# surfaceRX.net
KiCad netlist of a schematic drawn in EAGLE
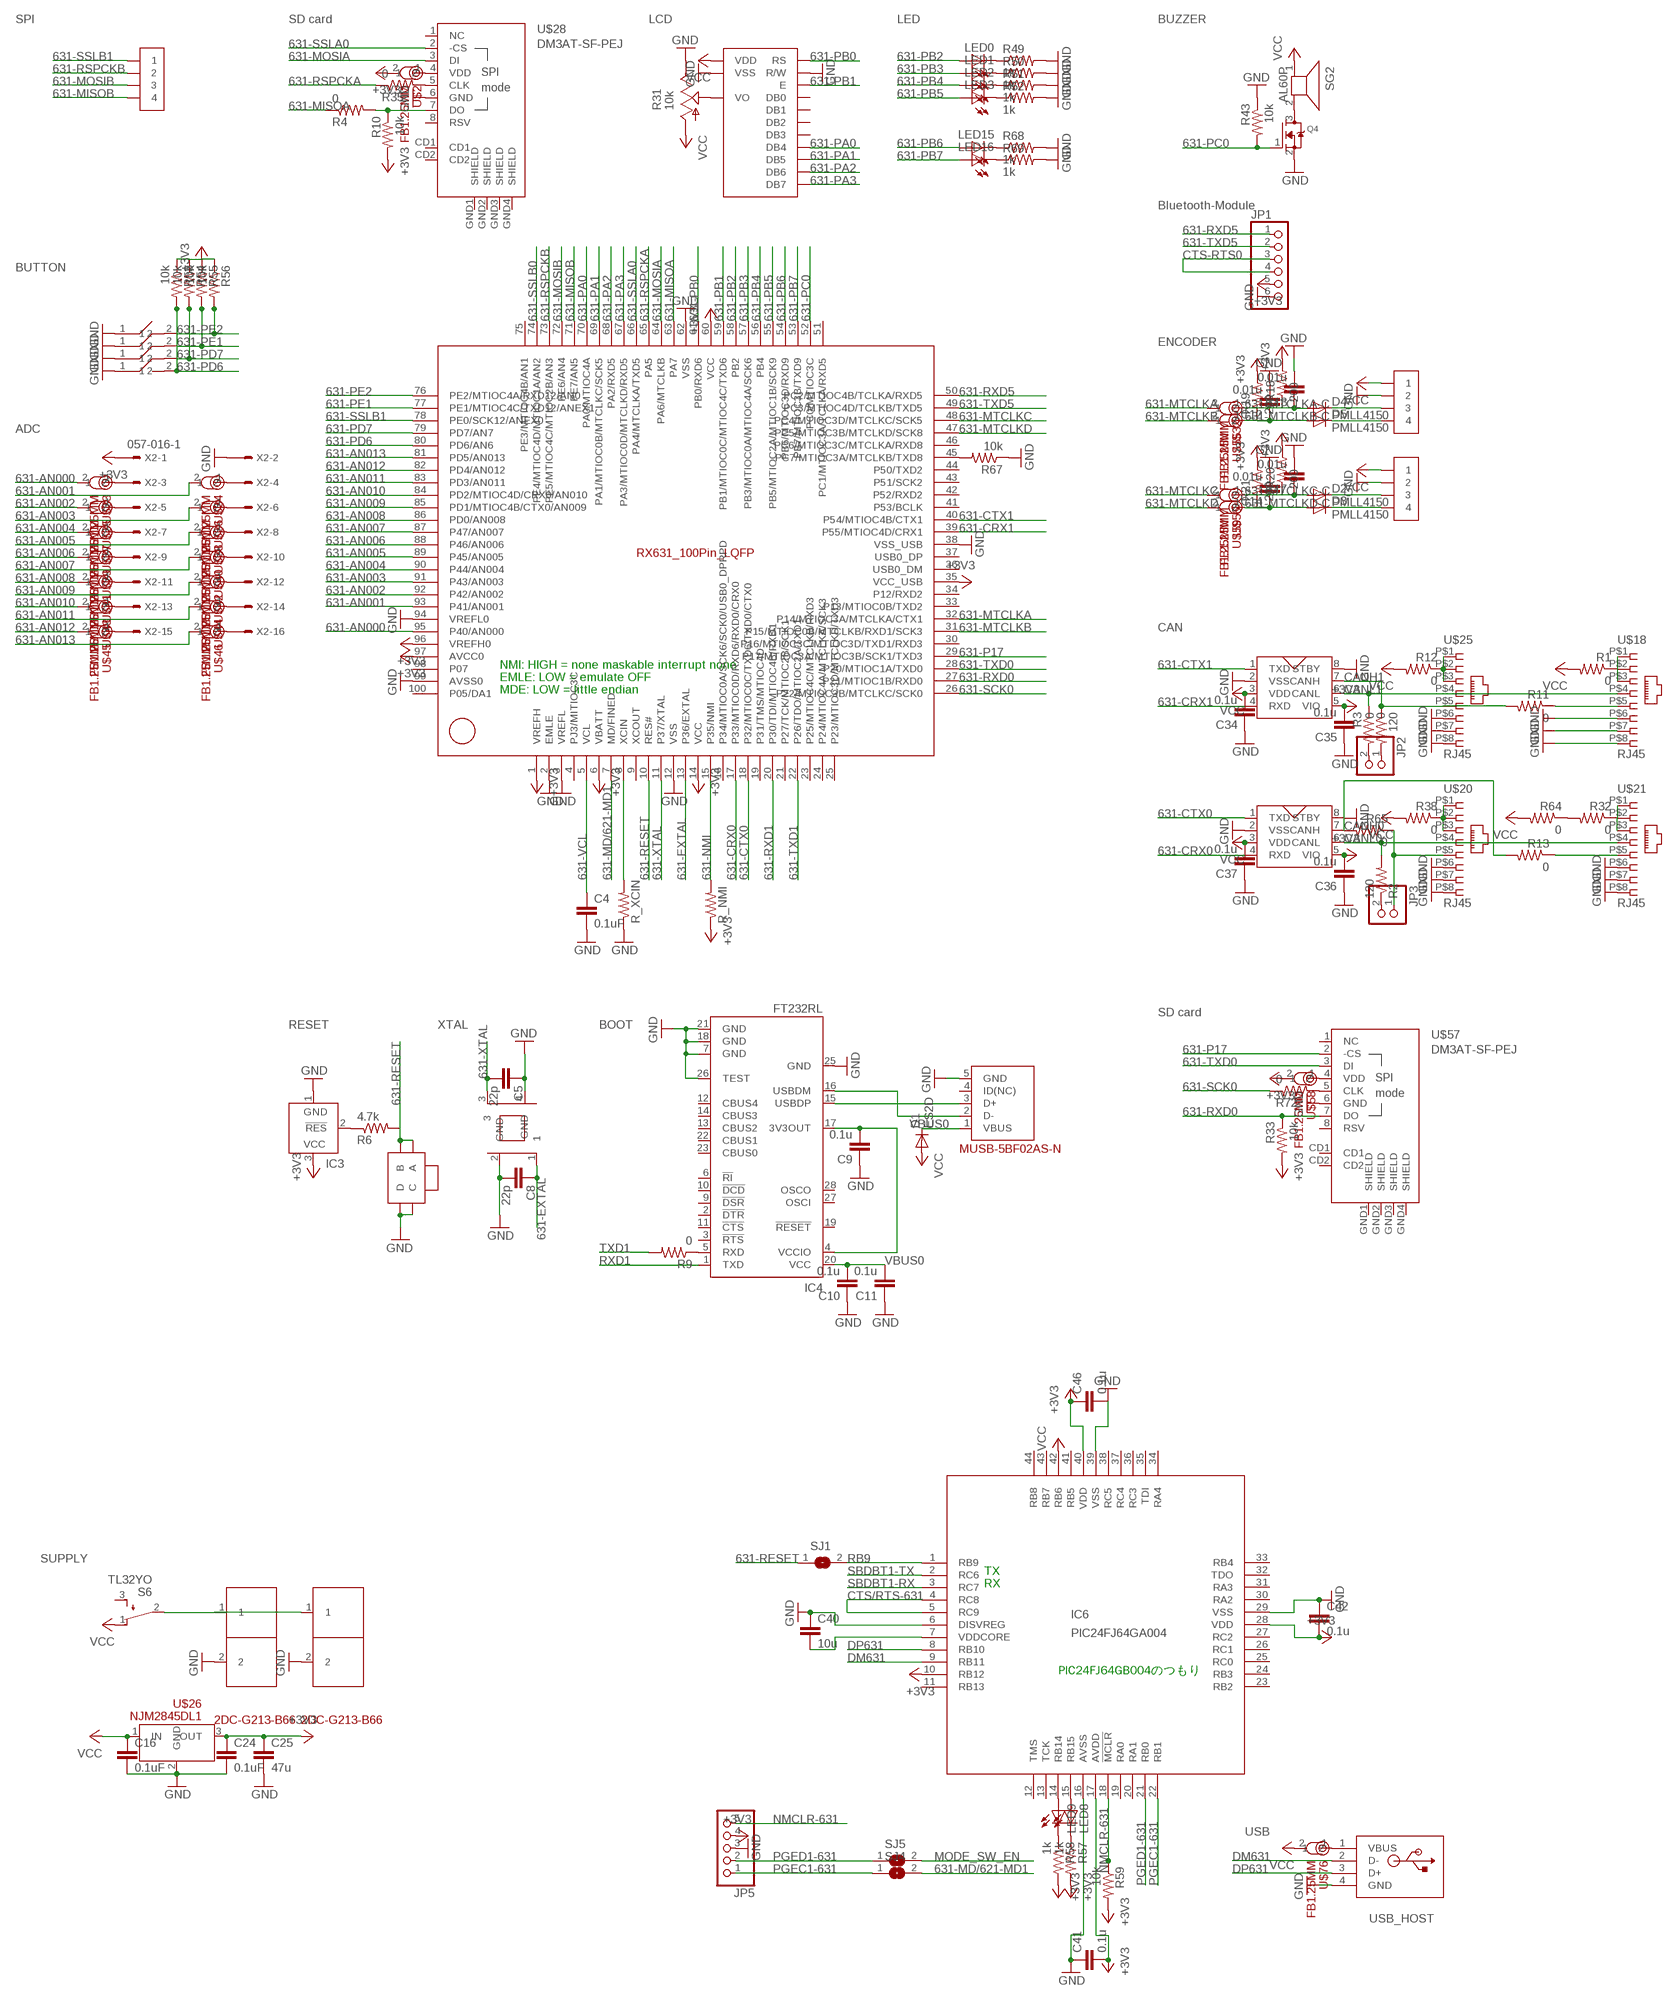
[diagram p0: schematic, sheet 1, part 1 of 2]
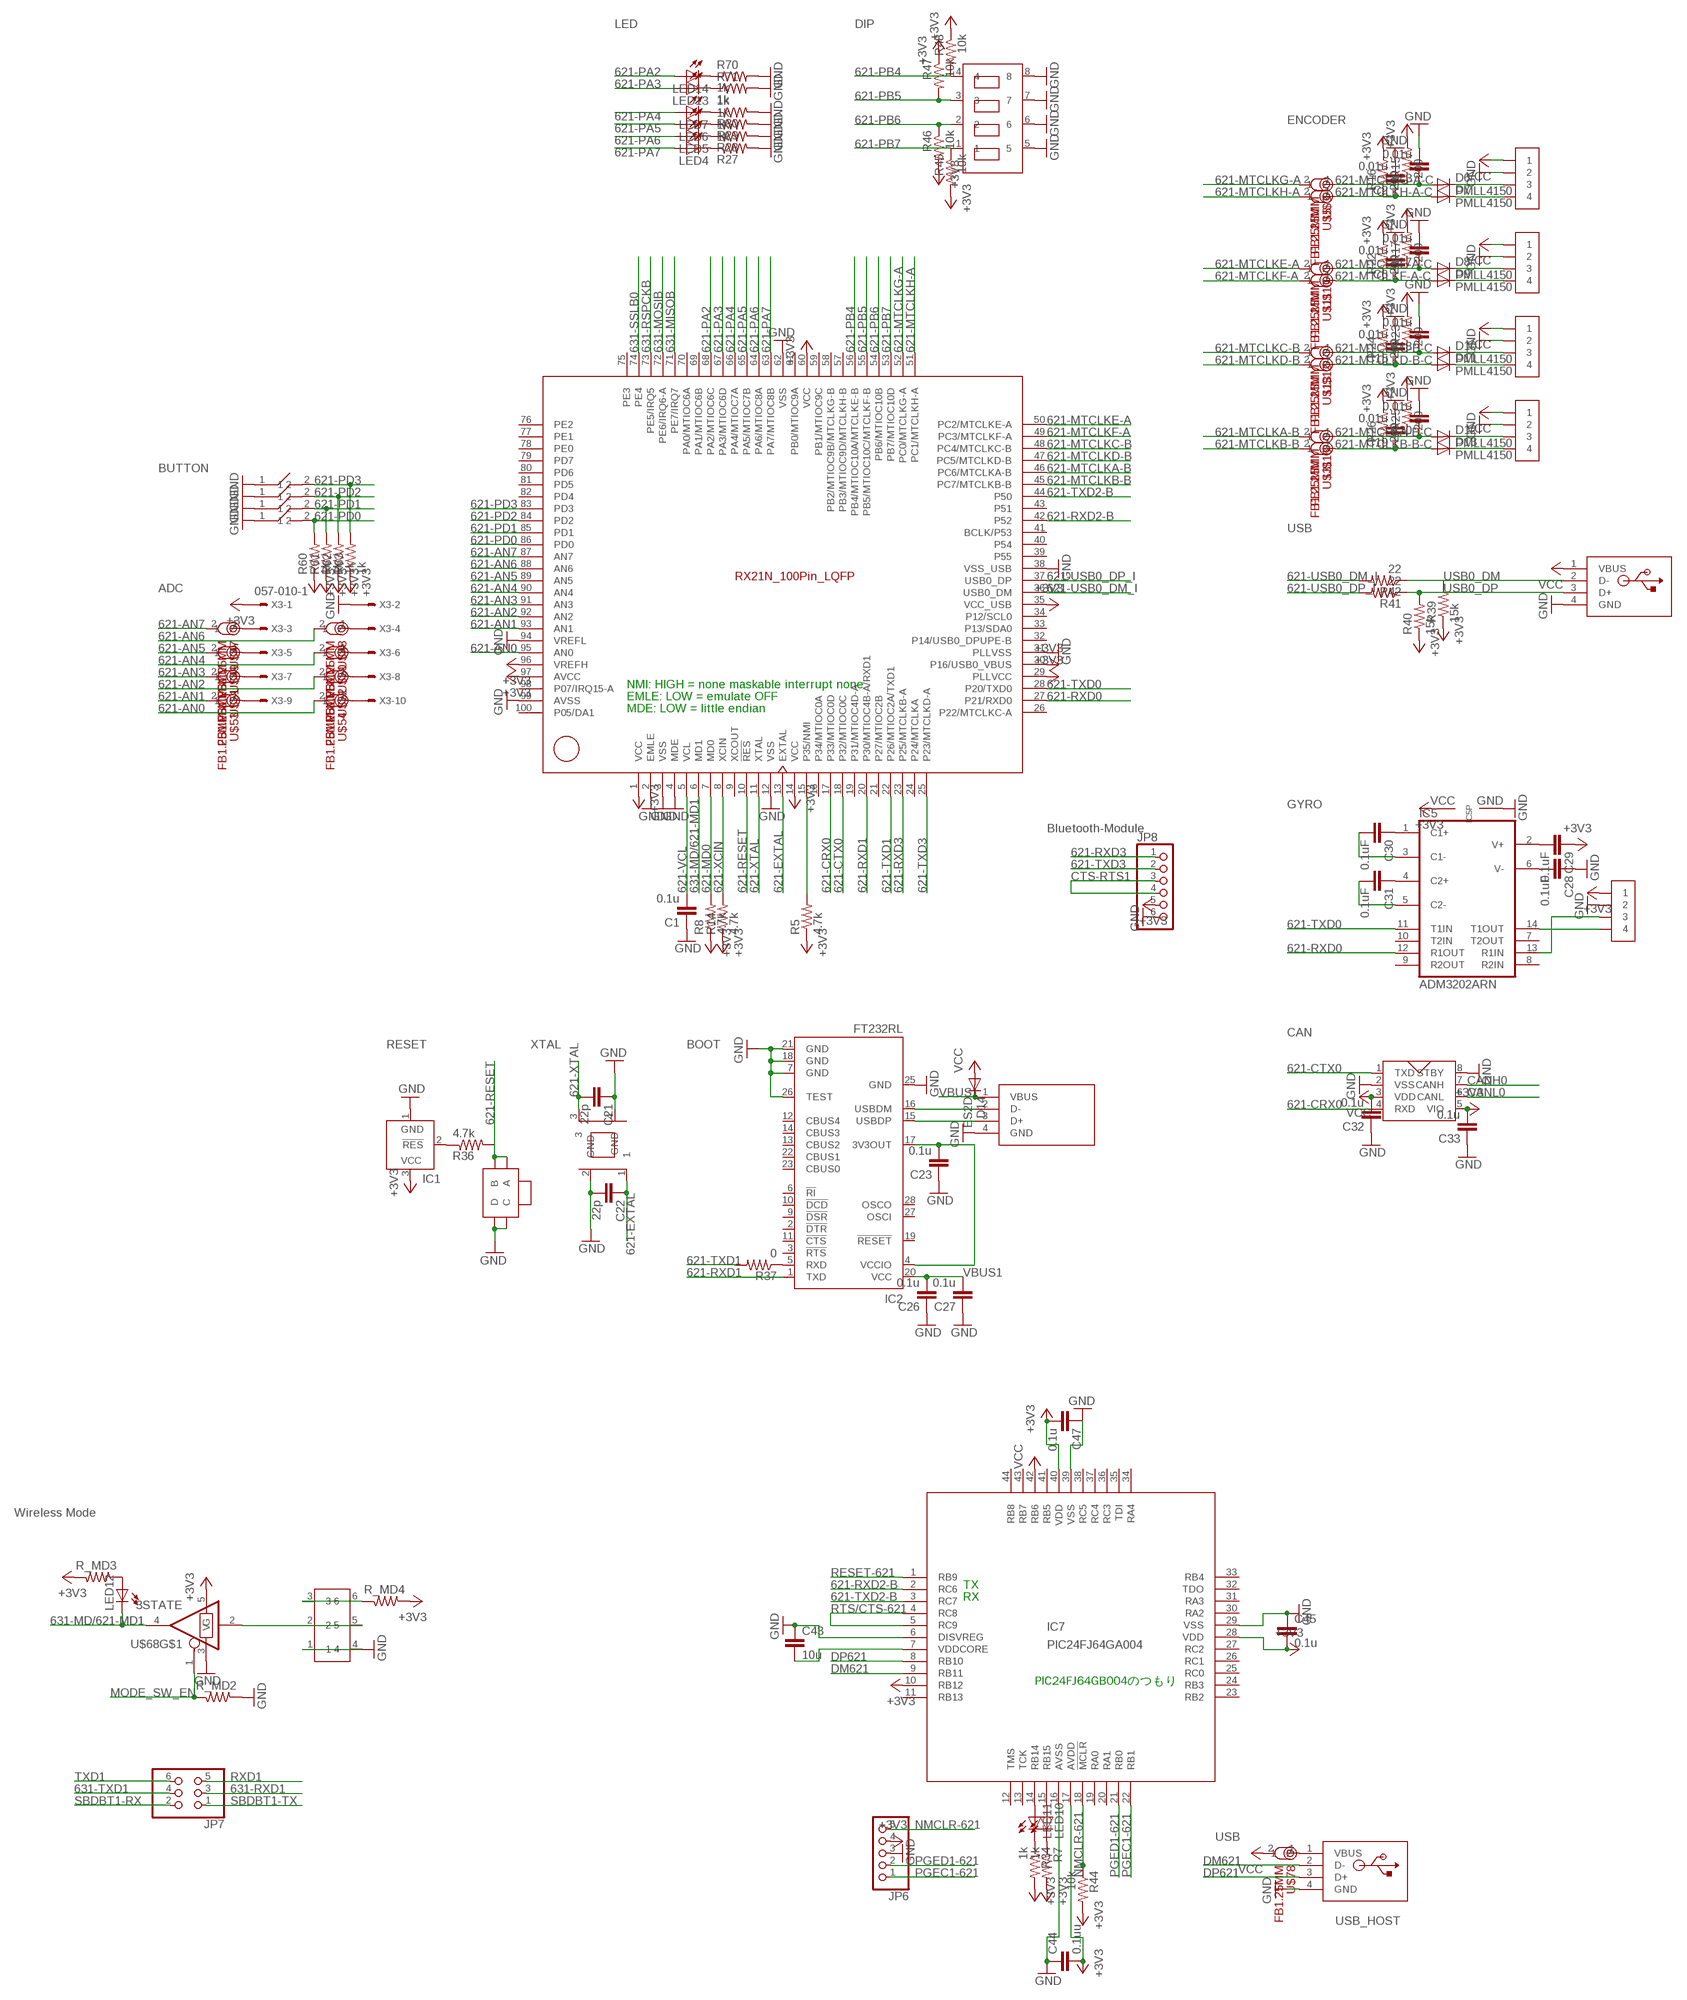
[diagram p1: schematic, sheet 1, part 2 of 2]

(export (version "E")
  (design (tool "Eeschema 10.0.6"))
  (components
    (comp (ref "0")
      (value "120")
      (footprint "eagle-import:MINI_MELF-0102W")
      (libsource (lib "eagle-import") (part "R-US_MELF0102W"))
    )
    (comp (ref "C1")
      (value "0.1u")
      (footprint "eagle-import:C0402")
      (libsource (lib "eagle-import") (part "C-EUC0402"))
    )
    (comp (ref "C2")
      (value "0.01u")
      (footprint "eagle-import:C0402")
      (libsource (lib "eagle-import") (part "C-EUC0402"))
    )
    (comp (ref "C3")
      (value "0.01u")
      (footprint "eagle-import:C0402")
      (libsource (lib "eagle-import") (part "C-EUC0402"))
    )
    (comp (ref "C4")
      (value "0.1uF")
      (footprint "eagle-import:C0603K")
      (libsource (lib "eagle-import") (part "C-EUC0603K"))
    )
    (comp (ref "C5")
      (value "22p")
      (footprint "eagle-import:C0603K")
      (libsource (lib "eagle-import") (part "C-EUC0603K"))
    )
    (comp (ref "C6")
      (value "0.01u")
      (footprint "eagle-import:C0402")
      (libsource (lib "eagle-import") (part "C-EUC0402"))
    )
    (comp (ref "C7")
      (value "0.01u")
      (footprint "eagle-import:C0402")
      (libsource (lib "eagle-import") (part "C-EUC0402"))
    )
    (comp (ref "C8")
      (value "22p")
      (footprint "eagle-import:C0603K")
      (libsource (lib "eagle-import") (part "C-EUC0603K"))
    )
    (comp (ref "C9")
      (value "0.1u")
      (footprint "eagle-import:C0402")
      (libsource (lib "eagle-import") (part "C-EUC0402"))
    )
    (comp (ref "C10")
      (value "0.1u")
      (footprint "eagle-import:C0402")
      (libsource (lib "eagle-import") (part "C-EUC0402"))
    )
    (comp (ref "C11")
      (value "0.1u")
      (footprint "eagle-import:C0402")
      (libsource (lib "eagle-import") (part "C-EUC0402"))
    )
    (comp (ref "C12")
      (value "0.01u")
      (footprint "eagle-import:C0402")
      (libsource (lib "eagle-import") (part "C-EUC0402"))
    )
    (comp (ref "C13")
      (value "0.01u")
      (footprint "eagle-import:C0402")
      (libsource (lib "eagle-import") (part "C-EUC0402"))
    )
    (comp (ref "C14")
      (value "0.01u")
      (footprint "eagle-import:C0402")
      (libsource (lib "eagle-import") (part "C-EUC0402"))
    )
    (comp (ref "C15")
      (value "0.01u")
      (footprint "eagle-import:C0402")
      (libsource (lib "eagle-import") (part "C-EUC0402"))
    )
    (comp (ref "C16")
      (value "0.1uF")
      (footprint "eagle-import:C0603K")
      (libsource (lib "eagle-import") (part "C-EUC0603K"))
    )
    (comp (ref "C17")
      (value "0.01u")
      (footprint "eagle-import:C0402")
      (libsource (lib "eagle-import") (part "C-EUC0402"))
    )
    (comp (ref "C18")
      (value "0.01u")
      (footprint "eagle-import:C0402")
      (libsource (lib "eagle-import") (part "C-EUC0402"))
    )
    (comp (ref "C19")
      (value "0.01u")
      (footprint "eagle-import:C0402")
      (libsource (lib "eagle-import") (part "C-EUC0402"))
    )
    (comp (ref "C20")
      (value "0.01u")
      (footprint "eagle-import:C0402")
      (libsource (lib "eagle-import") (part "C-EUC0402"))
    )
    (comp (ref "C21")
      (value "22p")
      (footprint "eagle-import:C0603K")
      (libsource (lib "eagle-import") (part "C-EUC0603K"))
    )
    (comp (ref "C22")
      (value "22p")
      (footprint "eagle-import:C0603K")
      (libsource (lib "eagle-import") (part "C-EUC0603K"))
    )
    (comp (ref "C23")
      (value "0.1u")
      (footprint "eagle-import:C0402")
      (libsource (lib "eagle-import") (part "C-EUC0402"))
    )
    (comp (ref "C24")
      (value "0.1uF")
      (footprint "eagle-import:C0603K")
      (libsource (lib "eagle-import") (part "C-EUC0603K"))
    )
    (comp (ref "C25")
      (value "47u")
      (footprint "eagle-import:C3225")
      (libsource (lib "eagle-import") (part "C-EUC3225"))
    )
    (comp (ref "C26")
      (value "0.1u")
      (footprint "eagle-import:C0402")
      (libsource (lib "eagle-import") (part "C-EUC0402"))
    )
    (comp (ref "C27")
      (value "0.1u")
      (footprint "eagle-import:C0402")
      (libsource (lib "eagle-import") (part "C-EUC0402"))
    )
    (comp (ref "C28")
      (value "0.1uF")
      (footprint "eagle-import:C0603K")
      (libsource (lib "eagle-import") (part "C-EUC0603K"))
    )
    (comp (ref "C29")
      (value "0.1uF")
      (footprint "eagle-import:C0603K")
      (libsource (lib "eagle-import") (part "C-EUC0603K"))
    )
    (comp (ref "C30")
      (value "0.1uF")
      (footprint "eagle-import:C0603K")
      (libsource (lib "eagle-import") (part "C-EUC0603K"))
    )
    (comp (ref "C31")
      (value "0.1uF")
      (footprint "eagle-import:C0603K")
      (libsource (lib "eagle-import") (part "C-EUC0603K"))
    )
    (comp (ref "C32")
      (value "0.1u")
      (footprint "eagle-import:C0402")
      (libsource (lib "eagle-import") (part "C-EUC0402"))
    )
    (comp (ref "C33")
      (value "0.1u")
      (footprint "eagle-import:C0402")
      (libsource (lib "eagle-import") (part "C-EUC0402"))
    )
    (comp (ref "C34")
      (value "0.1u")
      (footprint "eagle-import:C0402")
      (libsource (lib "eagle-import") (part "C-EUC0402"))
    )
    (comp (ref "C35")
      (value "0.1u")
      (footprint "eagle-import:C0402")
      (libsource (lib "eagle-import") (part "C-EUC0402"))
    )
    (comp (ref "C36")
      (value "0.1u")
      (footprint "eagle-import:C0402")
      (libsource (lib "eagle-import") (part "C-EUC0402"))
    )
    (comp (ref "C37")
      (value "0.1u")
      (footprint "eagle-import:C0402")
      (libsource (lib "eagle-import") (part "C-EUC0402"))
    )
    (comp (ref "C40")
      (value "10u")
      (footprint "eagle-import:C0603K")
      (libsource (lib "eagle-import") (part "C-EUC0603K"))
    )
    (comp (ref "C41")
      (value "0.1u")
      (footprint "eagle-import:C0603K")
      (libsource (lib "eagle-import") (part "C-EUC0603K"))
    )
    (comp (ref "C42")
      (value "0.1u")
      (footprint "eagle-import:C0603K")
      (libsource (lib "eagle-import") (part "C-EUC0603K"))
    )
    (comp (ref "C43")
      (value "10u")
      (footprint "eagle-import:C0603K")
      (libsource (lib "eagle-import") (part "C-EUC0603K"))
    )
    (comp (ref "C44")
      (value "0.1uu")
      (footprint "eagle-import:C0603K")
      (libsource (lib "eagle-import") (part "C-EUC0603K"))
    )
    (comp (ref "C45")
      (value "0.1u")
      (footprint "eagle-import:C0603K")
      (libsource (lib "eagle-import") (part "C-EUC0603K"))
    )
    (comp (ref "C46")
      (value "0.1u")
      (footprint "eagle-import:C0603K")
      (libsource (lib "eagle-import") (part "C-EUC0603K"))
    )
    (comp (ref "C47")
      (value "0.1u")
      (footprint "eagle-import:C0603K")
      (libsource (lib "eagle-import") (part "C-EUC0603K"))
    )
    (comp (ref "D1")
      (value "ES2D")
      (footprint "eagle-import:SMB")
      (libsource (lib "eagle-import") (part "ES2D"))
    )
    (comp (ref "D2")
      (value "PMLL4150")
      (footprint "eagle-import:SOD80C")
      (libsource (lib "eagle-import") (part "PMLL4150"))
    )
    (comp (ref "D3")
      (value "PMLL4150")
      (footprint "eagle-import:SOD80C")
      (libsource (lib "eagle-import") (part "PMLL4150"))
    )
    (comp (ref "D4")
      (value "PMLL4150")
      (footprint "eagle-import:SOD80C")
      (libsource (lib "eagle-import") (part "PMLL4150"))
    )
    (comp (ref "D5")
      (value "PMLL4150")
      (footprint "eagle-import:SOD80C")
      (libsource (lib "eagle-import") (part "PMLL4150"))
    )
    (comp (ref "D6")
      (value "PMLL4150")
      (footprint "eagle-import:SOD80C")
      (libsource (lib "eagle-import") (part "PMLL4150"))
    )
    (comp (ref "D7")
      (value "PMLL4150")
      (footprint "eagle-import:SOD80C")
      (libsource (lib "eagle-import") (part "PMLL4150"))
    )
    (comp (ref "D8")
      (value "PMLL4150")
      (footprint "eagle-import:SOD80C")
      (libsource (lib "eagle-import") (part "PMLL4150"))
    )
    (comp (ref "D9")
      (value "PMLL4150")
      (footprint "eagle-import:SOD80C")
      (libsource (lib "eagle-import") (part "PMLL4150"))
    )
    (comp (ref "D10")
      (value "PMLL4150")
      (footprint "eagle-import:SOD80C")
      (libsource (lib "eagle-import") (part "PMLL4150"))
    )
    (comp (ref "D11")
      (value "PMLL4150")
      (footprint "eagle-import:SOD80C")
      (libsource (lib "eagle-import") (part "PMLL4150"))
    )
    (comp (ref "D12")
      (value "PMLL4150")
      (footprint "eagle-import:SOD80C")
      (libsource (lib "eagle-import") (part "PMLL4150"))
    )
    (comp (ref "D13")
      (value "PMLL4150")
      (footprint "eagle-import:SOD80C")
      (libsource (lib "eagle-import") (part "PMLL4150"))
    )
    (comp (ref "D14")
      (value "ES2D")
      (footprint "eagle-import:SMB")
      (libsource (lib "eagle-import") (part "ES2D"))
    )
    (comp (ref "IC1")
      (value "TCM809")
      (footprint "eagle-import:SOT23B-3")
      (fields (field (name "MF") "MICROCHIP") (field (name "MPN") "TCM809MENB713"))
      (libsource (lib "eagle-import") (part "TCM809"))
    )
    (comp (ref "IC2")
      (value "FT232RL")
      (footprint "eagle-import:SSOP28")
      (libsource (lib "eagle-import") (part "FT232RL"))
    )
    (comp (ref "IC3")
      (value "TCM809")
      (footprint "eagle-import:SOT23B-3")
      (fields (field (name "MF") "MICROCHIP") (field (name "MPN") "TCM809MENB713"))
      (libsource (lib "eagle-import") (part "TCM809"))
    )
    (comp (ref "IC4")
      (value "FT232RL")
      (footprint "eagle-import:SSOP28")
      (libsource (lib "eagle-import") (part "FT232RL"))
    )
    (comp (ref "IC5")
      (value "ADM3202ARN")
      (footprint "eagle-import:SO16")
      (libsource (lib "eagle-import") (part "ADM3202ARN"))
    )
    (comp (ref "IC6")
      (value "PIC24FJ64GA004")
      (footprint "eagle-import:TQFP44")
      (fields (field (name "MPN") "PIC24FJ64GA004-E/PT"))
      (libsource (lib "eagle-import") (part "PIC24FJ64GA004"))
    )
    (comp (ref "IC7")
      (value "PIC24FJ64GA004")
      (footprint "eagle-import:TQFP44")
      (fields (field (name "MPN") "PIC24FJ64GA004-E/PT"))
      (libsource (lib "eagle-import") (part "PIC24FJ64GA004"))
    )
    (comp (ref "JP1")
      (value "PINHD-1X6")
      (footprint "eagle-import:1X06")
      (libsource (lib "eagle-import") (part "PINHD-1X6"))
    )
    (comp (ref "JP2")
      (value "PINHD-1X2")
      (footprint "eagle-import:1X02")
      (libsource (lib "eagle-import") (part "PINHD-1X2"))
    )
    (comp (ref "JP3")
      (value "PINHD-1X2")
      (footprint "eagle-import:1X02")
      (libsource (lib "eagle-import") (part "PINHD-1X2"))
    )
    (comp (ref "JP5")
      (value "PINHD-1X5")
      (footprint "eagle-import:1X05")
      (libsource (lib "eagle-import") (part "PINHD-1X5"))
    )
    (comp (ref "JP6")
      (value "PINHD-1X5")
      (footprint "eagle-import:1X05")
      (libsource (lib "eagle-import") (part "PINHD-1X5"))
    )
    (comp (ref "JP7")
      (value "PINHD-2X3")
      (footprint "eagle-import:2X03")
      (libsource (lib "eagle-import") (part "PINHD-2X3"))
    )
    (comp (ref "JP8")
      (value "PINHD-1X6")
      (footprint "eagle-import:1X06")
      (libsource (lib "eagle-import") (part "PINHD-1X6"))
    )
    (comp (ref "LED0")
      (value "LEDSML0805")
      (footprint "eagle-import:SML0805")
      (libsource (lib "eagle-import") (part "LEDSML0805"))
    )
    (comp (ref "LED1")
      (value "LEDSML0805")
      (footprint "eagle-import:SML0805")
      (libsource (lib "eagle-import") (part "LEDSML0805"))
    )
    (comp (ref "LED2")
      (value "LEDSML0805")
      (footprint "eagle-import:SML0805")
      (libsource (lib "eagle-import") (part "LEDSML0805"))
    )
    (comp (ref "LED3")
      (value "LEDSML0805")
      (footprint "eagle-import:SML0805")
      (libsource (lib "eagle-import") (part "LEDSML0805"))
    )
    (comp (ref "LED4")
      (value "LEDSML0805")
      (footprint "eagle-import:SML0805")
      (libsource (lib "eagle-import") (part "LEDSML0805"))
    )
    (comp (ref "LED5")
      (value "LEDSML0805")
      (footprint "eagle-import:SML0805")
      (libsource (lib "eagle-import") (part "LEDSML0805"))
    )
    (comp (ref "LED6")
      (value "LEDSML0805")
      (footprint "eagle-import:SML0805")
      (libsource (lib "eagle-import") (part "LEDSML0805"))
    )
    (comp (ref "LED7")
      (value "LEDSML0805")
      (footprint "eagle-import:SML0805")
      (libsource (lib "eagle-import") (part "LEDSML0805"))
    )
    (comp (ref "LED8")
      (value "LEDSML0805")
      (footprint "eagle-import:SML0805")
      (libsource (lib "eagle-import") (part "LEDSML0805"))
    )
    (comp (ref "LED9")
      (value "LEDSML0805")
      (footprint "eagle-import:SML0805")
      (libsource (lib "eagle-import") (part "LEDSML0805"))
    )
    (comp (ref "LED10")
      (value "LEDSML0805")
      (footprint "eagle-import:SML0805")
      (libsource (lib "eagle-import") (part "LEDSML0805"))
    )
    (comp (ref "LED11")
      (value "LEDSML0805")
      (footprint "eagle-import:SML0805")
      (libsource (lib "eagle-import") (part "LEDSML0805"))
    )
    (comp (ref "LED12")
      (value "LEDSML0805")
      (footprint "eagle-import:SML0805")
      (libsource (lib "eagle-import") (part "LEDSML0805"))
    )
    (comp (ref "LED13")
      (value "LEDSML0805")
      (footprint "eagle-import:SML0805")
      (libsource (lib "eagle-import") (part "LEDSML0805"))
    )
    (comp (ref "LED14")
      (value "LEDSML0805")
      (footprint "eagle-import:SML0805")
      (libsource (lib "eagle-import") (part "LEDSML0805"))
    )
    (comp (ref "LED15")
      (value "LEDSML0805")
      (footprint "eagle-import:SML0805")
      (libsource (lib "eagle-import") (part "LEDSML0805"))
    )
    (comp (ref "LED16")
      (value "LEDSML0805")
      (footprint "eagle-import:SML0805")
      (libsource (lib "eagle-import") (part "LEDSML0805"))
    )
    (comp (ref "MCU1")
      (value "R5F562N8BDFP")
      (footprint "eagle-import:LQFP100")
      (libsource (lib "eagle-import") (part "R5F562N8BDFP"))
    )
    (comp (ref "Q4")
      (value "MOSFET-NREFLOW")
      (footprint "eagle-import:SOT23")
      (libsource (lib "eagle-import") (part "MOSFET-NREFLOW"))
    )
    (comp (ref "R1")
      (value "0")
      (footprint "eagle-import:MINI_MELF-0102W")
      (libsource (lib "eagle-import") (part "R-US_MELF0102W"))
    )
    (comp (ref "R2")
      (value "120")
      (footprint "eagle-import:MINI_MELF-0102W")
      (libsource (lib "eagle-import") (part "R-US_MELF0102W"))
    )
    (comp (ref "R3")
      (value "0")
      (footprint "eagle-import:MINI_MELF-0102W")
      (libsource (lib "eagle-import") (part "R-US_MELF0102W"))
    )
    (comp (ref "R4")
      (value "0")
      (footprint "eagle-import:MINI_MELF-0102W")
      (libsource (lib "eagle-import") (part "R-US_MELF0102W"))
    )
    (comp (ref "R5")
      (value "4.7k")
      (footprint "eagle-import:MINI_MELF-0102W")
      (libsource (lib "eagle-import") (part "R-US_MELF0102W"))
    )
    (comp (ref "R6")
      (value "4.7k")
      (footprint "eagle-import:MINI_MELF-0102W")
      (libsource (lib "eagle-import") (part "R-US_MELF0102W"))
    )
    (comp (ref "R7")
      (value "1k")
      (footprint "eagle-import:MINI_MELF-0102W")
      (libsource (lib "eagle-import") (part "R-US_MELF0102W"))
    )
    (comp (ref "R8")
      (value "4.7k")
      (footprint "eagle-import:MINI_MELF-0102W")
      (libsource (lib "eagle-import") (part "R-US_MELF0102W"))
    )
    (comp (ref "R9")
      (value "0")
      (footprint "eagle-import:MINI_MELF-0102W")
      (libsource (lib "eagle-import") (part "R-US_MELF0102W"))
    )
    (comp (ref "R10")
      (value "10k")
      (footprint "eagle-import:MINI_MELF-0102W")
      (libsource (lib "eagle-import") (part "R-US_MELF0102W"))
    )
    (comp (ref "R11")
      (value "0")
      (footprint "eagle-import:MINI_MELF-0102W")
      (libsource (lib "eagle-import") (part "R-US_MELF0102W"))
    )
    (comp (ref "R12")
      (value "0")
      (footprint "eagle-import:MINI_MELF-0102W")
      (libsource (lib "eagle-import") (part "R-US_MELF0102W"))
    )
    (comp (ref "R13")
      (value "0")
      (footprint "eagle-import:MINI_MELF-0102W")
      (libsource (lib "eagle-import") (part "R-US_MELF0102W"))
    )
    (comp (ref "R14")
      (value "4.7k")
      (footprint "eagle-import:MINI_MELF-0102W")
      (libsource (lib "eagle-import") (part "R-US_MELF0102W"))
    )
    (comp (ref "R15")
      (value "200")
      (footprint "eagle-import:MINI_MELF-0102W")
      (libsource (lib "eagle-import") (part "R-US_MELF0102W"))
    )
    (comp (ref "R16")
      (value "200")
      (footprint "eagle-import:MINI_MELF-0102W")
      (libsource (lib "eagle-import") (part "R-US_MELF0102W"))
    )
    (comp (ref "R17")
      (value "200")
      (footprint "eagle-import:MINI_MELF-0102W")
      (libsource (lib "eagle-import") (part "R-US_MELF0102W"))
    )
    (comp (ref "R18")
      (value "200")
      (footprint "eagle-import:MINI_MELF-0102W")
      (libsource (lib "eagle-import") (part "R-US_MELF0102W"))
    )
    (comp (ref "R19")
      (value "200")
      (footprint "eagle-import:MINI_MELF-0102W")
      (libsource (lib "eagle-import") (part "R-US_MELF0102W"))
    )
    (comp (ref "R20")
      (value "200")
      (footprint "eagle-import:MINI_MELF-0102W")
      (libsource (lib "eagle-import") (part "R-US_MELF0102W"))
    )
    (comp (ref "R21")
      (value "200")
      (footprint "eagle-import:MINI_MELF-0102W")
      (libsource (lib "eagle-import") (part "R-US_MELF0102W"))
    )
    (comp (ref "R22")
      (value "200")
      (footprint "eagle-import:MINI_MELF-0102W")
      (libsource (lib "eagle-import") (part "R-US_MELF0102W"))
    )
    (comp (ref "R23")
      (value "200")
      (footprint "eagle-import:MINI_MELF-0102W")
      (libsource (lib "eagle-import") (part "R-US_MELF0102W"))
    )
    (comp (ref "R24")
      (value "200")
      (footprint "eagle-import:MINI_MELF-0102W")
      (libsource (lib "eagle-import") (part "R-US_MELF0102W"))
    )
    (comp (ref "R25")
      (value "200")
      (footprint "eagle-import:MINI_MELF-0102W")
      (libsource (lib "eagle-import") (part "R-US_MELF0102W"))
    )
    (comp (ref "R26")
      (value "200")
      (footprint "eagle-import:MINI_MELF-0102W")
      (libsource (lib "eagle-import") (part "R-US_MELF0102W"))
    )
    (comp (ref "R27")
      (value "1k")
      (footprint "eagle-import:MINI_MELF-0102W")
      (libsource (lib "eagle-import") (part "R-US_MELF0102W"))
    )
    (comp (ref "R28")
      (value "1k")
      (footprint "eagle-import:MINI_MELF-0102W")
      (libsource (lib "eagle-import") (part "R-US_MELF0102W"))
    )
    (comp (ref "R29")
      (value "1k")
      (footprint "eagle-import:MINI_MELF-0102W")
      (libsource (lib "eagle-import") (part "R-US_MELF0102W"))
    )
    (comp (ref "R30")
      (value "1k")
      (footprint "eagle-import:MINI_MELF-0102W")
      (libsource (lib "eagle-import") (part "R-US_MELF0102W"))
    )
    (comp (ref "R31")
      (value "10k")
      (footprint "eagle-import:CA6V")
      (libsource (lib "eagle-import") (part "TRIM_US-CA6V"))
    )
    (comp (ref "R32")
      (value "0")
      (footprint "eagle-import:MINI_MELF-0102W")
      (libsource (lib "eagle-import") (part "R-US_MELF0102W"))
    )
    (comp (ref "R33")
      (value "10k")
      (footprint "eagle-import:MINI_MELF-0102W")
      (libsource (lib "eagle-import") (part "R-US_MELF0102W"))
    )
    (comp (ref "R34")
      (value "1k")
      (footprint "eagle-import:MINI_MELF-0102W")
      (libsource (lib "eagle-import") (part "R-US_MELF0102W"))
    )
    (comp (ref "R35")
      (value "0")
      (footprint "eagle-import:MINI_MELF-0102W")
      (libsource (lib "eagle-import") (part "R-US_MELF0102W"))
    )
    (comp (ref "R36")
      (value "4.7k")
      (footprint "eagle-import:MINI_MELF-0102W")
      (libsource (lib "eagle-import") (part "R-US_MELF0102W"))
    )
    (comp (ref "R37")
      (value "0")
      (footprint "eagle-import:MINI_MELF-0102W")
      (libsource (lib "eagle-import") (part "R-US_MELF0102W"))
    )
    (comp (ref "R38")
      (value "0")
      (footprint "eagle-import:MINI_MELF-0102W")
      (libsource (lib "eagle-import") (part "R-US_MELF0102W"))
    )
    (comp (ref "R39")
      (value "15k")
      (footprint "eagle-import:MINI_MELF-0102W")
      (libsource (lib "eagle-import") (part "R-US_MELF0102W"))
    )
    (comp (ref "R40")
      (value "15k")
      (footprint "eagle-import:MINI_MELF-0102W")
      (libsource (lib "eagle-import") (part "R-US_MELF0102W"))
    )
    (comp (ref "R41")
      (value "22")
      (footprint "eagle-import:MINI_MELF-0102W")
      (libsource (lib "eagle-import") (part "R-US_MELF0102W"))
    )
    (comp (ref "R42")
      (value "22")
      (footprint "eagle-import:MINI_MELF-0102W")
      (libsource (lib "eagle-import") (part "R-US_MELF0102W"))
    )
    (comp (ref "R43")
      (value "10k")
      (footprint "eagle-import:MINI_MELF-0102W")
      (libsource (lib "eagle-import") (part "R-US_MELF0102W"))
    )
    (comp (ref "R44")
      (value "10k")
      (footprint "eagle-import:MINI_MELF-0102W")
      (libsource (lib "eagle-import") (part "R-US_MELF0102W"))
    )
    (comp (ref "R45")
      (value "10k")
      (footprint "eagle-import:MINI_MELF-0102W")
      (libsource (lib "eagle-import") (part "R-US_MELF0102W"))
    )
    (comp (ref "R46")
      (value "10k")
      (footprint "eagle-import:MINI_MELF-0102W")
      (libsource (lib "eagle-import") (part "R-US_MELF0102W"))
    )
    (comp (ref "R47")
      (value "10k")
      (footprint "eagle-import:MINI_MELF-0102W")
      (libsource (lib "eagle-import") (part "R-US_MELF0102W"))
    )
    (comp (ref "R48")
      (value "10k")
      (footprint "eagle-import:MINI_MELF-0102W")
      (libsource (lib "eagle-import") (part "R-US_MELF0102W"))
    )
    (comp (ref "R49")
      (value "1k")
      (footprint "eagle-import:MINI_MELF-0102W")
      (libsource (lib "eagle-import") (part "R-US_MELF0102W"))
    )
    (comp (ref "R50")
      (value "1k")
      (footprint "eagle-import:MINI_MELF-0102W")
      (libsource (lib "eagle-import") (part "R-US_MELF0102W"))
    )
    (comp (ref "R51")
      (value "1k")
      (footprint "eagle-import:MINI_MELF-0102W")
      (libsource (lib "eagle-import") (part "R-US_MELF0102W"))
    )
    (comp (ref "R52")
      (value "1k")
      (footprint "eagle-import:MINI_MELF-0102W")
      (libsource (lib "eagle-import") (part "R-US_MELF0102W"))
    )
    (comp (ref "R53")
      (value "10k")
      (footprint "eagle-import:MINI_MELF-0102W")
      (libsource (lib "eagle-import") (part "R-US_MELF0102W"))
    )
    (comp (ref "R54")
      (value "10k")
      (footprint "eagle-import:MINI_MELF-0102W")
      (libsource (lib "eagle-import") (part "R-US_MELF0102W"))
    )
    (comp (ref "R55")
      (value "10k")
      (footprint "eagle-import:MINI_MELF-0102W")
      (libsource (lib "eagle-import") (part "R-US_MELF0102W"))
    )
    (comp (ref "R56")
      (value "10k")
      (footprint "eagle-import:MINI_MELF-0102W")
      (libsource (lib "eagle-import") (part "R-US_MELF0102W"))
    )
    (comp (ref "R57")
      (value "1k")
      (footprint "eagle-import:MINI_MELF-0102W")
      (libsource (lib "eagle-import") (part "R-US_MELF0102W"))
    )
    (comp (ref "R58")
      (value "1k")
      (footprint "eagle-import:MINI_MELF-0102W")
      (libsource (lib "eagle-import") (part "R-US_MELF0102W"))
    )
    (comp (ref "R59")
      (value "10k")
      (footprint "eagle-import:MINI_MELF-0102W")
      (libsource (lib "eagle-import") (part "R-US_MELF0102W"))
    )
    (comp (ref "R60")
      (value "1k")
      (footprint "eagle-import:MINI_MELF-0102W")
      (libsource (lib "eagle-import") (part "R-US_MELF0102W"))
    )
    (comp (ref "R61")
      (value "1k")
      (footprint "eagle-import:MINI_MELF-0102W")
      (libsource (lib "eagle-import") (part "R-US_MELF0102W"))
    )
    (comp (ref "R62")
      (value "1k")
      (footprint "eagle-import:MINI_MELF-0102W")
      (libsource (lib "eagle-import") (part "R-US_MELF0102W"))
    )
    (comp (ref "R63")
      (value "1k")
      (footprint "eagle-import:MINI_MELF-0102W")
      (libsource (lib "eagle-import") (part "R-US_MELF0102W"))
    )
    (comp (ref "R64")
      (value "0")
      (footprint "eagle-import:MINI_MELF-0102W")
      (libsource (lib "eagle-import") (part "R-US_MELF0102W"))
    )
    (comp (ref "R65")
      (value "0")
      (footprint "eagle-import:MINI_MELF-0102W")
      (libsource (lib "eagle-import") (part "R-US_MELF0102W"))
    )
    (comp (ref "R67")
      (value "10k")
      (footprint "eagle-import:MINI_MELF-0102W")
      (libsource (lib "eagle-import") (part "R-US_MELF0102W"))
    )
    (comp (ref "R68")
      (value "1k")
      (footprint "eagle-import:MINI_MELF-0102W")
      (libsource (lib "eagle-import") (part "R-US_MELF0102W"))
    )
    (comp (ref "R69")
      (value "1k")
      (footprint "eagle-import:MINI_MELF-0102W")
      (libsource (lib "eagle-import") (part "R-US_MELF0102W"))
    )
    (comp (ref "R70")
      (value "1k")
      (footprint "eagle-import:MINI_MELF-0102W")
      (libsource (lib "eagle-import") (part "R-US_MELF0102W"))
    )
    (comp (ref "R71")
      (value "1k")
      (footprint "eagle-import:MINI_MELF-0102W")
      (libsource (lib "eagle-import") (part "R-US_MELF0102W"))
    )
    (comp (ref "R72")
      (value "0")
      (footprint "eagle-import:MINI_MELF-0102W")
      (libsource (lib "eagle-import") (part "R-US_MELF0102W"))
    )
    (comp (ref "R_MD2")
      (value "R-US_MELF0102W")
      (footprint "eagle-import:MINI_MELF-0102W")
      (libsource (lib "eagle-import") (part "R-US_MELF0102W"))
    )
    (comp (ref "R_MD3")
      (value "R-US_MELF0102W")
      (footprint "eagle-import:MINI_MELF-0102W")
      (libsource (lib "eagle-import") (part "R-US_MELF0102W"))
    )
    (comp (ref "R_MD4")
      (value "R-US_MELF0102W")
      (footprint "eagle-import:MINI_MELF-0102W")
      (libsource (lib "eagle-import") (part "R-US_MELF0102W"))
    )
    (comp (ref "R_NMI")
      (value "R-US_MELF0102W")
      (footprint "eagle-import:MINI_MELF-0102W")
      (libsource (lib "eagle-import") (part "R-US_MELF0102W"))
    )
    (comp (ref "R_XCIN")
      (value "R-US_MELF0102W")
      (footprint "eagle-import:MINI_MELF-0102W")
      (libsource (lib "eagle-import") (part "R-US_MELF0102W"))
    )
    (comp (ref "S6")
      (value "TL32YO")
      (footprint "eagle-import:TL3XYO")
      (libsource (lib "eagle-import") (part "TL32YO"))
    )
    (comp (ref "SG2")
      (value "AL60P")
      (footprint "eagle-import:AL60P")
      (libsource (lib "eagle-import") (part "AL60P"))
    )
    (comp (ref "SJ1") (value "SJ") (footprint "eagle-import:SJ") (libsource (lib "eagle-import") (part "SJ")))
    (comp (ref "SJ4") (value "SJ") (footprint "eagle-import:SJ") (libsource (lib "eagle-import") (part "SJ")))
    (comp (ref "SJ5") (value "SJ") (footprint "eagle-import:SJ") (libsource (lib "eagle-import") (part "SJ")))
    (comp (ref "U$1")
      (value "GHTOP4")
      (footprint "eagle-import:GHTOP4")
      (libsource (lib "eagle-import") (part "GHTOP4"))
    )
    (comp (ref "U$2")
      (value "FB1.25MM")
      (footprint "eagle-import:2012")
      (libsource (lib "eagle-import") (part "FB1.25MM"))
    )
    (comp (ref "U$3")
      (value "FB1.25MM")
      (footprint "eagle-import:2012")
      (libsource (lib "eagle-import") (part "FB1.25MM"))
    )
    (comp (ref "U$4")
      (value "R5F5631FDDFP")
      (footprint "eagle-import:LQFP100")
      (libsource (lib "eagle-import") (part "R5F5631FDDFP"))
    )
    (comp (ref "U$5")
      (value "FB1.25MM")
      (footprint "eagle-import:2012")
      (libsource (lib "eagle-import") (part "FB1.25MM"))
    )
    (comp (ref "U$6")
      (value "TSHA-T-2")
      (footprint "eagle-import:TSHA-T-2")
      (libsource (lib "eagle-import") (part "TSHA-T-2"))
    )
    (comp (ref "U$8")
      (value "TSHA-T-2")
      (footprint "eagle-import:TSHA-T-2")
      (libsource (lib "eagle-import") (part "TSHA-T-2"))
    )
    (comp (ref "U$9")
      (value "MUSB-5BF02AS-N")
      (footprint "eagle-import:MUSB-5BF02AS-N")
      (libsource (lib "eagle-import") (part "MUSB-5BF02AS-N"))
    )
    (comp (ref "U$10")
      (value "FB1.25MM")
      (footprint "eagle-import:2012")
      (libsource (lib "eagle-import") (part "FB1.25MM"))
    )
    (comp (ref "U$11")
      (value "FB1.25MM")
      (footprint "eagle-import:2012")
      (libsource (lib "eagle-import") (part "FB1.25MM"))
    )
    (comp (ref "U$12")
      (value "FB1.25MM")
      (footprint "eagle-import:2012")
      (libsource (lib "eagle-import") (part "FB1.25MM"))
    )
    (comp (ref "U$13")
      (value "FB1.25MM")
      (footprint "eagle-import:2012")
      (libsource (lib "eagle-import") (part "FB1.25MM"))
    )
    (comp (ref "U$14")
      (value "GHTOP4")
      (footprint "eagle-import:GHTOP4")
      (libsource (lib "eagle-import") (part "GHTOP4"))
    )
    (comp (ref "U$15")
      (value "GHTOP4")
      (footprint "eagle-import:GHTOP4")
      (libsource (lib "eagle-import") (part "GHTOP4"))
    )
    (comp (ref "U$16")
      (value "FB1.25MM")
      (footprint "eagle-import:2012")
      (libsource (lib "eagle-import") (part "FB1.25MM"))
    )
    (comp (ref "U$17")
      (value "MCP2562")
      (footprint "eagle-import:MCP2562")
      (libsource (lib "eagle-import") (part "MCP2562"))
    )
    (comp (ref "U$18")
      (value "RJ45")
      (footprint "eagle-import:RJ45")
      (libsource (lib "eagle-import") (part "RJ45"))
    )
    (comp (ref "U$19")
      (value "MCP2562")
      (footprint "eagle-import:MCP2562")
      (libsource (lib "eagle-import") (part "MCP2562"))
    )
    (comp (ref "U$20")
      (value "RJ45")
      (footprint "eagle-import:RJ45")
      (libsource (lib "eagle-import") (part "RJ45"))
    )
    (comp (ref "U$21")
      (value "RJ45")
      (footprint "eagle-import:RJ45")
      (libsource (lib "eagle-import") (part "RJ45"))
    )
    (comp (ref "U$22")
      (value "2DC-G213-B66")
      (footprint "eagle-import:2DC-G213-B66")
      (libsource (lib "eagle-import") (part "2DC-G213-B66"))
    )
    (comp (ref "U$23")
      (value "2DC-G213-B66")
      (footprint "eagle-import:2DC-G213-B66")
      (libsource (lib "eagle-import") (part "2DC-G213-B66"))
    )
    (comp (ref "U$24")
      (value "GHTOP4")
      (footprint "eagle-import:GHTOP4")
      (libsource (lib "eagle-import") (part "GHTOP4"))
    )
    (comp (ref "U$25")
      (value "RJ45")
      (footprint "eagle-import:RJ45")
      (libsource (lib "eagle-import") (part "RJ45"))
    )
    (comp (ref "U$26")
      (value "NJM2845DL1")
      (footprint "eagle-import:TO-252-3-L1")
      (libsource (lib "eagle-import") (part "NJM2845DL1"))
    )
    (comp (ref "U$27")
      (value "GHTOP4")
      (footprint "eagle-import:GHTOP4")
      (libsource (lib "eagle-import") (part "GHTOP4"))
    )
    (comp (ref "U$28")
      (value "DM3AT-SF-PEJ")
      (footprint "eagle-import:DM3AT-SF-PEJ")
      (libsource (lib "eagle-import") (part "DM3AT-SF-PEJ"))
    )
    (comp (ref "U$29")
      (value "GHTOP4")
      (footprint "eagle-import:GHTOP4")
      (libsource (lib "eagle-import") (part "GHTOP4"))
    )
    (comp (ref "U$30")
      (value "GHTOP4")
      (footprint "eagle-import:GHTOP4")
      (libsource (lib "eagle-import") (part "GHTOP4"))
    )
    (comp (ref "U$31")
      (value "FB1.25MM")
      (footprint "eagle-import:2012")
      (libsource (lib "eagle-import") (part "FB1.25MM"))
    )
    (comp (ref "U$32")
      (value "FB1.25MM")
      (footprint "eagle-import:2012")
      (libsource (lib "eagle-import") (part "FB1.25MM"))
    )
    (comp (ref "U$33")
      (value "FB1.25MM")
      (footprint "eagle-import:2012")
      (libsource (lib "eagle-import") (part "FB1.25MM"))
    )
    (comp (ref "U$34")
      (value "FB1.25MM")
      (footprint "eagle-import:2012")
      (libsource (lib "eagle-import") (part "FB1.25MM"))
    )
    (comp (ref "U$35")
      (value "FB1.25MM")
      (footprint "eagle-import:2012")
      (libsource (lib "eagle-import") (part "FB1.25MM"))
    )
    (comp (ref "U$36")
      (value "FB1.25MM")
      (footprint "eagle-import:2012")
      (libsource (lib "eagle-import") (part "FB1.25MM"))
    )
    (comp (ref "U$37")
      (value "FB1.25MM")
      (footprint "eagle-import:2012")
      (libsource (lib "eagle-import") (part "FB1.25MM"))
    )
    (comp (ref "U$38")
      (value "FB1.25MM")
      (footprint "eagle-import:2012")
      (libsource (lib "eagle-import") (part "FB1.25MM"))
    )
    (comp (ref "U$39")
      (value "FB1.25MM")
      (footprint "eagle-import:2012")
      (libsource (lib "eagle-import") (part "FB1.25MM"))
    )
    (comp (ref "U$40")
      (value "FB1.25MM")
      (footprint "eagle-import:2012")
      (libsource (lib "eagle-import") (part "FB1.25MM"))
    )
    (comp (ref "U$41")
      (value "FB1.25MM")
      (footprint "eagle-import:2012")
      (libsource (lib "eagle-import") (part "FB1.25MM"))
    )
    (comp (ref "U$42")
      (value "FB1.25MM")
      (footprint "eagle-import:2012")
      (libsource (lib "eagle-import") (part "FB1.25MM"))
    )
    (comp (ref "U$43")
      (value "FB1.25MM")
      (footprint "eagle-import:2012")
      (libsource (lib "eagle-import") (part "FB1.25MM"))
    )
    (comp (ref "U$44")
      (value "FB1.25MM")
      (footprint "eagle-import:2012")
      (libsource (lib "eagle-import") (part "FB1.25MM"))
    )
    (comp (ref "U$45")
      (value "FB1.25MM")
      (footprint "eagle-import:2012")
      (libsource (lib "eagle-import") (part "FB1.25MM"))
    )
    (comp (ref "U$46")
      (value "FB1.25MM")
      (footprint "eagle-import:2012")
      (libsource (lib "eagle-import") (part "FB1.25MM"))
    )
    (comp (ref "U$47")
      (value "FB1.25MM")
      (footprint "eagle-import:2012")
      (libsource (lib "eagle-import") (part "FB1.25MM"))
    )
    (comp (ref "U$48")
      (value "FB1.25MM")
      (footprint "eagle-import:2012")
      (libsource (lib "eagle-import") (part "FB1.25MM"))
    )
    (comp (ref "U$49")
      (value "FB1.25MM")
      (footprint "eagle-import:2012")
      (libsource (lib "eagle-import") (part "FB1.25MM"))
    )
    (comp (ref "U$50")
      (value "FB1.25MM")
      (footprint "eagle-import:2012")
      (libsource (lib "eagle-import") (part "FB1.25MM"))
    )
    (comp (ref "U$51")
      (value "FB1.25MM")
      (footprint "eagle-import:2012")
      (libsource (lib "eagle-import") (part "FB1.25MM"))
    )
    (comp (ref "U$52")
      (value "FB1.25MM")
      (footprint "eagle-import:2012")
      (libsource (lib "eagle-import") (part "FB1.25MM"))
    )
    (comp (ref "U$53")
      (value "FB1.25MM")
      (footprint "eagle-import:2012")
      (libsource (lib "eagle-import") (part "FB1.25MM"))
    )
    (comp (ref "U$54")
      (value "FB1.25MM")
      (footprint "eagle-import:2012")
      (libsource (lib "eagle-import") (part "FB1.25MM"))
    )
    (comp (ref "U$55")
      (value "FB1.25MM")
      (footprint "eagle-import:2012")
      (libsource (lib "eagle-import") (part "FB1.25MM"))
    )
    (comp (ref "U$56")
      (value "FB1.25MM")
      (footprint "eagle-import:2012")
      (libsource (lib "eagle-import") (part "FB1.25MM"))
    )
    (comp (ref "U$57")
      (value "DM3AT-SF-PEJ")
      (footprint "eagle-import:DM3AT-SF-PEJ")
      (libsource (lib "eagle-import") (part "DM3AT-SF-PEJ"))
    )
    (comp (ref "U$58")
      (value "FB1.25MM")
      (footprint "eagle-import:2012")
      (libsource (lib "eagle-import") (part "FB1.25MM"))
    )
    (comp (ref "U$59")
      (value "FB1.25MM")
      (footprint "eagle-import:2012")
      (libsource (lib "eagle-import") (part "FB1.25MM"))
    )
    (comp (ref "U$61")
      (value "FA238V")
      (footprint "eagle-import:FA238V")
      (libsource (lib "eagle-import") (part "FA238V"))
    )
    (comp (ref "U$62")
      (value "FA238V")
      (footprint "eagle-import:FA238V")
      (libsource (lib "eagle-import") (part "FA238V"))
    )
    (comp (ref "U$63")
      (value "USB-TYPEB")
      (footprint "eagle-import:USB-TYPEB")
      (libsource (lib "eagle-import") (part "USB-TYPEB"))
    )
    (comp (ref "U$64")
      (value "MCP2562")
      (footprint "eagle-import:MCP2562")
      (libsource (lib "eagle-import") (part "MCP2562"))
    )
    (comp (ref "U$65")
      (value "SC1602BBWB_PAD")
      (footprint "eagle-import:SC1602BBWB_PAD")
      (libsource (lib "eagle-import") (part "SC1602BBWB_PAD"))
    )
    (comp (ref "U$66")
      (value "TVBP06")
      (footprint "eagle-import:TVBP06")
      (libsource (lib "eagle-import") (part "TVBP06"))
    )
    (comp (ref "U$67")
      (value "USB_A")
      (footprint "eagle-import:USB_A")
      (libsource (lib "eagle-import") (part "USB_A"))
    )
    (comp (ref "U$68")
      (value "3STATE")
      (footprint "eagle-import:SOT23-5")
      (libsource (lib "eagle-import") (part "3STATE"))
    )
    (comp (ref "U$69")
      (value "TVBP06")
      (footprint "eagle-import:TVBP06")
      (libsource (lib "eagle-import") (part "TVBP06"))
    )
    (comp (ref "U$70")
      (value "TVBP06")
      (footprint "eagle-import:TVBP06")
      (libsource (lib "eagle-import") (part "TVBP06"))
    )
    (comp (ref "U$71")
      (value "TVBP06")
      (footprint "eagle-import:TVBP06")
      (libsource (lib "eagle-import") (part "TVBP06"))
    )
    (comp (ref "U$72")
      (value "TVBP06")
      (footprint "eagle-import:TVBP06")
      (libsource (lib "eagle-import") (part "TVBP06"))
    )
    (comp (ref "U$73")
      (value "TVBP06")
      (footprint "eagle-import:TVBP06")
      (libsource (lib "eagle-import") (part "TVBP06"))
    )
    (comp (ref "U$74")
      (value "TVBP06")
      (footprint "eagle-import:TVBP06")
      (libsource (lib "eagle-import") (part "TVBP06"))
    )
    (comp (ref "U$75")
      (value "USB_A")
      (footprint "eagle-import:USB_A")
      (libsource (lib "eagle-import") (part "USB_A"))
    )
    (comp (ref "U$76")
      (value "FB1.25MM")
      (footprint "eagle-import:2012")
      (libsource (lib "eagle-import") (part "FB1.25MM"))
    )
    (comp (ref "U$77")
      (value "USB_A")
      (footprint "eagle-import:USB_A")
      (libsource (lib "eagle-import") (part "USB_A"))
    )
    (comp (ref "U$78")
      (value "FB1.25MM")
      (footprint "eagle-import:2012")
      (libsource (lib "eagle-import") (part "FB1.25MM"))
    )
    (comp (ref "U$79")
      (value "KHS42")
      (footprint "eagle-import:KHS42")
      (libsource (lib "eagle-import") (part "KHS42"))
    )
    (comp (ref "U$80")
      (value "GHTOP4")
      (footprint "eagle-import:GHTOP4")
      (libsource (lib "eagle-import") (part "GHTOP4"))
    )
    (comp (ref "U$81")
      (value "TVBP06")
      (footprint "eagle-import:TVBP06")
      (libsource (lib "eagle-import") (part "TVBP06"))
    )
    (comp (ref "U$82")
      (value "SSSS2")
      (footprint "eagle-import:SSSS2")
      (libsource (lib "eagle-import") (part "SSSS2"))
    )
    (comp (ref "X2")
      (value "057-016-1")
      (footprint "eagle-import:057-016-1")
      (libsource (lib "eagle-import") (part "057-016-1"))
    )
    (comp (ref "X3")
      (value "057-010-1")
      (footprint "eagle-import:057-010-1")
      (libsource (lib "eagle-import") (part "057-010-1"))
    )
  )
  (nets
    (net (code "1") (name "+3V3") (class "Default")
      (node (ref "C24") (pin "1") (pinfunction "1_1") (pintype "passive"))
      (node (ref "C25") (pin "1") (pinfunction "1_1") (pintype "passive"))
      (node (ref "C29") (pin "1") (pinfunction "1_1") (pintype "passive"))
      (node (ref "C33") (pin "2") (pinfunction "2_2") (pintype "passive"))
      (node (ref "C35") (pin "2") (pinfunction "2_2") (pintype "passive"))
      (node (ref "C36") (pin "2") (pinfunction "2_2") (pintype "passive"))
      (node (ref "C41") (pin "2") (pinfunction "2_2") (pintype "passive"))
      (node (ref "C42") (pin "2") (pinfunction "2_2") (pintype "passive"))
      (node (ref "C44") (pin "2") (pinfunction "2_2") (pintype "passive"))
      (node (ref "C45") (pin "2") (pinfunction "2_2") (pintype "passive"))
      (node (ref "C46") (pin "1") (pinfunction "1_1") (pintype "passive"))
      (node (ref "C47") (pin "2") (pinfunction "2_2") (pintype "passive"))
      (node (ref "IC1") (pin "3") (pinfunction "VCC_3") (pintype "power_in"))
      (node (ref "IC3") (pin "3") (pinfunction "VCC_3") (pintype "power_in"))
      (node (ref "IC5") (pin "16") (pinfunction "VCC_16") (pintype "passive"))
      (node (ref "IC6") (pin "10") (pinfunction "RB12_10") (pintype "bidirectional"))
      (node (ref "IC6") (pin "17") (pinfunction "AVDD_17") (pintype "power_in"))
      (node (ref "IC6") (pin "28") (pinfunction "VDD_28") (pintype "power_in"))
      (node (ref "IC6") (pin "40") (pinfunction "VDD_40") (pintype "power_in"))
      (node (ref "IC7") (pin "10") (pinfunction "RB12_10") (pintype "bidirectional"))
      (node (ref "IC7") (pin "17") (pinfunction "AVDD_17") (pintype "power_in"))
      (node (ref "IC7") (pin "28") (pinfunction "VDD_28") (pintype "power_in"))
      (node (ref "IC7") (pin "40") (pinfunction "VDD_40") (pintype "power_in"))
      (node (ref "JP1") (pin "5") (pinfunction "5_5") (pintype "passive"))
      (node (ref "JP5") (pin "4") (pinfunction "4_4") (pintype "passive"))
      (node (ref "JP6") (pin "4") (pinfunction "4_4") (pintype "passive"))
      (node (ref "JP8") (pin "5") (pinfunction "5_5") (pintype "passive"))
      (node (ref "MCU1") (pin "1") (pinfunction "VCC_1") (pintype "power_in"))
      (node (ref "MCU1") (pin "14") (pinfunction "VCC_14") (pintype "power_in"))
      (node (ref "MCU1") (pin "29") (pinfunction "PLLVCC_29") (pintype "power_in"))
      (node (ref "MCU1") (pin "30") (pinfunction "P16/USB0_VBUS_30") (pintype "bidirectional"))
      (node (ref "MCU1") (pin "35") (pinfunction "VCC_USB_35") (pintype "power_in"))
      (node (ref "MCU1") (pin "60") (pinfunction "VCC_60") (pintype "power_in"))
      (node (ref "MCU1") (pin "96") (pinfunction "VREFH_96") (pintype "power_in"))
      (node (ref "MCU1") (pin "97") (pinfunction "AVCC_97") (pintype "power_in"))
      (node (ref "R10") (pin "2") (pinfunction "2_2") (pintype "passive"))
      (node (ref "R14") (pin "1") (pinfunction "1_1") (pintype "passive"))
      (node (ref "R15") (pin "2") (pinfunction "2_2") (pintype "passive"))
      (node (ref "R16") (pin "2") (pinfunction "2_2") (pintype "passive"))
      (node (ref "R17") (pin "2") (pinfunction "2_2") (pintype "passive"))
      (node (ref "R18") (pin "2") (pinfunction "2_2") (pintype "passive"))
      (node (ref "R19") (pin "2") (pinfunction "2_2") (pintype "passive"))
      (node (ref "R20") (pin "2") (pinfunction "2_2") (pintype "passive"))
      (node (ref "R21") (pin "2") (pinfunction "2_2") (pintype "passive"))
      (node (ref "R22") (pin "2") (pinfunction "2_2") (pintype "passive"))
      (node (ref "R23") (pin "2") (pinfunction "2_2") (pintype "passive"))
      (node (ref "R24") (pin "2") (pinfunction "2_2") (pintype "passive"))
      (node (ref "R25") (pin "2") (pinfunction "2_2") (pintype "passive"))
      (node (ref "R26") (pin "2") (pinfunction "2_2") (pintype "passive"))
      (node (ref "R33") (pin "2") (pinfunction "2_2") (pintype "passive"))
      (node (ref "R34") (pin "2") (pinfunction "2_2") (pintype "passive"))
      (node (ref "R39") (pin "1") (pinfunction "1_1") (pintype "passive"))
      (node (ref "R40") (pin "1") (pinfunction "1_1") (pintype "passive"))
      (node (ref "R44") (pin "2") (pinfunction "2_2") (pintype "passive"))
      (node (ref "R45") (pin "2") (pinfunction "2_2") (pintype "passive"))
      (node (ref "R46") (pin "2") (pinfunction "2_2") (pintype "passive"))
      (node (ref "R47") (pin "1") (pinfunction "1_1") (pintype "passive"))
      (node (ref "R48") (pin "1") (pinfunction "1_1") (pintype "passive"))
      (node (ref "R5") (pin "1") (pinfunction "1_1") (pintype "passive"))
      (node (ref "R53") (pin "1") (pinfunction "1_1") (pintype "passive"))
      (node (ref "R54") (pin "1") (pinfunction "1_1") (pintype "passive"))
      (node (ref "R55") (pin "1") (pinfunction "1_1") (pintype "passive"))
      (node (ref "R56") (pin "1") (pinfunction "1_1") (pintype "passive"))
      (node (ref "R57") (pin "2") (pinfunction "2_2") (pintype "passive"))
      (node (ref "R58") (pin "2") (pinfunction "2_2") (pintype "passive"))
      (node (ref "R59") (pin "2") (pinfunction "2_2") (pintype "passive"))
      (node (ref "R60") (pin "1") (pinfunction "1_1") (pintype "passive"))
      (node (ref "R61") (pin "1") (pinfunction "1_1") (pintype "passive"))
      (node (ref "R62") (pin "1") (pinfunction "1_1") (pintype "passive"))
      (node (ref "R63") (pin "1") (pinfunction "1_1") (pintype "passive"))
      (node (ref "R7") (pin "2") (pinfunction "2_2") (pintype "passive"))
      (node (ref "R8") (pin "1") (pinfunction "1_1") (pintype "passive"))
      (node (ref "R_MD3") (pin "2") (pinfunction "2_2") (pintype "passive"))
      (node (ref "R_MD4") (pin "1") (pinfunction "1_1") (pintype "passive"))
      (node (ref "R_NMI") (pin "1") (pinfunction "1_1") (pintype "passive"))
      (node (ref "U$17") (pin "5") (pinfunction "VIO_5") (pintype "power_in"))
      (node (ref "U$19") (pin "5") (pinfunction "VIO_5") (pintype "power_in"))
      (node (ref "U$2") (pin "2") (pinfunction "2_2") (pintype "passive"))
      (node (ref "U$26") (pin "3") (pinfunction "OUT_3") (pintype "power_in"))
      (node (ref "U$4") (pin "1") (pinfunction "VREFH_1") (pintype "bidirectional"))
      (node (ref "U$4") (pin "14") (pinfunction "VCC_14") (pintype "bidirectional"))
      (node (ref "U$4") (pin "35") (pinfunction "VCC_USB_35") (pintype "bidirectional"))
      (node (ref "U$4") (pin "6") (pinfunction "VBATT_6") (pintype "bidirectional"))
      (node (ref "U$4") (pin "60") (pinfunction "VCC_60") (pintype "bidirectional"))
      (node (ref "U$4") (pin "96") (pinfunction "VREFH0_96") (pintype "bidirectional"))
      (node (ref "U$4") (pin "97") (pinfunction "AVCC0_97") (pintype "bidirectional"))
      (node (ref "U$58") (pin "2") (pinfunction "2_2") (pintype "passive"))
      (node (ref "U$64") (pin "5") (pinfunction "VIO_5") (pintype "power_in"))
      (node (ref "U$68") (pin "5") (pinfunction "V_5") (pintype "bidirectional"))
      (node (ref "U$80") (pin "1") (pinfunction "1_1") (pintype "bidirectional"))
      (node (ref "X2") (pin "1") (pinfunction "S_1") (pintype "passive"))
      (node (ref "X3") (pin "1") (pinfunction "S_1") (pintype "passive"))
    )
    (net (code "2") (name "/621-AN0") (class "Default")
      (node (ref "MCU1") (pin "95") (pinfunction "AN0_95") (pintype "bidirectional"))
      (node (ref "U$54") (pin "2") (pinfunction "2_2") (pintype "passive"))
    )
    (net (code "3") (name "/621-AN1") (class "Default")
      (node (ref "MCU1") (pin "93") (pinfunction "AN1_93") (pintype "bidirectional"))
      (node (ref "U$53") (pin "2") (pinfunction "2_2") (pintype "passive"))
    )
    (net (code "4") (name "/621-AN2") (class "Default")
      (node (ref "MCU1") (pin "92") (pinfunction "AN2_92") (pintype "bidirectional"))
      (node (ref "U$52") (pin "2") (pinfunction "2_2") (pintype "passive"))
    )
    (net (code "5") (name "/621-AN3") (class "Default")
      (node (ref "MCU1") (pin "91") (pinfunction "AN3_91") (pintype "bidirectional"))
      (node (ref "U$51") (pin "2") (pinfunction "2_2") (pintype "passive"))
    )
    (net (code "6") (name "/621-AN4") (class "Default")
      (node (ref "MCU1") (pin "90") (pinfunction "AN4_90") (pintype "bidirectional"))
      (node (ref "U$50") (pin "2") (pinfunction "2_2") (pintype "passive"))
    )
    (net (code "7") (name "/621-AN5") (class "Default")
      (node (ref "MCU1") (pin "89") (pinfunction "AN5_89") (pintype "bidirectional"))
      (node (ref "U$49") (pin "2") (pinfunction "2_2") (pintype "passive"))
    )
    (net (code "8") (name "/621-AN6") (class "Default")
      (node (ref "MCU1") (pin "88") (pinfunction "AN6_88") (pintype "bidirectional"))
      (node (ref "U$48") (pin "2") (pinfunction "2_2") (pintype "passive"))
    )
    (net (code "9") (name "/621-AN7") (class "Default")
      (node (ref "MCU1") (pin "87") (pinfunction "AN7_87") (pintype "bidirectional"))
      (node (ref "U$47") (pin "2") (pinfunction "2_2") (pintype "passive"))
    )
    (net (code "10") (name "/621-CRX0") (class "Default")
      (node (ref "MCU1") (pin "17") (pinfunction "P33/MTIOC0D_17") (pintype "bidirectional"))
      (node (ref "U$64") (pin "4") (pinfunction "RXD_4") (pintype "bidirectional"))
    )
    (net (code "11") (name "/621-CTX0") (class "Default")
      (node (ref "MCU1") (pin "18") (pinfunction "P32/MTIOC0C_18") (pintype "bidirectional"))
      (node (ref "U$64") (pin "1") (pinfunction "TXD_1") (pintype "bidirectional"))
    )
    (net (code "12") (name "/621-EXTAL") (class "Default")
      (node (ref "C22") (pin "1") (pinfunction "1_1") (pintype "passive"))
      (node (ref "MCU1") (pin "13") (pinfunction "EXTAL_13") (pintype "input"))
      (node (ref "U$62") (pin "1") (pinfunction "1_1") (pintype "bidirectional"))
    )
    (net (code "13") (name "/621-MD0") (class "Default")
      (node (ref "MCU1") (pin "7") (pinfunction "MD0_7") (pintype "input"))
      (node (ref "R8") (pin "2") (pinfunction "2_2") (pintype "passive"))
    )
    (net (code "14") (name "/621-MTCLKA-B") (class "Default")
      (node (ref "MCU1") (pin "46") (pinfunction "PC6/MTCLKA-B_46") (pintype "bidirectional"))
      (node (ref "U$16") (pin "2") (pinfunction "2_2") (pintype "passive"))
    )
    (net (code "15") (name "/621-MTCLKA-B-C") (class "Default")
      (node (ref "C20") (pin "1") (pinfunction "1_1") (pintype "passive"))
      (node (ref "D12") (pin "A") (pinfunction "A_A") (pintype "passive"))
      (node (ref "R25") (pin "1") (pinfunction "1_1") (pintype "passive"))
      (node (ref "U$16") (pin "1") (pinfunction "1_1") (pintype "passive"))
    )
    (net (code "16") (name "/621-MTCLKB-B") (class "Default")
      (node (ref "MCU1") (pin "45") (pinfunction "PC7/MTCLKB-B_45") (pintype "bidirectional"))
      (node (ref "U$31") (pin "2") (pinfunction "2_2") (pintype "passive"))
    )
    (net (code "17") (name "/621-MTCLKB-B-C") (class "Default")
      (node (ref "C19") (pin "1") (pinfunction "1_1") (pintype "passive"))
      (node (ref "D13") (pin "A") (pinfunction "A_A") (pintype "passive"))
      (node (ref "R26") (pin "1") (pinfunction "1_1") (pintype "passive"))
      (node (ref "U$31") (pin "1") (pinfunction "1_1") (pintype "passive"))
    )
    (net (code "18") (name "/621-MTCLKC-B") (class "Default")
      (node (ref "MCU1") (pin "48") (pinfunction "PC4/MTCLKC-B_48") (pintype "bidirectional"))
      (node (ref "U$12") (pin "2") (pinfunction "2_2") (pintype "passive"))
    )
    (net (code "19") (name "/621-MTCLKC-B-C") (class "Default")
      (node (ref "C18") (pin "1") (pinfunction "1_1") (pintype "passive"))
      (node (ref "D10") (pin "A") (pinfunction "A_A") (pintype "passive"))
      (node (ref "R23") (pin "1") (pinfunction "1_1") (pintype "passive"))
      (node (ref "U$12") (pin "1") (pinfunction "1_1") (pintype "passive"))
    )
    (net (code "20") (name "/621-MTCLKD-B") (class "Default")
      (node (ref "MCU1") (pin "47") (pinfunction "PC5/MTCLKD-B_47") (pintype "bidirectional"))
      (node (ref "U$13") (pin "2") (pinfunction "2_2") (pintype "passive"))
    )
    (net (code "21") (name "/621-MTCLKD-B-C") (class "Default")
      (node (ref "C15") (pin "1") (pinfunction "1_1") (pintype "passive"))
      (node (ref "D11") (pin "A") (pinfunction "A_A") (pintype "passive"))
      (node (ref "R24") (pin "1") (pinfunction "1_1") (pintype "passive"))
      (node (ref "U$13") (pin "1") (pinfunction "1_1") (pintype "passive"))
    )
    (net (code "22") (name "/621-MTCLKE-A") (class "Default")
      (node (ref "MCU1") (pin "50") (pinfunction "PC2/MTCLKE-A_50") (pintype "bidirectional"))
      (node (ref "U$10") (pin "2") (pinfunction "2_2") (pintype "passive"))
    )
    (net (code "23") (name "/621-MTCLKE-A-C") (class "Default")
      (node (ref "C7") (pin "1") (pinfunction "1_1") (pintype "passive"))
      (node (ref "D8") (pin "A") (pinfunction "A_A") (pintype "passive"))
      (node (ref "R17") (pin "1") (pinfunction "1_1") (pintype "passive"))
      (node (ref "U$10") (pin "1") (pinfunction "1_1") (pintype "passive"))
    )
    (net (code "24") (name "/621-MTCLKF-A") (class "Default")
      (node (ref "MCU1") (pin "49") (pinfunction "PC3/MTCLKF-A_49") (pintype "bidirectional"))
      (node (ref "U$11") (pin "2") (pinfunction "2_2") (pintype "passive"))
    )
    (net (code "25") (name "/621-MTCLKF-A-C") (class "Default")
      (node (ref "C6") (pin "1") (pinfunction "1_1") (pintype "passive"))
      (node (ref "D9") (pin "A") (pinfunction "A_A") (pintype "passive"))
      (node (ref "R22") (pin "1") (pinfunction "1_1") (pintype "passive"))
      (node (ref "U$11") (pin "1") (pinfunction "1_1") (pintype "passive"))
    )
    (net (code "26") (name "/621-MTCLKG-A") (class "Default")
      (node (ref "MCU1") (pin "52") (pinfunction "PC0/MTCLKG-A_52") (pintype "bidirectional"))
      (node (ref "U$3") (pin "2") (pinfunction "2_2") (pintype "passive"))
    )
    (net (code "27") (name "/621-MTCLKG-A-C") (class "Default")
      (node (ref "C3") (pin "1") (pinfunction "1_1") (pintype "passive"))
      (node (ref "D6") (pin "A") (pinfunction "A_A") (pintype "passive"))
      (node (ref "R15") (pin "1") (pinfunction "1_1") (pintype "passive"))
      (node (ref "U$3") (pin "1") (pinfunction "1_1") (pintype "passive"))
    )
    (net (code "28") (name "/621-MTCLKH-A") (class "Default")
      (node (ref "MCU1") (pin "51") (pinfunction "PC1/MTCLKH-A_51") (pintype "bidirectional"))
      (node (ref "U$5") (pin "2") (pinfunction "2_2") (pintype "passive"))
    )
    (net (code "29") (name "/621-MTCLKH-A-C") (class "Default")
      (node (ref "C2") (pin "1") (pinfunction "1_1") (pintype "passive"))
      (node (ref "D7") (pin "A") (pinfunction "A_A") (pintype "passive"))
      (node (ref "R16") (pin "1") (pinfunction "1_1") (pintype "passive"))
      (node (ref "U$5") (pin "1") (pinfunction "1_1") (pintype "passive"))
    )
    (net (code "30") (name "/621-PA2") (class "Default")
      (node (ref "LED14") (pin "A") (pinfunction "A_A") (pintype "passive"))
      (node (ref "MCU1") (pin "68") (pinfunction "PA2/MTIOC6C_68") (pintype "bidirectional"))
    )
    (net (code "31") (name "/621-PA3") (class "Default")
      (node (ref "LED13") (pin "A") (pinfunction "A_A") (pintype "passive"))
      (node (ref "MCU1") (pin "67") (pinfunction "PA3/MTIOC6D_67") (pintype "bidirectional"))
    )
    (net (code "32") (name "/621-PA4") (class "Default")
      (node (ref "LED7") (pin "A") (pinfunction "A_A") (pintype "passive"))
      (node (ref "MCU1") (pin "66") (pinfunction "PA4/MTIOC7A_66") (pintype "bidirectional"))
    )
    (net (code "33") (name "/621-PA5") (class "Default")
      (node (ref "LED6") (pin "A") (pinfunction "A_A") (pintype "passive"))
      (node (ref "MCU1") (pin "65") (pinfunction "PA5/MTIOC7B_65") (pintype "bidirectional"))
    )
    (net (code "34") (name "/621-PA6") (class "Default")
      (node (ref "LED5") (pin "A") (pinfunction "A_A") (pintype "passive"))
      (node (ref "MCU1") (pin "64") (pinfunction "PA6/MTIOC8A_64") (pintype "bidirectional"))
    )
    (net (code "35") (name "/621-PA7") (class "Default")
      (node (ref "LED4") (pin "A") (pinfunction "A_A") (pintype "passive"))
      (node (ref "MCU1") (pin "63") (pinfunction "PA7/MTIOC8B_63") (pintype "bidirectional"))
    )
    (net (code "36") (name "/621-PB4") (class "Default")
      (node (ref "MCU1") (pin "56") (pinfunction "PB4/MTIOC10A/MTCLKE-B_56") (pintype "bidirectional"))
      (node (ref "R48") (pin "2") (pinfunction "2_2") (pintype "passive"))
      (node (ref "U$79") (pin "4") (pinfunction "4_4") (pintype "bidirectional"))
    )
    (net (code "37") (name "/621-PB5") (class "Default")
      (node (ref "MCU1") (pin "55") (pinfunction "PB5/MTIOC10C/MTCLKF-B_55") (pintype "bidirectional"))
      (node (ref "R47") (pin "2") (pinfunction "2_2") (pintype "passive"))
      (node (ref "U$79") (pin "3") (pinfunction "3_3") (pintype "bidirectional"))
    )
    (net (code "38") (name "/621-PB6") (class "Default")
      (node (ref "MCU1") (pin "54") (pinfunction "PB6/MTIOC10B_54") (pintype "bidirectional"))
      (node (ref "R46") (pin "1") (pinfunction "1_1") (pintype "passive"))
      (node (ref "U$79") (pin "2") (pinfunction "2_2") (pintype "bidirectional"))
    )
    (net (code "39") (name "/621-PB7") (class "Default")
      (node (ref "MCU1") (pin "53") (pinfunction "PB7/MTIOC10D_53") (pintype "bidirectional"))
      (node (ref "R45") (pin "1") (pinfunction "1_1") (pintype "passive"))
      (node (ref "U$79") (pin "1") (pinfunction "1_1") (pintype "bidirectional"))
    )
    (net (code "40") (name "/621-PD0") (class "Default")
      (node (ref "MCU1") (pin "86") (pinfunction "PD0_86") (pintype "bidirectional"))
      (node (ref "R60") (pin "2") (pinfunction "2_2") (pintype "passive"))
      (node (ref "U$81") (pin "2") (pinfunction "2_2") (pintype "bidirectional"))
    )
    (net (code "41") (name "/621-PD1") (class "Default")
      (node (ref "MCU1") (pin "85") (pinfunction "PD1_85") (pintype "bidirectional"))
      (node (ref "R61") (pin "2") (pinfunction "2_2") (pintype "passive"))
      (node (ref "U$74") (pin "2") (pinfunction "2_2") (pintype "bidirectional"))
    )
    (net (code "42") (name "/621-PD2") (class "Default")
      (node (ref "MCU1") (pin "84") (pinfunction "PD2_84") (pintype "bidirectional"))
      (node (ref "R62") (pin "2") (pinfunction "2_2") (pintype "passive"))
      (node (ref "U$73") (pin "2") (pinfunction "2_2") (pintype "bidirectional"))
    )
    (net (code "43") (name "/621-PD3") (class "Default")
      (node (ref "MCU1") (pin "83") (pinfunction "PD3_83") (pintype "bidirectional"))
      (node (ref "R63") (pin "2") (pinfunction "2_2") (pintype "passive"))
      (node (ref "U$72") (pin "2") (pinfunction "2_2") (pintype "bidirectional"))
    )
    (net (code "44") (name "/621-RESET") (class "Default")
      (node (ref "MCU1") (pin "10") (pinfunction "~{RES}_10") (pintype "input"))
      (node (ref "R36") (pin "2") (pinfunction "2_2") (pintype "passive"))
      (node (ref "U$8") (pin "A") (pinfunction "A_A") (pintype "bidirectional"))
      (node (ref "U$8") (pin "B") (pinfunction "B_B") (pintype "bidirectional"))
    )
    (net (code "45") (name "/621-RXD0") (class "Default")
      (node (ref "IC5") (pin "12") (pinfunction "R1OUT_12") (pintype "output"))
      (node (ref "MCU1") (pin "27") (pinfunction "P21/RXD0_27") (pintype "bidirectional"))
    )
    (net (code "46") (name "/621-RXD1") (class "Default")
      (node (ref "IC2") (pin "1") (pinfunction "TXD_1") (pintype "output"))
      (node (ref "MCU1") (pin "20") (pinfunction "P30/MTIOC4B-A/RXD1_20") (pintype "bidirectional"))
    )
    (net (code "47") (name "/621-RXD2-B") (class "Default")
      (node (ref "IC7") (pin "2") (pinfunction "RC6_2") (pintype "bidirectional"))
      (node (ref "MCU1") (pin "42") (pinfunction "P52_42") (pintype "bidirectional"))
    )
    (net (code "48") (name "/621-RXD3") (class "Default")
      (node (ref "JP8") (pin "1") (pinfunction "1_1") (pintype "passive"))
      (node (ref "MCU1") (pin "23") (pinfunction "P25/MTCLKB-A_23") (pintype "bidirectional"))
    )
    (net (code "49") (name "/621-TXD0") (class "Default")
      (node (ref "IC5") (pin "11") (pinfunction "T1IN_11") (pintype "input"))
      (node (ref "MCU1") (pin "28") (pinfunction "P20/TXD0_28") (pintype "bidirectional"))
    )
    (net (code "50") (name "/621-TXD1") (class "Default")
      (node (ref "MCU1") (pin "22") (pinfunction "P26/MTIOC2A/TXD1_22") (pintype "bidirectional"))
      (node (ref "R37") (pin "2") (pinfunction "2_2") (pintype "passive"))
    )
    (net (code "51") (name "/621-TXD2-B") (class "Default")
      (node (ref "IC7") (pin "3") (pinfunction "RC7_3") (pintype "bidirectional"))
      (node (ref "MCU1") (pin "44") (pinfunction "P50_44") (pintype "bidirectional"))
    )
    (net (code "52") (name "/621-TXD3") (class "Default")
      (node (ref "JP8") (pin "2") (pinfunction "2_2") (pintype "passive"))
      (node (ref "MCU1") (pin "25") (pinfunction "P23/MTCLKD-A_25") (pintype "bidirectional"))
    )
    (net (code "53") (name "/621-USB0_DM_I") (class "Default")
      (node (ref "MCU1") (pin "36") (pinfunction "USB0_DM_36") (pintype "bidirectional"))
      (node (ref "R42") (pin "2") (pinfunction "2_2") (pintype "passive"))
    )
    (net (code "54") (name "/621-USB0_DP_I") (class "Default")
      (node (ref "MCU1") (pin "37") (pinfunction "USB0_DP_37") (pintype "bidirectional"))
      (node (ref "R41") (pin "2") (pinfunction "2_2") (pintype "passive"))
    )
    (net (code "55") (name "/621-VCL") (class "Default")
      (node (ref "C1") (pin "2") (pinfunction "2_2") (pintype "passive"))
      (node (ref "MCU1") (pin "5") (pinfunction "VCL_5") (pintype "input"))
    )
    (net (code "56") (name "/621-XCIN") (class "Default")
      (node (ref "MCU1") (pin "8") (pinfunction "XCIN_8") (pintype "input"))
      (node (ref "R14") (pin "2") (pinfunction "2_2") (pintype "passive"))
    )
    (net (code "57") (name "/621-XTAL") (class "Default")
      (node (ref "C21") (pin "2") (pinfunction "2_2") (pintype "passive"))
      (node (ref "MCU1") (pin "11") (pinfunction "XTAL_11") (pintype "output"))
      (node (ref "U$62") (pin "3") (pinfunction "3_3") (pintype "bidirectional"))
    )
    (net (code "58") (name "/631-AN000") (class "Default")
      (node (ref "U$33") (pin "2") (pinfunction "2_2") (pintype "passive"))
      (node (ref "U$4") (pin "95") (pinfunction "P40/AN000_95") (pintype "bidirectional"))
    )
    (net (code "59") (name "/631-AN001") (class "Default")
      (node (ref "U$34") (pin "2") (pinfunction "2_2") (pintype "passive"))
      (node (ref "U$4") (pin "93") (pinfunction "P41/AN001_93") (pintype "bidirectional"))
    )
    (net (code "60") (name "/631-AN002") (class "Default")
      (node (ref "U$35") (pin "2") (pinfunction "2_2") (pintype "passive"))
      (node (ref "U$4") (pin "92") (pinfunction "P42/AN002_92") (pintype "bidirectional"))
    )
    (net (code "61") (name "/631-AN003") (class "Default")
      (node (ref "U$36") (pin "2") (pinfunction "2_2") (pintype "passive"))
      (node (ref "U$4") (pin "91") (pinfunction "P43/AN003_91") (pintype "bidirectional"))
    )
    (net (code "62") (name "/631-AN004") (class "Default")
      (node (ref "U$37") (pin "2") (pinfunction "2_2") (pintype "passive"))
      (node (ref "U$4") (pin "90") (pinfunction "P44/AN004_90") (pintype "bidirectional"))
    )
    (net (code "63") (name "/631-AN005") (class "Default")
      (node (ref "U$38") (pin "2") (pinfunction "2_2") (pintype "passive"))
      (node (ref "U$4") (pin "89") (pinfunction "P45/AN005_89") (pintype "bidirectional"))
    )
    (net (code "64") (name "/631-AN006") (class "Default")
      (node (ref "U$39") (pin "2") (pinfunction "2_2") (pintype "passive"))
      (node (ref "U$4") (pin "88") (pinfunction "P46/AN006_88") (pintype "bidirectional"))
    )
    (net (code "65") (name "/631-AN007") (class "Default")
      (node (ref "U$4") (pin "87") (pinfunction "P47/AN007_87") (pintype "bidirectional"))
      (node (ref "U$40") (pin "2") (pinfunction "2_2") (pintype "passive"))
    )
    (net (code "66") (name "/631-AN008") (class "Default")
      (node (ref "U$4") (pin "86") (pinfunction "PD0/AN008_86") (pintype "bidirectional"))
      (node (ref "U$41") (pin "2") (pinfunction "2_2") (pintype "passive"))
    )
    (net (code "67") (name "/631-AN009") (class "Default")
      (node (ref "U$4") (pin "85") (pinfunction "PD1/MTIOC4B/CTX0/AN009_85") (pintype "bidirectional"))
      (node (ref "U$42") (pin "2") (pinfunction "2_2") (pintype "passive"))
    )
    (net (code "68") (name "/631-AN010") (class "Default")
      (node (ref "U$4") (pin "84") (pinfunction "PD2/MTIOC4D/CRX0/AN010_84") (pintype "bidirectional"))
      (node (ref "U$43") (pin "2") (pinfunction "2_2") (pintype "passive"))
    )
    (net (code "69") (name "/631-AN011") (class "Default")
      (node (ref "U$4") (pin "83") (pinfunction "PD3/AN011_83") (pintype "bidirectional"))
      (node (ref "U$44") (pin "2") (pinfunction "2_2") (pintype "passive"))
    )
    (net (code "70") (name "/631-AN012") (class "Default")
      (node (ref "U$4") (pin "82") (pinfunction "PD4/AN012_82") (pintype "bidirectional"))
      (node (ref "U$45") (pin "2") (pinfunction "2_2") (pintype "passive"))
    )
    (net (code "71") (name "/631-AN013") (class "Default")
      (node (ref "U$4") (pin "81") (pinfunction "PD5/AN013_81") (pintype "bidirectional"))
      (node (ref "U$46") (pin "2") (pinfunction "2_2") (pintype "passive"))
    )
    (net (code "72") (name "/631-CRX0") (class "Default")
      (node (ref "U$19") (pin "4") (pinfunction "RXD_4") (pintype "bidirectional"))
      (node (ref "U$4") (pin "17") (pinfunction "P33/MTIOC0D/RXD6/RXD0/CRX0_17") (pintype "bidirectional"))
    )
    (net (code "73") (name "/631-CRX1") (class "Default")
      (node (ref "U$17") (pin "4") (pinfunction "RXD_4") (pintype "bidirectional"))
      (node (ref "U$4") (pin "39") (pinfunction "P55/MTIOC4D/CRX1_39") (pintype "bidirectional"))
    )
    (net (code "74") (name "/631-CTX0") (class "Default")
      (node (ref "U$19") (pin "1") (pinfunction "TXD_1") (pintype "bidirectional"))
      (node (ref "U$4") (pin "18") (pinfunction "P32/MTIOC0C/TXD6/TXD0/CTX0_18") (pintype "bidirectional"))
    )
    (net (code "75") (name "/631-CTX1") (class "Default")
      (node (ref "U$17") (pin "1") (pinfunction "TXD_1") (pintype "bidirectional"))
      (node (ref "U$4") (pin "40") (pinfunction "P54/MTIOC4B/CTX1_40") (pintype "bidirectional"))
    )
    (net (code "76") (name "/631-EXTAL") (class "Default")
      (node (ref "C8") (pin "1") (pinfunction "1_1") (pintype "passive"))
      (node (ref "U$4") (pin "13") (pinfunction "P36/EXTAL_13") (pintype "bidirectional"))
      (node (ref "U$61") (pin "1") (pinfunction "1_1") (pintype "bidirectional"))
    )
    (net (code "77") (name "/631-MD{slash}621-MD1") (class "Default")
      (node (ref "LED12") (pin "C") (pinfunction "C_C") (pintype "passive"))
      (node (ref "MCU1") (pin "6") (pinfunction "MD1_6") (pintype "input"))
      (node (ref "SJ4") (pin "2") (pinfunction "2_2") (pintype "passive"))
      (node (ref "U$4") (pin "7") (pinfunction "MD/FINED_7") (pintype "bidirectional"))
      (node (ref "U$68") (pin "4") (pinfunction "O_4") (pintype "tri_state"))
    )
    (net (code "78") (name "/631-MISOA") (class "Default")
      (node (ref "R4") (pin "1") (pinfunction "1_1") (pintype "passive"))
      (node (ref "U$4") (pin "63") (pinfunction "PA7_63") (pintype "bidirectional"))
    )
    (net (code "79") (name "/631-MISOB") (class "Default")
      (node (ref "MCU1") (pin "71") (pinfunction "PE7/IRQ7_71") (pintype "bidirectional"))
      (node (ref "U$1") (pin "4") (pinfunction "4_4") (pintype "bidirectional"))
      (node (ref "U$4") (pin "71") (pinfunction "PE7/AN5_71") (pintype "bidirectional"))
    )
    (net (code "80") (name "/631-MOSIA") (class "Default")
      (node (ref "U$28") (pin "3") (pinfunction "DI_3") (pintype "bidirectional"))
      (node (ref "U$4") (pin "64") (pinfunction "PA6/MTCLKB_64") (pintype "bidirectional"))
    )
    (net (code "81") (name "/631-MOSIB") (class "Default")
      (node (ref "MCU1") (pin "72") (pinfunction "PE6/IRQ6-A_72") (pintype "bidirectional"))
      (node (ref "U$1") (pin "3") (pinfunction "3_3") (pintype "bidirectional"))
      (node (ref "U$4") (pin "72") (pinfunction "PE6/AN4_72") (pintype "bidirectional"))
    )
    (net (code "82") (name "/631-MTCLKA") (class "Default")
      (node (ref "U$32") (pin "2") (pinfunction "2_2") (pintype "passive"))
      (node (ref "U$4") (pin "32") (pinfunction "P14/MTIOC3A/MTCLKA/CTX1_32") (pintype "bidirectional"))
    )
    (net (code "83") (name "/631-MTCLKA-C") (class "Default")
      (node (ref "C13") (pin "1") (pinfunction "1_1") (pintype "passive"))
      (node (ref "D4") (pin "A") (pinfunction "A_A") (pintype "passive"))
      (node (ref "R18") (pin "1") (pinfunction "1_1") (pintype "passive"))
      (node (ref "U$32") (pin "1") (pinfunction "1_1") (pintype "passive"))
    )
    (net (code "84") (name "/631-MTCLKB") (class "Default")
      (node (ref "U$4") (pin "31") (pinfunction "P15/MTIOC0B/MTCLKB/RXD1/SCK3_31") (pintype "bidirectional"))
      (node (ref "U$55") (pin "2") (pinfunction "2_2") (pintype "passive"))
    )
    (net (code "85") (name "/631-MTCLKB-C") (class "Default")
      (node (ref "C12") (pin "1") (pinfunction "1_1") (pintype "passive"))
      (node (ref "D5") (pin "A") (pinfunction "A_A") (pintype "passive"))
      (node (ref "R19") (pin "1") (pinfunction "1_1") (pintype "passive"))
      (node (ref "U$55") (pin "1") (pinfunction "1_1") (pintype "passive"))
    )
    (net (code "86") (name "/631-MTCLKC") (class "Default")
      (node (ref "U$4") (pin "48") (pinfunction "PC4/MTIOC3D/MTCLKC/SCK5_48") (pintype "bidirectional"))
      (node (ref "U$56") (pin "2") (pinfunction "2_2") (pintype "passive"))
    )
    (net (code "87") (name "/631-MTCLKC-C") (class "Default")
      (node (ref "C17") (pin "1") (pinfunction "1_1") (pintype "passive"))
      (node (ref "D2") (pin "A") (pinfunction "A_A") (pintype "passive"))
      (node (ref "R20") (pin "1") (pinfunction "1_1") (pintype "passive"))
      (node (ref "U$56") (pin "1") (pinfunction "1_1") (pintype "passive"))
    )
    (net (code "88") (name "/631-MTCLKD") (class "Default")
      (node (ref "U$4") (pin "47") (pinfunction "PC5/MTIOC3B/MTCLKD/SCK8_47") (pintype "bidirectional"))
      (node (ref "U$59") (pin "2") (pinfunction "2_2") (pintype "passive"))
    )
    (net (code "89") (name "/631-MTCLKD-C") (class "Default")
      (node (ref "C14") (pin "1") (pinfunction "1_1") (pintype "passive"))
      (node (ref "D3") (pin "A") (pinfunction "A_A") (pintype "passive"))
      (node (ref "R21") (pin "1") (pinfunction "1_1") (pintype "passive"))
      (node (ref "U$59") (pin "1") (pinfunction "1_1") (pintype "passive"))
    )
    (net (code "90") (name "/631-NMI") (class "Default")
      (node (ref "R_NMI") (pin "2") (pinfunction "2_2") (pintype "passive"))
      (node (ref "U$4") (pin "15") (pinfunction "P35/NMI_15") (pintype "bidirectional"))
    )
    (net (code "91") (name "/631-P17") (class "Default")
      (node (ref "U$4") (pin "29") (pinfunction "P17/MTIOC3A/MTIOC3B/SCK1/TXD3_29") (pintype "bidirectional"))
      (node (ref "U$57") (pin "2") (pinfunction "-CS_2") (pintype "bidirectional"))
    )
    (net (code "92") (name "/631-PA0") (class "Default")
      (node (ref "U$4") (pin "70") (pinfunction "PA0/MTIOC4A_70") (pintype "bidirectional"))
      (node (ref "U$65") (pin "11") (pinfunction "DB4_11") (pintype "bidirectional"))
    )
    (net (code "93") (name "/631-PA1") (class "Default")
      (node (ref "U$4") (pin "69") (pinfunction "PA1/MTIOC0B/MTCLKC/SCK5_69") (pintype "bidirectional"))
      (node (ref "U$65") (pin "12") (pinfunction "DB5_12") (pintype "bidirectional"))
    )
    (net (code "94") (name "/631-PA2") (class "Default")
      (node (ref "U$4") (pin "68") (pinfunction "PA2/RXD5_68") (pintype "bidirectional"))
      (node (ref "U$65") (pin "13") (pinfunction "DB6_13") (pintype "bidirectional"))
    )
    (net (code "95") (name "/631-PA3") (class "Default")
      (node (ref "U$4") (pin "67") (pinfunction "PA3/MTIOC0D/MTCLKD/RXD5_67") (pintype "bidirectional"))
      (node (ref "U$65") (pin "14") (pinfunction "DB7_14") (pintype "bidirectional"))
    )
    (net (code "96") (name "/631-PB0") (class "Default")
      (node (ref "U$4") (pin "61") (pinfunction "PB0/RXD6_61") (pintype "bidirectional"))
      (node (ref "U$65") (pin "4") (pinfunction "RS_4") (pintype "bidirectional"))
    )
    (net (code "97") (name "/631-PB1") (class "Default")
      (node (ref "U$4") (pin "59") (pinfunction "PB1/MTIOC0C/MTIOC4C/TXD6_59") (pintype "bidirectional"))
      (node (ref "U$65") (pin "6") (pinfunction "E_6") (pintype "bidirectional"))
    )
    (net (code "98") (name "/631-PB2") (class "Default")
      (node (ref "LED0") (pin "A") (pinfunction "A_A") (pintype "passive"))
      (node (ref "U$4") (pin "58") (pinfunction "PB2_58") (pintype "bidirectional"))
    )
    (net (code "99") (name "/631-PB3") (class "Default")
      (node (ref "LED1") (pin "A") (pinfunction "A_A") (pintype "passive"))
      (node (ref "U$4") (pin "57") (pinfunction "PB3/MTIOC0A/MTIOC4A/SCK6_57") (pintype "bidirectional"))
    )
    (net (code "100") (name "/631-PB4") (class "Default")
      (node (ref "LED2") (pin "A") (pinfunction "A_A") (pintype "passive"))
      (node (ref "U$4") (pin "56") (pinfunction "PB4_56") (pintype "bidirectional"))
    )
    (net (code "101") (name "/631-PB5") (class "Default")
      (node (ref "LED3") (pin "A") (pinfunction "A_A") (pintype "passive"))
      (node (ref "U$4") (pin "55") (pinfunction "PB5/MTIOC2A/MTIOC1B/SCK9_55") (pintype "bidirectional"))
    )
    (net (code "102") (name "/631-PB6") (class "Default")
      (node (ref "LED15") (pin "A") (pinfunction "A_A") (pintype "passive"))
      (node (ref "U$4") (pin "54") (pinfunction "PB6/MTIOC3D/RXD9_54") (pintype "bidirectional"))
    )
    (net (code "103") (name "/631-PB7") (class "Default")
      (node (ref "LED16") (pin "A") (pinfunction "A_A") (pintype "passive"))
      (node (ref "U$4") (pin "53") (pinfunction "PB7/MTIOC3B/TXD9_53") (pintype "bidirectional"))
    )
    (net (code "104") (name "/631-PC0") (class "Default")
      (node (ref "Q4") (pin "1") (pinfunction "G_1") (pintype "bidirectional"))
      (node (ref "R43") (pin "2") (pinfunction "2_2") (pintype "passive"))
      (node (ref "U$4") (pin "52") (pinfunction "PC0/MTIOC3C_52") (pintype "bidirectional"))
    )
    (net (code "105") (name "/631-PD6") (class "Default")
      (node (ref "R53") (pin "2") (pinfunction "2_2") (pintype "passive"))
      (node (ref "U$4") (pin "80") (pinfunction "PD6/AN6_80") (pintype "bidirectional"))
      (node (ref "U$71") (pin "2") (pinfunction "2_2") (pintype "bidirectional"))
    )
    (net (code "106") (name "/631-PD7") (class "Default")
      (node (ref "R54") (pin "2") (pinfunction "2_2") (pintype "passive"))
      (node (ref "U$4") (pin "79") (pinfunction "PD7/AN7_79") (pintype "bidirectional"))
      (node (ref "U$70") (pin "2") (pinfunction "2_2") (pintype "bidirectional"))
    )
    (net (code "107") (name "/631-PE1") (class "Default")
      (node (ref "R55") (pin "2") (pinfunction "2_2") (pintype "passive"))
      (node (ref "U$4") (pin "77") (pinfunction "PE1/MTIOC4C/TXD12/ANEX1_77") (pintype "bidirectional"))
      (node (ref "U$69") (pin "2") (pinfunction "2_2") (pintype "bidirectional"))
    )
    (net (code "108") (name "/631-PE2") (class "Default")
      (node (ref "R56") (pin "2") (pinfunction "2_2") (pintype "passive"))
      (node (ref "U$4") (pin "76") (pinfunction "PE2/MTIOC4A/RXD12/AN0_76") (pintype "bidirectional"))
      (node (ref "U$66") (pin "2") (pinfunction "2_2") (pintype "bidirectional"))
    )
    (net (code "109") (name "/631-RESET") (class "Default")
      (node (ref "R6") (pin "2") (pinfunction "2_2") (pintype "passive"))
      (node (ref "SJ1") (pin "1") (pinfunction "1_1") (pintype "passive"))
      (node (ref "U$4") (pin "10") (pinfunction "RES#_10") (pintype "bidirectional"))
      (node (ref "U$6") (pin "A") (pinfunction "A_A") (pintype "bidirectional"))
      (node (ref "U$6") (pin "B") (pinfunction "B_B") (pintype "bidirectional"))
    )
    (net (code "110") (name "/631-RSPCKA") (class "Default")
      (node (ref "R35") (pin "1") (pinfunction "1_1") (pintype "passive"))
      (node (ref "U$4") (pin "65") (pinfunction "PA5_65") (pintype "bidirectional"))
    )
    (net (code "111") (name "/631-RSPCKB") (class "Default")
      (node (ref "MCU1") (pin "73") (pinfunction "PE5/IRQ5_73") (pintype "bidirectional"))
      (node (ref "U$1") (pin "2") (pinfunction "2_2") (pintype "bidirectional"))
      (node (ref "U$4") (pin "73") (pinfunction "PE5/MTIOC4C/MTIOC2B/AN3_73") (pintype "bidirectional"))
    )
    (net (code "112") (name "/631-RXD0") (class "Default")
      (node (ref "R33") (pin "1") (pinfunction "1_1") (pintype "passive"))
      (node (ref "U$4") (pin "27") (pinfunction "P21/MTIOC1B/RXD0_27") (pintype "bidirectional"))
      (node (ref "U$57") (pin "7") (pinfunction "DO_7") (pintype "bidirectional"))
    )
    (net (code "113") (name "/631-RXD1") (class "Default")
      (node (ref "JP7") (pin "3") (pinfunction "3_3") (pintype "passive"))
      (node (ref "U$4") (pin "20") (pinfunction "P30/TDI/MTIOC4B/RXD1_20") (pintype "bidirectional"))
    )
    (net (code "114") (name "/631-RXD5") (class "Default")
      (node (ref "JP1") (pin "1") (pinfunction "1_1") (pintype "passive"))
      (node (ref "U$4") (pin "50") (pinfunction "PC2/MTIOC4B/TCLKA/RXD5_50") (pintype "bidirectional"))
    )
    (net (code "115") (name "/631-SCK0") (class "Default")
      (node (ref "R72") (pin "1") (pinfunction "1_1") (pintype "passive"))
      (node (ref "U$4") (pin "26") (pinfunction "P22/MTIOC3B/MTCLKC/SCK0_26") (pintype "bidirectional"))
    )
    (net (code "116") (name "/631-SSLA0") (class "Default")
      (node (ref "U$28") (pin "2") (pinfunction "-CS_2") (pintype "bidirectional"))
      (node (ref "U$4") (pin "66") (pinfunction "PA4/MTCLKA/TXD5_66") (pintype "bidirectional"))
    )
    (net (code "117") (name "/631-SSLB0") (class "Default")
      (node (ref "MCU1") (pin "74") (pinfunction "PE4_74") (pintype "bidirectional"))
      (node (ref "U$4") (pin "74") (pinfunction "PE4/MTIOC4D/MTIOC1A/AN2_74") (pintype "bidirectional"))
    )
    (net (code "118") (name "/631-SSLB1") (class "Default")
      (node (ref "U$1") (pin "1") (pinfunction "1_1") (pintype "bidirectional"))
      (node (ref "U$4") (pin "78") (pinfunction "PE0/SCK12/ANEX0_78") (pintype "bidirectional"))
    )
    (net (code "119") (name "/631-TXD0") (class "Default")
      (node (ref "U$4") (pin "28") (pinfunction "P20/MTIOC1A/TXD0_28") (pintype "bidirectional"))
      (node (ref "U$57") (pin "3") (pinfunction "DI_3") (pintype "bidirectional"))
    )
    (net (code "120") (name "/631-TXD1") (class "Default")
      (node (ref "JP7") (pin "4") (pinfunction "4_4") (pintype "passive"))
      (node (ref "U$4") (pin "22") (pinfunction "P26/TDO/MTIOC2A/TXD1_22") (pintype "bidirectional"))
    )
    (net (code "121") (name "/631-TXD5") (class "Default")
      (node (ref "JP1") (pin "2") (pinfunction "2_2") (pintype "passive"))
      (node (ref "U$4") (pin "49") (pinfunction "PC3/MTIOC4D/TCLKB/TXD5_49") (pintype "bidirectional"))
    )
    (net (code "122") (name "/631-VCL") (class "Default")
      (node (ref "C4") (pin "1") (pinfunction "1_1") (pintype "passive"))
      (node (ref "U$4") (pin "5") (pinfunction "VCL_5") (pintype "bidirectional"))
    )
    (net (code "123") (name "/631-XTAL") (class "Default")
      (node (ref "C5") (pin "2") (pinfunction "2_2") (pintype "passive"))
      (node (ref "U$4") (pin "11") (pinfunction "P37/XTAL_11") (pintype "bidirectional"))
      (node (ref "U$61") (pin "3") (pinfunction "3_3") (pintype "bidirectional"))
    )
    (net (code "124") (name "/CANH0") (class "Default")
      (node (ref "JP3") (pin "1") (pinfunction "1_1") (pintype "passive"))
      (node (ref "R65") (pin "1") (pinfunction "1_1") (pintype "passive"))
      (node (ref "U$20") (pin "P$5") (pinfunction "5_P$5") (pintype "passive"))
      (node (ref "U$64") (pin "7") (pinfunction "CANH_7") (pintype "bidirectional"))
    )
    (net (code "125") (name "/CANH1") (class "Default")
      (node (ref "0") (pin "1") (pinfunction "1_1") (pintype "passive"))
      (node (ref "R11") (pin "2") (pinfunction "2_2") (pintype "passive"))
      (node (ref "U$17") (pin "7") (pinfunction "CANH_7") (pintype "bidirectional"))
      (node (ref "U$25") (pin "P$5") (pinfunction "5_P$5") (pintype "passive"))
    )
    (net (code "126") (name "/CANL0") (class "Default")
      (node (ref "R2") (pin "2") (pinfunction "2_2") (pintype "passive"))
      (node (ref "U$19") (pin "6") (pinfunction "CANL_6") (pintype "bidirectional"))
      (node (ref "U$20") (pin "P$4") (pinfunction "4_P$4") (pintype "passive"))
      (node (ref "U$21") (pin "P$4") (pinfunction "4_P$4") (pintype "passive"))
      (node (ref "U$64") (pin "6") (pinfunction "CANL_6") (pintype "bidirectional"))
    )
    (net (code "127") (name "/CANL1") (class "Default")
      (node (ref "R3") (pin "1") (pinfunction "1_1") (pintype "passive"))
      (node (ref "U$17") (pin "6") (pinfunction "CANL_6") (pintype "bidirectional"))
      (node (ref "U$18") (pin "P$4") (pinfunction "4_P$4") (pintype "passive"))
      (node (ref "U$25") (pin "P$4") (pinfunction "4_P$4") (pintype "passive"))
    )
    (net (code "128") (name "/CTS-RTS0") (class "Default")
      (node (ref "JP1") (pin "3") (pinfunction "3_3") (pintype "passive"))
      (node (ref "JP1") (pin "4") (pinfunction "4_4") (pintype "passive"))
    )
    (net (code "129") (name "/CTS-RTS1") (class "Default")
      (node (ref "JP8") (pin "3") (pinfunction "3_3") (pintype "passive"))
      (node (ref "JP8") (pin "4") (pinfunction "4_4") (pintype "passive"))
    )
    (net (code "130") (name "/CTS{slash}RTS-631") (class "Default")
      (node (ref "IC6") (pin "4") (pinfunction "RC8_4") (pintype "bidirectional"))
      (node (ref "IC6") (pin "5") (pinfunction "RC9_5") (pintype "bidirectional"))
    )
    (net (code "131") (name "/DM621") (class "Default")
      (node (ref "IC7") (pin "9") (pinfunction "RB11_9") (pintype "bidirectional"))
      (node (ref "U$77") (pin "2") (pinfunction "D-_2") (pintype "bidirectional"))
    )
    (net (code "132") (name "/DM631") (class "Default")
      (node (ref "IC6") (pin "9") (pinfunction "RB11_9") (pintype "bidirectional"))
      (node (ref "U$75") (pin "2") (pinfunction "D-_2") (pintype "bidirectional"))
    )
    (net (code "133") (name "/DP621") (class "Default")
      (node (ref "IC7") (pin "8") (pinfunction "RB10_8") (pintype "bidirectional"))
      (node (ref "U$77") (pin "3") (pinfunction "D+_3") (pintype "bidirectional"))
    )
    (net (code "134") (name "/DP631") (class "Default")
      (node (ref "IC6") (pin "8") (pinfunction "RB10_8") (pintype "bidirectional"))
      (node (ref "U$75") (pin "3") (pinfunction "D+_3") (pintype "bidirectional"))
    )
    (net (code "135") (name "/MODE_SW_EN") (class "Default")
      (node (ref "R_MD2") (pin "2") (pinfunction "2_2") (pintype "passive"))
      (node (ref "SJ5") (pin "2") (pinfunction "2_2") (pintype "passive"))
      (node (ref "U$68") (pin "1") (pinfunction "OE_1") (pintype "input"))
    )
    (net (code "136") (name "/NMCLR-621") (class "Default")
      (node (ref "IC7") (pin "18") (pinfunction "~{MCLR}_18") (pintype "bidirectional"))
      (node (ref "JP6") (pin "5") (pinfunction "5_5") (pintype "passive"))
      (node (ref "R44") (pin "1") (pinfunction "1_1") (pintype "passive"))
    )
    (net (code "137") (name "/NMCLR-631") (class "Default")
      (node (ref "IC6") (pin "18") (pinfunction "~{MCLR}_18") (pintype "bidirectional"))
      (node (ref "JP5") (pin "5") (pinfunction "5_5") (pintype "passive"))
      (node (ref "R59") (pin "1") (pinfunction "1_1") (pintype "passive"))
    )
    (net (code "138") (name "/PGEC1-621") (class "Default")
      (node (ref "IC7") (pin "22") (pinfunction "RB1_22") (pintype "bidirectional"))
      (node (ref "JP6") (pin "1") (pinfunction "1_1") (pintype "passive"))
    )
    (net (code "139") (name "/PGEC1-631") (class "Default")
      (node (ref "IC6") (pin "22") (pinfunction "RB1_22") (pintype "bidirectional"))
      (node (ref "JP5") (pin "1") (pinfunction "1_1") (pintype "passive"))
      (node (ref "SJ4") (pin "1") (pinfunction "1_1") (pintype "passive"))
    )
    (net (code "140") (name "/PGED1-621") (class "Default")
      (node (ref "IC7") (pin "21") (pinfunction "RB0_21") (pintype "bidirectional"))
      (node (ref "JP6") (pin "2") (pinfunction "2_2") (pintype "passive"))
    )
    (net (code "141") (name "/PGED1-631") (class "Default")
      (node (ref "IC6") (pin "21") (pinfunction "RB0_21") (pintype "bidirectional"))
      (node (ref "JP5") (pin "2") (pinfunction "2_2") (pintype "passive"))
      (node (ref "SJ5") (pin "1") (pinfunction "1_1") (pintype "passive"))
    )
    (net (code "142") (name "/RB9") (class "Default")
      (node (ref "IC6") (pin "1") (pinfunction "RB9_1") (pintype "bidirectional"))
      (node (ref "SJ1") (pin "2") (pinfunction "2_2") (pintype "passive"))
    )
    (net (code "143") (name "/RESET-621") (class "Default")
      (node (ref "IC7") (pin "1") (pinfunction "RB9_1") (pintype "bidirectional"))
    )
    (net (code "144") (name "/RTS{slash}CTS-621") (class "Default")
      (node (ref "IC7") (pin "4") (pinfunction "RC8_4") (pintype "bidirectional"))
      (node (ref "IC7") (pin "5") (pinfunction "RC9_5") (pintype "bidirectional"))
    )
    (net (code "145") (name "/RXD1") (class "Default")
      (node (ref "IC4") (pin "1") (pinfunction "TXD_1") (pintype "output"))
      (node (ref "JP7") (pin "5") (pinfunction "5_5") (pintype "passive"))
    )
    (net (code "146") (name "/SBDBT1-RX") (class "Default")
      (node (ref "IC6") (pin "3") (pinfunction "RC7_3") (pintype "bidirectional"))
      (node (ref "JP7") (pin "2") (pinfunction "2_2") (pintype "passive"))
    )
    (net (code "147") (name "/SBDBT1-TX") (class "Default")
      (node (ref "IC6") (pin "2") (pinfunction "RC6_2") (pintype "bidirectional"))
      (node (ref "JP7") (pin "1") (pinfunction "1_1") (pintype "passive"))
    )
    (net (code "148") (name "/TXD1") (class "Default")
      (node (ref "JP7") (pin "6") (pinfunction "6_6") (pintype "passive"))
      (node (ref "R9") (pin "2") (pinfunction "2_2") (pintype "passive"))
    )
    (net (code "149") (name "/USB0_DM") (class "Default")
      (node (ref "R39") (pin "2") (pinfunction "2_2") (pintype "passive"))
      (node (ref "R42") (pin "1") (pinfunction "1_1") (pintype "passive"))
      (node (ref "U$67") (pin "2") (pinfunction "D-_2") (pintype "bidirectional"))
    )
    (net (code "150") (name "/USB0_DP") (class "Default")
      (node (ref "R40") (pin "2") (pinfunction "2_2") (pintype "passive"))
      (node (ref "R41") (pin "1") (pinfunction "1_1") (pintype "passive"))
      (node (ref "U$67") (pin "3") (pinfunction "D+_3") (pintype "bidirectional"))
    )
    (net (code "151") (name "/VBUS0") (class "Default")
      (node (ref "C10") (pin "2") (pinfunction "2_2") (pintype "passive"))
      (node (ref "C11") (pin "2") (pinfunction "2_2") (pintype "passive"))
      (node (ref "D1") (pin "C") (pinfunction "C_C") (pintype "passive"))
      (node (ref "IC4") (pin "20") (pinfunction "VCC_20") (pintype "power_in"))
      (node (ref "U$9") (pin "1") (pinfunction "VBUS_1") (pintype "bidirectional"))
    )
    (net (code "152") (name "/VBUS1") (class "Default")
      (node (ref "C26") (pin "2") (pinfunction "2_2") (pintype "passive"))
      (node (ref "C27") (pin "2") (pinfunction "2_2") (pintype "passive"))
      (node (ref "D14") (pin "C") (pinfunction "C_C") (pintype "passive"))
      (node (ref "IC2") (pin "20") (pinfunction "VCC_20") (pintype "power_in"))
      (node (ref "U$63") (pin "1") (pinfunction "VBUS_1") (pintype "bidirectional"))
    )
    (net (code "153") (name "GND") (class "Default")
      (node (ref "C1") (pin "1") (pinfunction "1_1") (pintype "passive"))
      (node (ref "C10") (pin "1") (pinfunction "1_1") (pintype "passive"))
      (node (ref "C11") (pin "1") (pinfunction "1_1") (pintype "passive"))
      (node (ref "C12") (pin "2") (pinfunction "2_2") (pintype "passive"))
      (node (ref "C13") (pin "2") (pinfunction "2_2") (pintype "passive"))
      (node (ref "C14") (pin "2") (pinfunction "2_2") (pintype "passive"))
      (node (ref "C15") (pin "2") (pinfunction "2_2") (pintype "passive"))
      (node (ref "C16") (pin "2") (pinfunction "2_2") (pintype "passive"))
      (node (ref "C17") (pin "2") (pinfunction "2_2") (pintype "passive"))
      (node (ref "C18") (pin "2") (pinfunction "2_2") (pintype "passive"))
      (node (ref "C19") (pin "2") (pinfunction "2_2") (pintype "passive"))
      (node (ref "C2") (pin "2") (pinfunction "2_2") (pintype "passive"))
      (node (ref "C20") (pin "2") (pinfunction "2_2") (pintype "passive"))
      (node (ref "C21") (pin "1") (pinfunction "1_1") (pintype "passive"))
      (node (ref "C22") (pin "2") (pinfunction "2_2") (pintype "passive"))
      (node (ref "C23") (pin "1") (pinfunction "1_1") (pintype "passive"))
      (node (ref "C24") (pin "2") (pinfunction "2_2") (pintype "passive"))
      (node (ref "C25") (pin "2") (pinfunction "2_2") (pintype "passive"))
      (node (ref "C26") (pin "1") (pinfunction "1_1") (pintype "passive"))
      (node (ref "C27") (pin "1") (pinfunction "1_1") (pintype "passive"))
      (node (ref "C28") (pin "1") (pinfunction "1_1") (pintype "passive"))
      (node (ref "C3") (pin "2") (pinfunction "2_2") (pintype "passive"))
      (node (ref "C32") (pin "1") (pinfunction "1_1") (pintype "passive"))
      (node (ref "C33") (pin "1") (pinfunction "1_1") (pintype "passive"))
      (node (ref "C34") (pin "1") (pinfunction "1_1") (pintype "passive"))
      (node (ref "C35") (pin "1") (pinfunction "1_1") (pintype "passive"))
      (node (ref "C36") (pin "1") (pinfunction "1_1") (pintype "passive"))
      (node (ref "C37") (pin "1") (pinfunction "1_1") (pintype "passive"))
      (node (ref "C4") (pin "2") (pinfunction "2_2") (pintype "passive"))
      (node (ref "C40") (pin "1") (pinfunction "1_1") (pintype "passive"))
      (node (ref "C41") (pin "1") (pinfunction "1_1") (pintype "passive"))
      (node (ref "C42") (pin "1") (pinfunction "1_1") (pintype "passive"))
      (node (ref "C43") (pin "1") (pinfunction "1_1") (pintype "passive"))
      (node (ref "C44") (pin "1") (pinfunction "1_1") (pintype "passive"))
      (node (ref "C45") (pin "1") (pinfunction "1_1") (pintype "passive"))
      (node (ref "C46") (pin "2") (pinfunction "2_2") (pintype "passive"))
      (node (ref "C47") (pin "1") (pinfunction "1_1") (pintype "passive"))
      (node (ref "C5") (pin "1") (pinfunction "1_1") (pintype "passive"))
      (node (ref "C6") (pin "2") (pinfunction "2_2") (pintype "passive"))
      (node (ref "C7") (pin "2") (pinfunction "2_2") (pintype "passive"))
      (node (ref "C8") (pin "2") (pinfunction "2_2") (pintype "passive"))
      (node (ref "C9") (pin "1") (pinfunction "1_1") (pintype "passive"))
      (node (ref "IC1") (pin "1") (pinfunction "GND_1") (pintype "power_in"))
      (node (ref "IC2") (pin "18") (pinfunction "GND_18") (pintype "power_in"))
      (node (ref "IC2") (pin "21") (pinfunction "GND_21") (pintype "power_in"))
      (node (ref "IC2") (pin "25") (pinfunction "GND_25") (pintype "power_in"))
      (node (ref "IC2") (pin "26") (pinfunction "TEST_26") (pintype "input"))
      (node (ref "IC2") (pin "7") (pinfunction "GND_7") (pintype "power_in"))
      (node (ref "IC3") (pin "1") (pinfunction "GND_1") (pintype "power_in"))
      (node (ref "IC4") (pin "18") (pinfunction "GND_18") (pintype "power_in"))
      (node (ref "IC4") (pin "21") (pinfunction "GND_21") (pintype "power_in"))
      (node (ref "IC4") (pin "25") (pinfunction "GND_25") (pintype "power_in"))
      (node (ref "IC4") (pin "26") (pinfunction "TEST_26") (pintype "input"))
      (node (ref "IC4") (pin "7") (pinfunction "GND_7") (pintype "power_in"))
      (node (ref "IC5") (pin "15") (pinfunction "GND_15") (pintype "passive"))
      (node (ref "IC6") (pin "16") (pinfunction "AVSS_16") (pintype "power_in"))
      (node (ref "IC6") (pin "29") (pinfunction "VSS_29") (pintype "power_in"))
      (node (ref "IC6") (pin "39") (pinfunction "VSS_39") (pintype "power_in"))
      (node (ref "IC6") (pin "6") (pinfunction "DISVREG_6") (pintype "passive"))
      (node (ref "IC7") (pin "16") (pinfunction "AVSS_16") (pintype "power_in"))
      (node (ref "IC7") (pin "29") (pinfunction "VSS_29") (pintype "power_in"))
      (node (ref "IC7") (pin "39") (pinfunction "VSS_39") (pintype "power_in"))
      (node (ref "IC7") (pin "6") (pinfunction "DISVREG_6") (pintype "passive"))
      (node (ref "JP1") (pin "6") (pinfunction "6_6") (pintype "passive"))
      (node (ref "JP5") (pin "3") (pinfunction "3_3") (pintype "passive"))
      (node (ref "JP6") (pin "3") (pinfunction "3_3") (pintype "passive"))
      (node (ref "JP8") (pin "6") (pinfunction "6_6") (pintype "passive"))
      (node (ref "MCU1") (pin "12") (pinfunction "VSS_12") (pintype "power_in"))
      (node (ref "MCU1") (pin "2") (pinfunction "EMLE_2") (pintype "bidirectional"))
      (node (ref "MCU1") (pin "3") (pinfunction "VSS_3") (pintype "power_in"))
      (node (ref "MCU1") (pin "31") (pinfunction "PLLVSS_31") (pintype "power_in"))
      (node (ref "MCU1") (pin "38") (pinfunction "VSS_USB_38") (pintype "power_in"))
      (node (ref "MCU1") (pin "4") (pinfunction "MDE_4") (pintype "input"))
      (node (ref "MCU1") (pin "62") (pinfunction "VSS_62") (pintype "power_in"))
      (node (ref "MCU1") (pin "94") (pinfunction "VREFL_94") (pintype "power_in"))
      (node (ref "MCU1") (pin "99") (pinfunction "AVSS_99") (pintype "power_in"))
      (node (ref "Q4") (pin "2") (pinfunction "S_2") (pintype "bidirectional"))
      (node (ref "R27") (pin "2") (pinfunction "2_2") (pintype "passive"))
      (node (ref "R28") (pin "2") (pinfunction "2_2") (pintype "passive"))
      (node (ref "R29") (pin "2") (pinfunction "2_2") (pintype "passive"))
      (node (ref "R30") (pin "2") (pinfunction "2_2") (pintype "passive"))
      (node (ref "R31") (pin "E") (pinfunction "E_E") (pintype "passive"))
      (node (ref "R43") (pin "1") (pinfunction "1_1") (pintype "passive"))
      (node (ref "R49") (pin "2") (pinfunction "2_2") (pintype "passive"))
      (node (ref "R50") (pin "2") (pinfunction "2_2") (pintype "passive"))
      (node (ref "R51") (pin "2") (pinfunction "2_2") (pintype "passive"))
      (node (ref "R52") (pin "2") (pinfunction "2_2") (pintype "passive"))
      (node (ref "R67") (pin "1") (pinfunction "1_1") (pintype "passive"))
      (node (ref "R68") (pin "2") (pinfunction "2_2") (pintype "passive"))
      (node (ref "R69") (pin "2") (pinfunction "2_2") (pintype "passive"))
      (node (ref "R70") (pin "2") (pinfunction "2_2") (pintype "passive"))
      (node (ref "R71") (pin "2") (pinfunction "2_2") (pintype "passive"))
      (node (ref "R_MD2") (pin "1") (pinfunction "1_1") (pintype "passive"))
      (node (ref "R_XCIN") (pin "1") (pinfunction "1_1") (pintype "passive"))
      (node (ref "U$14") (pin "2") (pinfunction "2_2") (pintype "bidirectional"))
      (node (ref "U$15") (pin "2") (pinfunction "2_2") (pintype "bidirectional"))
      (node (ref "U$17") (pin "2") (pinfunction "VSS_2") (pintype "power_in"))
      (node (ref "U$17") (pin "8") (pinfunction "STBY_8") (pintype "bidirectional"))
      (node (ref "U$18") (pin "P$6") (pinfunction "6_P$6") (pintype "passive"))
      (node (ref "U$18") (pin "P$7") (pinfunction "7_P$7") (pintype "passive"))
      (node (ref "U$18") (pin "P$8") (pinfunction "8_P$8") (pintype "passive"))
      (node (ref "U$19") (pin "2") (pinfunction "VSS_2") (pintype "power_in"))
      (node (ref "U$19") (pin "8") (pinfunction "STBY_8") (pintype "bidirectional"))
      (node (ref "U$20") (pin "P$6") (pinfunction "6_P$6") (pintype "passive"))
      (node (ref "U$20") (pin "P$7") (pinfunction "7_P$7") (pintype "passive"))
      (node (ref "U$20") (pin "P$8") (pinfunction "8_P$8") (pintype "passive"))
      (node (ref "U$21") (pin "P$6") (pinfunction "6_P$6") (pintype "passive"))
      (node (ref "U$21") (pin "P$7") (pinfunction "7_P$7") (pintype "passive"))
      (node (ref "U$21") (pin "P$8") (pinfunction "8_P$8") (pintype "passive"))
      (node (ref "U$22") (pin "2") (pinfunction "2_2") (pintype "bidirectional"))
      (node (ref "U$23") (pin "2") (pinfunction "2_2") (pintype "bidirectional"))
      (node (ref "U$24") (pin "2") (pinfunction "2_2") (pintype "bidirectional"))
      (node (ref "U$25") (pin "P$6") (pinfunction "6_P$6") (pintype "passive"))
      (node (ref "U$25") (pin "P$7") (pinfunction "7_P$7") (pintype "passive"))
      (node (ref "U$25") (pin "P$8") (pinfunction "8_P$8") (pintype "passive"))
      (node (ref "U$26") (pin "2") (pinfunction "GND_2") (pintype "power_in"))
      (node (ref "U$27") (pin "2") (pinfunction "2_2") (pintype "bidirectional"))
      (node (ref "U$28") (pin "6") (pinfunction "GND_6") (pintype "bidirectional"))
      (node (ref "U$29") (pin "2") (pinfunction "2_2") (pintype "bidirectional"))
      (node (ref "U$30") (pin "2") (pinfunction "2_2") (pintype "bidirectional"))
      (node (ref "U$4") (pin "12") (pinfunction "VSS_12") (pintype "bidirectional"))
      (node (ref "U$4") (pin "2") (pinfunction "EMLE_2") (pintype "bidirectional"))
      (node (ref "U$4") (pin "3") (pinfunction "VREFL_3") (pintype "bidirectional"))
      (node (ref "U$4") (pin "38") (pinfunction "VSS_USB_38") (pintype "bidirectional"))
      (node (ref "U$4") (pin "62") (pinfunction "VSS_62") (pintype "bidirectional"))
      (node (ref "U$4") (pin "94") (pinfunction "VREFL0_94") (pintype "bidirectional"))
      (node (ref "U$4") (pin "99") (pinfunction "AVSS0_99") (pintype "bidirectional"))
      (node (ref "U$57") (pin "6") (pinfunction "GND_6") (pintype "bidirectional"))
      (node (ref "U$6") (pin "C") (pinfunction "C_C") (pintype "bidirectional"))
      (node (ref "U$6") (pin "D") (pinfunction "D_D") (pintype "bidirectional"))
      (node (ref "U$61") (pin "2") (pinfunction "GND_2") (pintype "power_in"))
      (node (ref "U$61") (pin "4") (pinfunction "GND_4") (pintype "power_in"))
      (node (ref "U$62") (pin "2") (pinfunction "GND_2") (pintype "power_in"))
      (node (ref "U$62") (pin "4") (pinfunction "GND_4") (pintype "power_in"))
      (node (ref "U$63") (pin "4") (pinfunction "GND_4") (pintype "bidirectional"))
      (node (ref "U$64") (pin "2") (pinfunction "VSS_2") (pintype "power_in"))
      (node (ref "U$64") (pin "8") (pinfunction "STBY_8") (pintype "bidirectional"))
      (node (ref "U$65") (pin "2") (pinfunction "VSS_2") (pintype "power_in"))
      (node (ref "U$65") (pin "5") (pinfunction "R/W_5") (pintype "bidirectional"))
      (node (ref "U$66") (pin "1") (pinfunction "1_1") (pintype "bidirectional"))
      (node (ref "U$67") (pin "4") (pinfunction "GND_4") (pintype "bidirectional"))
      (node (ref "U$68") (pin "3") (pinfunction "G_3") (pintype "bidirectional"))
      (node (ref "U$69") (pin "1") (pinfunction "1_1") (pintype "bidirectional"))
      (node (ref "U$70") (pin "1") (pinfunction "1_1") (pintype "bidirectional"))
      (node (ref "U$71") (pin "1") (pinfunction "1_1") (pintype "bidirectional"))
      (node (ref "U$72") (pin "1") (pinfunction "1_1") (pintype "bidirectional"))
      (node (ref "U$73") (pin "1") (pinfunction "1_1") (pintype "bidirectional"))
      (node (ref "U$74") (pin "1") (pinfunction "1_1") (pintype "bidirectional"))
      (node (ref "U$75") (pin "4") (pinfunction "GND_4") (pintype "bidirectional"))
      (node (ref "U$77") (pin "4") (pinfunction "GND_4") (pintype "bidirectional"))
      (node (ref "U$79") (pin "5") (pinfunction "5_5") (pintype "bidirectional"))
      (node (ref "U$79") (pin "6") (pinfunction "6_6") (pintype "bidirectional"))
      (node (ref "U$79") (pin "7") (pinfunction "7_7") (pintype "bidirectional"))
      (node (ref "U$79") (pin "8") (pinfunction "8_8") (pintype "bidirectional"))
      (node (ref "U$8") (pin "C") (pinfunction "C_C") (pintype "bidirectional"))
      (node (ref "U$8") (pin "D") (pinfunction "D_D") (pintype "bidirectional"))
      (node (ref "U$80") (pin "2") (pinfunction "2_2") (pintype "bidirectional"))
      (node (ref "U$81") (pin "1") (pinfunction "1_1") (pintype "bidirectional"))
      (node (ref "U$82") (pin "1") (pinfunction "1_1") (pintype "bidirectional"))
      (node (ref "U$82") (pin "4") (pinfunction "4_4") (pintype "bidirectional"))
      (node (ref "U$9") (pin "5") (pinfunction "GND_5") (pintype "bidirectional"))
      (node (ref "X2") (pin "2") (pinfunction "S_2") (pintype "passive"))
      (node (ref "X3") (pin "2") (pinfunction "S_2") (pintype "passive"))
    )
    (net (code "154") (name "Net-(0-Pad2)") (class "Default")
      (node (ref "0") (pin "2") (pinfunction "2_2") (pintype "passive"))
      (node (ref "JP2") (pin "1") (pinfunction "1_1") (pintype "passive"))
    )
    (net (code "155") (name "Net-(D2-PadC)") (class "Default")
      (node (ref "D2") (pin "C") (pinfunction "C_C") (pintype "passive"))
      (node (ref "U$15") (pin "3") (pinfunction "3_3") (pintype "bidirectional"))
    )
    (net (code "156") (name "Net-(D3-PadC)") (class "Default")
      (node (ref "D3") (pin "C") (pinfunction "C_C") (pintype "passive"))
      (node (ref "U$15") (pin "4") (pinfunction "4_4") (pintype "bidirectional"))
    )
    (net (code "157") (name "Net-(D4-PadC)") (class "Default")
      (node (ref "D4") (pin "C") (pinfunction "C_C") (pintype "passive"))
      (node (ref "U$14") (pin "3") (pinfunction "3_3") (pintype "bidirectional"))
    )
    (net (code "158") (name "Net-(D5-PadC)") (class "Default")
      (node (ref "D5") (pin "C") (pinfunction "C_C") (pintype "passive"))
      (node (ref "U$14") (pin "4") (pinfunction "4_4") (pintype "bidirectional"))
    )
    (net (code "159") (name "Net-(D6-PadC)") (class "Default")
      (node (ref "D6") (pin "C") (pinfunction "C_C") (pintype "passive"))
      (node (ref "U$24") (pin "3") (pinfunction "3_3") (pintype "bidirectional"))
    )
    (net (code "160") (name "Net-(D7-PadC)") (class "Default")
      (node (ref "D7") (pin "C") (pinfunction "C_C") (pintype "passive"))
      (node (ref "U$24") (pin "4") (pinfunction "4_4") (pintype "bidirectional"))
    )
    (net (code "161") (name "Net-(D8-PadC)") (class "Default")
      (node (ref "D8") (pin "C") (pinfunction "C_C") (pintype "passive"))
      (node (ref "U$27") (pin "3") (pinfunction "3_3") (pintype "bidirectional"))
    )
    (net (code "162") (name "Net-(D9-PadC)") (class "Default")
      (node (ref "D9") (pin "C") (pinfunction "C_C") (pintype "passive"))
      (node (ref "U$27") (pin "4") (pinfunction "4_4") (pintype "bidirectional"))
    )
    (net (code "163") (name "Net-(D10-PadC)") (class "Default")
      (node (ref "D10") (pin "C") (pinfunction "C_C") (pintype "passive"))
      (node (ref "U$29") (pin "3") (pinfunction "3_3") (pintype "bidirectional"))
    )
    (net (code "164") (name "Net-(D11-PadC)") (class "Default")
      (node (ref "D11") (pin "C") (pinfunction "C_C") (pintype "passive"))
      (node (ref "U$29") (pin "4") (pinfunction "4_4") (pintype "bidirectional"))
    )
    (net (code "165") (name "Net-(D12-PadC)") (class "Default")
      (node (ref "D12") (pin "C") (pinfunction "C_C") (pintype "passive"))
      (node (ref "U$30") (pin "3") (pinfunction "3_3") (pintype "bidirectional"))
    )
    (net (code "166") (name "Net-(D13-PadC)") (class "Default")
      (node (ref "D13") (pin "C") (pinfunction "C_C") (pintype "passive"))
      (node (ref "U$30") (pin "4") (pinfunction "4_4") (pintype "bidirectional"))
    )
    (net (code "167") (name "Net-(IC1-~{RES})") (class "Default")
      (node (ref "IC1") (pin "2") (pinfunction "~{RES}_2") (pintype "output"))
      (node (ref "R36") (pin "1") (pinfunction "1_1") (pintype "passive"))
    )
    (net (code "168") (name "Net-(IC2-3V3OUT)") (class "Default")
      (node (ref "C23") (pin "2") (pinfunction "2_2") (pintype "passive"))
      (node (ref "IC2") (pin "17") (pinfunction "3V3OUT_17") (pintype "output"))
      (node (ref "IC2") (pin "4") (pinfunction "VCCIO_4") (pintype "power_in"))
    )
    (net (code "169") (name "Net-(IC2-RXD)") (class "Default")
      (node (ref "IC2") (pin "5") (pinfunction "RXD_5") (pintype "input"))
      (node (ref "R37") (pin "1") (pinfunction "1_1") (pintype "passive"))
    )
    (net (code "170") (name "Net-(IC2-USBDM)") (class "Default")
      (node (ref "IC2") (pin "16") (pinfunction "USBDM_16") (pintype "bidirectional"))
      (node (ref "U$63") (pin "2") (pinfunction "D-_2") (pintype "bidirectional"))
    )
    (net (code "171") (name "Net-(IC2-USBDP)") (class "Default")
      (node (ref "IC2") (pin "15") (pinfunction "USBDP_15") (pintype "bidirectional"))
      (node (ref "U$63") (pin "3") (pinfunction "D+_3") (pintype "bidirectional"))
    )
    (net (code "172") (name "Net-(IC3-~{RES})") (class "Default")
      (node (ref "IC3") (pin "2") (pinfunction "~{RES}_2") (pintype "output"))
      (node (ref "R6") (pin "1") (pinfunction "1_1") (pintype "passive"))
    )
    (net (code "173") (name "Net-(IC4-3V3OUT)") (class "Default")
      (node (ref "C9") (pin "2") (pinfunction "2_2") (pintype "passive"))
      (node (ref "IC4") (pin "17") (pinfunction "3V3OUT_17") (pintype "output"))
      (node (ref "IC4") (pin "4") (pinfunction "VCCIO_4") (pintype "power_in"))
    )
    (net (code "174") (name "Net-(IC4-RXD)") (class "Default")
      (node (ref "IC4") (pin "5") (pinfunction "RXD_5") (pintype "input"))
      (node (ref "R9") (pin "1") (pinfunction "1_1") (pintype "passive"))
    )
    (net (code "175") (name "Net-(IC4-USBDM)") (class "Default")
      (node (ref "IC4") (pin "16") (pinfunction "USBDM_16") (pintype "bidirectional"))
      (node (ref "U$9") (pin "2") (pinfunction "D-_2") (pintype "bidirectional"))
    )
    (net (code "176") (name "Net-(IC4-USBDP)") (class "Default")
      (node (ref "IC4") (pin "15") (pinfunction "USBDP_15") (pintype "bidirectional"))
      (node (ref "U$9") (pin "3") (pinfunction "D+_3") (pintype "bidirectional"))
    )
    (net (code "177") (name "Net-(IC5A-C1+)") (class "Default")
      (node (ref "C30") (pin "1") (pinfunction "1_1") (pintype "passive"))
      (node (ref "IC5") (pin "1") (pinfunction "C1+_1") (pintype "bidirectional"))
    )
    (net (code "178") (name "Net-(IC5A-C1-)") (class "Default")
      (node (ref "C30") (pin "2") (pinfunction "2_2") (pintype "passive"))
      (node (ref "IC5") (pin "3") (pinfunction "C1-_3") (pintype "bidirectional"))
    )
    (net (code "179") (name "Net-(IC5A-C2+)") (class "Default")
      (node (ref "C31") (pin "1") (pinfunction "1_1") (pintype "passive"))
      (node (ref "IC5") (pin "4") (pinfunction "C2+_4") (pintype "bidirectional"))
    )
    (net (code "180") (name "Net-(IC5A-C2-)") (class "Default")
      (node (ref "C31") (pin "2") (pinfunction "2_2") (pintype "passive"))
      (node (ref "IC5") (pin "5") (pinfunction "C2-_5") (pintype "bidirectional"))
    )
    (net (code "181") (name "Net-(IC5A-R1IN)") (class "Default")
      (node (ref "IC5") (pin "13") (pinfunction "R1IN_13") (pintype "input"))
      (node (ref "U$80") (pin "3") (pinfunction "3_3") (pintype "bidirectional"))
    )
    (net (code "182") (name "Net-(IC5A-T1OUT)") (class "Default")
      (node (ref "IC5") (pin "14") (pinfunction "T1OUT_14") (pintype "output"))
      (node (ref "U$80") (pin "4") (pinfunction "4_4") (pintype "bidirectional"))
    )
    (net (code "183") (name "Net-(IC5A-V+)") (class "Default")
      (node (ref "C29") (pin "2") (pinfunction "2_2") (pintype "passive"))
      (node (ref "IC5") (pin "2") (pinfunction "V+_2") (pintype "bidirectional"))
    )
    (net (code "184") (name "Net-(IC5A-V-)") (class "Default")
      (node (ref "C28") (pin "2") (pinfunction "2_2") (pintype "passive"))
      (node (ref "IC5") (pin "6") (pinfunction "V-_6") (pintype "bidirectional"))
    )
    (net (code "185") (name "Net-(IC6-RB14)") (class "Default")
      (node (ref "IC6") (pin "14") (pinfunction "RB14_14") (pintype "bidirectional"))
      (node (ref "LED9") (pin "A") (pinfunction "A_A") (pintype "passive"))
    )
    (net (code "186") (name "Net-(IC6-RB15)") (class "Default")
      (node (ref "IC6") (pin "15") (pinfunction "RB15_15") (pintype "bidirectional"))
      (node (ref "LED8") (pin "A") (pinfunction "A_A") (pintype "passive"))
    )
    (net (code "187") (name "Net-(IC6-VDDCORE)") (class "Default")
      (node (ref "C40") (pin "2") (pinfunction "2_2") (pintype "passive"))
      (node (ref "IC6") (pin "7") (pinfunction "VDDCORE_7") (pintype "power_in"))
    )
    (net (code "188") (name "Net-(IC7-RB14)") (class "Default")
      (node (ref "IC7") (pin "14") (pinfunction "RB14_14") (pintype "bidirectional"))
      (node (ref "LED11") (pin "A") (pinfunction "A_A") (pintype "passive"))
    )
    (net (code "189") (name "Net-(IC7-RB15)") (class "Default")
      (node (ref "IC7") (pin "15") (pinfunction "RB15_15") (pintype "bidirectional"))
      (node (ref "LED10") (pin "A") (pinfunction "A_A") (pintype "passive"))
    )
    (net (code "190") (name "Net-(IC7-VDDCORE)") (class "Default")
      (node (ref "C43") (pin "2") (pinfunction "2_2") (pintype "passive"))
      (node (ref "IC7") (pin "7") (pinfunction "VDDCORE_7") (pintype "power_in"))
    )
    (net (code "191") (name "Net-(JP2-Pad2)") (class "Default")
      (node (ref "JP2") (pin "2") (pinfunction "2_2") (pintype "passive"))
      (node (ref "R3") (pin "2") (pinfunction "2_2") (pintype "passive"))
    )
    (net (code "192") (name "Net-(JP3-Pad2)") (class "Default")
      (node (ref "JP3") (pin "2") (pinfunction "2_2") (pintype "passive"))
      (node (ref "R2") (pin "1") (pinfunction "1_1") (pintype "passive"))
    )
    (net (code "193") (name "Net-(LED0-PadC)") (class "Default")
      (node (ref "LED0") (pin "C") (pinfunction "C_C") (pintype "passive"))
      (node (ref "R49") (pin "1") (pinfunction "1_1") (pintype "passive"))
    )
    (net (code "194") (name "Net-(LED1-PadC)") (class "Default")
      (node (ref "LED1") (pin "C") (pinfunction "C_C") (pintype "passive"))
      (node (ref "R50") (pin "1") (pinfunction "1_1") (pintype "passive"))
    )
    (net (code "195") (name "Net-(LED2-PadC)") (class "Default")
      (node (ref "LED2") (pin "C") (pinfunction "C_C") (pintype "passive"))
      (node (ref "R51") (pin "1") (pinfunction "1_1") (pintype "passive"))
    )
    (net (code "196") (name "Net-(LED3-PadC)") (class "Default")
      (node (ref "LED3") (pin "C") (pinfunction "C_C") (pintype "passive"))
      (node (ref "R52") (pin "1") (pinfunction "1_1") (pintype "passive"))
    )
    (net (code "197") (name "Net-(LED4-PadC)") (class "Default")
      (node (ref "LED4") (pin "C") (pinfunction "C_C") (pintype "passive"))
      (node (ref "R27") (pin "1") (pinfunction "1_1") (pintype "passive"))
    )
    (net (code "198") (name "Net-(LED5-PadC)") (class "Default")
      (node (ref "LED5") (pin "C") (pinfunction "C_C") (pintype "passive"))
      (node (ref "R28") (pin "1") (pinfunction "1_1") (pintype "passive"))
    )
    (net (code "199") (name "Net-(LED6-PadC)") (class "Default")
      (node (ref "LED6") (pin "C") (pinfunction "C_C") (pintype "passive"))
      (node (ref "R29") (pin "1") (pinfunction "1_1") (pintype "passive"))
    )
    (net (code "200") (name "Net-(LED7-PadC)") (class "Default")
      (node (ref "LED7") (pin "C") (pinfunction "C_C") (pintype "passive"))
      (node (ref "R30") (pin "1") (pinfunction "1_1") (pintype "passive"))
    )
    (net (code "201") (name "Net-(LED8-PadC)") (class "Default")
      (node (ref "LED8") (pin "C") (pinfunction "C_C") (pintype "passive"))
      (node (ref "R57") (pin "1") (pinfunction "1_1") (pintype "passive"))
    )
    (net (code "202") (name "Net-(LED9-PadC)") (class "Default")
      (node (ref "LED9") (pin "C") (pinfunction "C_C") (pintype "passive"))
      (node (ref "R58") (pin "1") (pinfunction "1_1") (pintype "passive"))
    )
    (net (code "203") (name "Net-(LED10-PadC)") (class "Default")
      (node (ref "LED10") (pin "C") (pinfunction "C_C") (pintype "passive"))
      (node (ref "R7") (pin "1") (pinfunction "1_1") (pintype "passive"))
    )
    (net (code "204") (name "Net-(LED11-PadC)") (class "Default")
      (node (ref "LED11") (pin "C") (pinfunction "C_C") (pintype "passive"))
      (node (ref "R34") (pin "1") (pinfunction "1_1") (pintype "passive"))
    )
    (net (code "205") (name "Net-(LED12-PadA)") (class "Default")
      (node (ref "LED12") (pin "A") (pinfunction "A_A") (pintype "passive"))
      (node (ref "R_MD3") (pin "1") (pinfunction "1_1") (pintype "passive"))
    )
    (net (code "206") (name "Net-(LED13-PadC)") (class "Default")
      (node (ref "LED13") (pin "C") (pinfunction "C_C") (pintype "passive"))
      (node (ref "R71") (pin "1") (pinfunction "1_1") (pintype "passive"))
    )
    (net (code "207") (name "Net-(LED14-PadC)") (class "Default")
      (node (ref "LED14") (pin "C") (pinfunction "C_C") (pintype "passive"))
      (node (ref "R70") (pin "1") (pinfunction "1_1") (pintype "passive"))
    )
    (net (code "208") (name "Net-(LED15-PadC)") (class "Default")
      (node (ref "LED15") (pin "C") (pinfunction "C_C") (pintype "passive"))
      (node (ref "R68") (pin "1") (pinfunction "1_1") (pintype "passive"))
    )
    (net (code "209") (name "Net-(LED16-PadC)") (class "Default")
      (node (ref "LED16") (pin "C") (pinfunction "C_C") (pintype "passive"))
      (node (ref "R69") (pin "1") (pinfunction "1_1") (pintype "passive"))
    )
    (net (code "210") (name "Net-(MCU1-P35{slash}NMI)") (class "Default")
      (node (ref "MCU1") (pin "15") (pinfunction "P35/NMI_15") (pintype "input"))
      (node (ref "R5") (pin "2") (pinfunction "2_2") (pintype "passive"))
    )
    (net (code "211") (name "Net-(Q4-D)") (class "Default")
      (node (ref "Q4") (pin "3") (pinfunction "D_3") (pintype "bidirectional"))
      (node (ref "SG2") (pin "2") (pinfunction "2_2") (pintype "passive"))
    )
    (net (code "212") (name "Net-(R32-Pad2)") (class "Default")
      (node (ref "R32") (pin "2") (pinfunction "2_2") (pintype "passive"))
      (node (ref "R64") (pin "1") (pinfunction "1_1") (pintype "passive"))
    )
    (net (code "213") (name "Net-(R_MD4-Pad2)") (class "Default")
      (node (ref "R_MD4") (pin "2") (pinfunction "2_2") (pintype "passive"))
      (node (ref "U$82") (pin "3") (pinfunction "3_3") (pintype "bidirectional"))
      (node (ref "U$82") (pin "6") (pinfunction "6_6") (pintype "bidirectional"))
    )
    (net (code "214") (name "Net-(S6-P)") (class "Default")
      (node (ref "S6") (pin "2") (pinfunction "P_2") (pintype "passive"))
      (node (ref "U$22") (pin "1") (pinfunction "1_1") (pintype "bidirectional"))
      (node (ref "U$23") (pin "1") (pinfunction "1_1") (pintype "bidirectional"))
    )
    (net (code "215") (name "Net-(U$4-PC7{slash}MTIOC3A{slash}MTCLKB{slash}TXD8)") (class "Default")
      (node (ref "R67") (pin "2") (pinfunction "2_2") (pintype "passive"))
      (node (ref "U$4") (pin "45") (pinfunction "PC7/MTIOC3A/MTCLKB/TXD8_45") (pintype "bidirectional"))
    )
    (net (code "216") (name "Net-(U$4-XCIN)") (class "Default")
      (node (ref "R_XCIN") (pin "2") (pinfunction "2_2") (pintype "passive"))
      (node (ref "U$4") (pin "8") (pinfunction "XCIN_8") (pintype "bidirectional"))
    )
    (net (code "217") (name "Net-(U$18-1)") (class "Default")
      (node (ref "R1") (pin "1") (pinfunction "1_1") (pintype "passive"))
      (node (ref "U$18") (pin "P$1") (pinfunction "1_P$1") (pintype "passive"))
      (node (ref "U$18") (pin "P$2") (pinfunction "2_P$2") (pintype "passive"))
      (node (ref "U$18") (pin "P$3") (pinfunction "3_P$3") (pintype "passive"))
    )
    (net (code "218") (name "Net-(U$18-5)") (class "Default")
      (node (ref "R11") (pin "1") (pinfunction "1_1") (pintype "passive"))
      (node (ref "U$18") (pin "P$5") (pinfunction "5_P$5") (pintype "passive"))
    )
    (net (code "219") (name "Net-(U$19-CANH)") (class "Default")
      (node (ref "R13") (pin "2") (pinfunction "2_2") (pintype "passive"))
      (node (ref "R65") (pin "2") (pinfunction "2_2") (pintype "passive"))
      (node (ref "U$19") (pin "7") (pinfunction "CANH_7") (pintype "bidirectional"))
    )
    (net (code "220") (name "Net-(U$20-1)") (class "Default")
      (node (ref "R38") (pin "1") (pinfunction "1_1") (pintype "passive"))
      (node (ref "U$20") (pin "P$1") (pinfunction "1_P$1") (pintype "passive"))
      (node (ref "U$20") (pin "P$2") (pinfunction "2_P$2") (pintype "passive"))
      (node (ref "U$20") (pin "P$3") (pinfunction "3_P$3") (pintype "passive"))
    )
    (net (code "221") (name "Net-(U$21-1)") (class "Default")
      (node (ref "R32") (pin "1") (pinfunction "1_1") (pintype "passive"))
      (node (ref "U$21") (pin "P$1") (pinfunction "1_P$1") (pintype "passive"))
      (node (ref "U$21") (pin "P$2") (pinfunction "2_P$2") (pintype "passive"))
      (node (ref "U$21") (pin "P$3") (pinfunction "3_P$3") (pintype "passive"))
    )
    (net (code "222") (name "Net-(U$21-5)") (class "Default")
      (node (ref "R13") (pin "1") (pinfunction "1_1") (pintype "passive"))
      (node (ref "U$21") (pin "P$5") (pinfunction "5_P$5") (pintype "passive"))
    )
    (net (code "223") (name "Net-(U$25-1)") (class "Default")
      (node (ref "R12") (pin "1") (pinfunction "1_1") (pintype "passive"))
      (node (ref "U$25") (pin "P$1") (pinfunction "1_P$1") (pintype "passive"))
      (node (ref "U$25") (pin "P$2") (pinfunction "2_P$2") (pintype "passive"))
      (node (ref "U$25") (pin "P$3") (pinfunction "3_P$3") (pintype "passive"))
    )
    (net (code "224") (name "Net-(U$28-CLK)") (class "Default")
      (node (ref "R35") (pin "2") (pinfunction "2_2") (pintype "passive"))
      (node (ref "U$28") (pin "5") (pinfunction "CLK_5") (pintype "bidirectional"))
    )
    (net (code "225") (name "Net-(U$28-DO)") (class "Default")
      (node (ref "R10") (pin "1") (pinfunction "1_1") (pintype "passive"))
      (node (ref "R4") (pin "2") (pinfunction "2_2") (pintype "passive"))
      (node (ref "U$28") (pin "7") (pinfunction "DO_7") (pintype "bidirectional"))
    )
    (net (code "226") (name "Net-(U$28-VDD)") (class "Default")
      (node (ref "U$2") (pin "1") (pinfunction "1_1") (pintype "passive"))
      (node (ref "U$28") (pin "4") (pinfunction "VDD_4") (pintype "bidirectional"))
    )
    (net (code "227") (name "Net-(U$57-CLK)") (class "Default")
      (node (ref "R72") (pin "2") (pinfunction "2_2") (pintype "passive"))
      (node (ref "U$57") (pin "5") (pinfunction "CLK_5") (pintype "bidirectional"))
    )
    (net (code "228") (name "Net-(U$57-VDD)") (class "Default")
      (node (ref "U$57") (pin "4") (pinfunction "VDD_4") (pintype "bidirectional"))
      (node (ref "U$58") (pin "1") (pinfunction "1_1") (pintype "passive"))
    )
    (net (code "229") (name "Net-(U$65-VO)") (class "Default")
      (node (ref "R31") (pin "S") (pinfunction "S_S") (pintype "passive"))
      (node (ref "U$65") (pin "3") (pinfunction "VO_3") (pintype "bidirectional"))
    )
    (net (code "230") (name "Net-(U$68A-I)") (class "Default")
      (node (ref "U$68") (pin "2") (pinfunction "I_2") (pintype "input"))
      (node (ref "U$82") (pin "2") (pinfunction "2_2") (pintype "bidirectional"))
      (node (ref "U$82") (pin "5") (pinfunction "5_5") (pintype "bidirectional"))
    )
    (net (code "231") (name "Net-(U$75-VBUS)") (class "Default")
      (node (ref "U$75") (pin "1") (pinfunction "VBUS_1") (pintype "bidirectional"))
      (node (ref "U$76") (pin "1") (pinfunction "1_1") (pintype "passive"))
    )
    (net (code "232") (name "Net-(U$77-VBUS)") (class "Default")
      (node (ref "U$77") (pin "1") (pinfunction "VBUS_1") (pintype "bidirectional"))
      (node (ref "U$78") (pin "1") (pinfunction "1_1") (pintype "passive"))
    )
    (net (code "233") (name "Net-(X2B-S)") (class "Default")
      (node (ref "U$40") (pin "1") (pinfunction "1_1") (pintype "passive"))
      (node (ref "X2") (pin "10") (pinfunction "S_10") (pintype "passive"))
    )
    (net (code "234") (name "Net-(X2C-S)") (class "Default")
      (node (ref "U$41") (pin "1") (pinfunction "1_1") (pintype "passive"))
      (node (ref "X2") (pin "11") (pinfunction "S_11") (pintype "passive"))
    )
    (net (code "235") (name "Net-(X2D-S)") (class "Default")
      (node (ref "U$42") (pin "1") (pinfunction "1_1") (pintype "passive"))
      (node (ref "X2") (pin "12") (pinfunction "S_12") (pintype "passive"))
    )
    (net (code "236") (name "Net-(X2E-S)") (class "Default")
      (node (ref "U$43") (pin "1") (pinfunction "1_1") (pintype "passive"))
      (node (ref "X2") (pin "13") (pinfunction "S_13") (pintype "passive"))
    )
    (net (code "237") (name "Net-(X2F-S)") (class "Default")
      (node (ref "U$44") (pin "1") (pinfunction "1_1") (pintype "passive"))
      (node (ref "X2") (pin "14") (pinfunction "S_14") (pintype "passive"))
    )
    (net (code "238") (name "Net-(X2G-S)") (class "Default")
      (node (ref "U$45") (pin "1") (pinfunction "1_1") (pintype "passive"))
      (node (ref "X2") (pin "15") (pinfunction "S_15") (pintype "passive"))
    )
    (net (code "239") (name "Net-(X2H-S)") (class "Default")
      (node (ref "U$46") (pin "1") (pinfunction "1_1") (pintype "passive"))
      (node (ref "X2") (pin "16") (pinfunction "S_16") (pintype "passive"))
    )
    (net (code "240") (name "Net-(X2J-S)") (class "Default")
      (node (ref "U$33") (pin "1") (pinfunction "1_1") (pintype "passive"))
      (node (ref "X2") (pin "3") (pinfunction "S_3") (pintype "passive"))
    )
    (net (code "241") (name "Net-(X2K-S)") (class "Default")
      (node (ref "U$34") (pin "1") (pinfunction "1_1") (pintype "passive"))
      (node (ref "X2") (pin "4") (pinfunction "S_4") (pintype "passive"))
    )
    (net (code "242") (name "Net-(X2L-S)") (class "Default")
      (node (ref "U$35") (pin "1") (pinfunction "1_1") (pintype "passive"))
      (node (ref "X2") (pin "5") (pinfunction "S_5") (pintype "passive"))
    )
    (net (code "243") (name "Net-(X2M-S)") (class "Default")
      (node (ref "U$36") (pin "1") (pinfunction "1_1") (pintype "passive"))
      (node (ref "X2") (pin "6") (pinfunction "S_6") (pintype "passive"))
    )
    (net (code "244") (name "Net-(X2N-S)") (class "Default")
      (node (ref "U$37") (pin "1") (pinfunction "1_1") (pintype "passive"))
      (node (ref "X2") (pin "7") (pinfunction "S_7") (pintype "passive"))
    )
    (net (code "245") (name "Net-(X2O-S)") (class "Default")
      (node (ref "U$38") (pin "1") (pinfunction "1_1") (pintype "passive"))
      (node (ref "X2") (pin "8") (pinfunction "S_8") (pintype "passive"))
    )
    (net (code "246") (name "Net-(X2P-S)") (class "Default")
      (node (ref "U$39") (pin "1") (pinfunction "1_1") (pintype "passive"))
      (node (ref "X2") (pin "9") (pinfunction "S_9") (pintype "passive"))
    )
    (net (code "247") (name "Net-(X3B-S)") (class "Default")
      (node (ref "U$54") (pin "1") (pinfunction "1_1") (pintype "passive"))
      (node (ref "X3") (pin "10") (pinfunction "S_10") (pintype "passive"))
    )
    (net (code "248") (name "Net-(X3D-S)") (class "Default")
      (node (ref "U$47") (pin "1") (pinfunction "1_1") (pintype "passive"))
      (node (ref "X3") (pin "3") (pinfunction "S_3") (pintype "passive"))
    )
    (net (code "249") (name "Net-(X3E-S)") (class "Default")
      (node (ref "U$48") (pin "1") (pinfunction "1_1") (pintype "passive"))
      (node (ref "X3") (pin "4") (pinfunction "S_4") (pintype "passive"))
    )
    (net (code "250") (name "Net-(X3F-S)") (class "Default")
      (node (ref "U$49") (pin "1") (pinfunction "1_1") (pintype "passive"))
      (node (ref "X3") (pin "5") (pinfunction "S_5") (pintype "passive"))
    )
    (net (code "251") (name "Net-(X3G-S)") (class "Default")
      (node (ref "U$50") (pin "1") (pinfunction "1_1") (pintype "passive"))
      (node (ref "X3") (pin "6") (pinfunction "S_6") (pintype "passive"))
    )
    (net (code "252") (name "Net-(X3H-S)") (class "Default")
      (node (ref "U$51") (pin "1") (pinfunction "1_1") (pintype "passive"))
      (node (ref "X3") (pin "7") (pinfunction "S_7") (pintype "passive"))
    )
    (net (code "253") (name "Net-(X3I-S)") (class "Default")
      (node (ref "U$52") (pin "1") (pinfunction "1_1") (pintype "passive"))
      (node (ref "X3") (pin "8") (pinfunction "S_8") (pintype "passive"))
    )
    (net (code "254") (name "Net-(X3J-S)") (class "Default")
      (node (ref "U$53") (pin "1") (pinfunction "1_1") (pintype "passive"))
      (node (ref "X3") (pin "9") (pinfunction "S_9") (pintype "passive"))
    )
    (net (code "255") (name "VCC") (class "Default")
      (node (ref "C16") (pin "1") (pinfunction "1_1") (pintype "passive"))
      (node (ref "C32") (pin "2") (pinfunction "2_2") (pintype "passive"))
      (node (ref "C34") (pin "2") (pinfunction "2_2") (pintype "passive"))
      (node (ref "C37") (pin "2") (pinfunction "2_2") (pintype "passive"))
      (node (ref "D1") (pin "A") (pinfunction "A_A") (pintype "passive"))
      (node (ref "D14") (pin "A") (pinfunction "A_A") (pintype "passive"))
      (node (ref "IC6") (pin "42") (pinfunction "RB6_42") (pintype "bidirectional"))
      (node (ref "IC7") (pin "42") (pinfunction "RB6_42") (pintype "bidirectional"))
      (node (ref "R1") (pin "2") (pinfunction "2_2") (pintype "passive"))
      (node (ref "R12") (pin "2") (pinfunction "2_2") (pintype "passive"))
      (node (ref "R31") (pin "A") (pinfunction "A_A") (pintype "passive"))
      (node (ref "R38") (pin "2") (pinfunction "2_2") (pintype "passive"))
      (node (ref "R64") (pin "2") (pinfunction "2_2") (pintype "passive"))
      (node (ref "S6") (pin "1") (pinfunction "O_1") (pintype "passive"))
      (node (ref "SG2") (pin "1") (pinfunction "1_1") (pintype "passive"))
      (node (ref "U$14") (pin "1") (pinfunction "1_1") (pintype "bidirectional"))
      (node (ref "U$15") (pin "1") (pinfunction "1_1") (pintype "bidirectional"))
      (node (ref "U$17") (pin "3") (pinfunction "VDD_3") (pintype "power_in"))
      (node (ref "U$19") (pin "3") (pinfunction "VDD_3") (pintype "power_in"))
      (node (ref "U$24") (pin "1") (pinfunction "1_1") (pintype "bidirectional"))
      (node (ref "U$26") (pin "1") (pinfunction "IN_1") (pintype "power_in"))
      (node (ref "U$27") (pin "1") (pinfunction "1_1") (pintype "bidirectional"))
      (node (ref "U$29") (pin "1") (pinfunction "1_1") (pintype "bidirectional"))
      (node (ref "U$30") (pin "1") (pinfunction "1_1") (pintype "bidirectional"))
      (node (ref "U$64") (pin "3") (pinfunction "VDD_3") (pintype "power_in"))
      (node (ref "U$65") (pin "1") (pinfunction "VDD_1") (pintype "power_in"))
      (node (ref "U$67") (pin "1") (pinfunction "VBUS_1") (pintype "bidirectional"))
      (node (ref "U$76") (pin "2") (pinfunction "2_2") (pintype "passive"))
      (node (ref "U$78") (pin "2") (pinfunction "2_2") (pintype "passive"))
    )
    (net (code "256") (name "unconnected-(IC2-CBUS0-Pad23)") (class "Default")
      (node (ref "IC2") (pin "23") (pinfunction "CBUS0_23") (pintype "bidirectional"))
    )
    (net (code "257") (name "unconnected-(IC2-CBUS1-Pad22)") (class "Default")
      (node (ref "IC2") (pin "22") (pinfunction "CBUS1_22") (pintype "bidirectional"))
    )
    (net (code "258") (name "unconnected-(IC2-CBUS2-Pad13)") (class "Default")
      (node (ref "IC2") (pin "13") (pinfunction "CBUS2_13") (pintype "bidirectional"))
    )
    (net (code "259") (name "unconnected-(IC2-CBUS3-Pad14)") (class "Default")
      (node (ref "IC2") (pin "14") (pinfunction "CBUS3_14") (pintype "bidirectional"))
    )
    (net (code "260") (name "unconnected-(IC2-CBUS4-Pad12)") (class "Default")
      (node (ref "IC2") (pin "12") (pinfunction "CBUS4_12") (pintype "bidirectional"))
    )
    (net (code "261") (name "unconnected-(IC2-OSCI-Pad27)") (class "Default")
      (node (ref "IC2") (pin "27") (pinfunction "OSCI_27") (pintype "input"))
    )
    (net (code "262") (name "unconnected-(IC2-OSCO-Pad28)") (class "Default")
      (node (ref "IC2") (pin "28") (pinfunction "OSCO_28") (pintype "output"))
    )
    (net (code "263") (name "unconnected-(IC2-~{CTS}-Pad11)") (class "Default")
      (node (ref "IC2") (pin "11") (pinfunction "~{CTS}_11") (pintype "input"))
    )
    (net (code "264") (name "unconnected-(IC2-~{DCD}-Pad10)") (class "Default")
      (node (ref "IC2") (pin "10") (pinfunction "~{DCD}_10") (pintype "input"))
    )
    (net (code "265") (name "unconnected-(IC2-~{DSR}-Pad9)") (class "Default")
      (node (ref "IC2") (pin "9") (pinfunction "~{DSR}_9") (pintype "input"))
    )
    (net (code "266") (name "unconnected-(IC2-~{DTR}-Pad2)") (class "Default")
      (node (ref "IC2") (pin "2") (pinfunction "~{DTR}_2") (pintype "output"))
    )
    (net (code "267") (name "unconnected-(IC2-~{RESET}-Pad19)") (class "Default")
      (node (ref "IC2") (pin "19") (pinfunction "~{RESET}_19") (pintype "input"))
    )
    (net (code "268") (name "unconnected-(IC2-~{RI}-Pad6)") (class "Default")
      (node (ref "IC2") (pin "6") (pinfunction "~{RI}_6") (pintype "input"))
    )
    (net (code "269") (name "unconnected-(IC2-~{RTS}-Pad3)") (class "Default")
      (node (ref "IC2") (pin "3") (pinfunction "~{RTS}_3") (pintype "output"))
    )
    (net (code "270") (name "unconnected-(IC4-CBUS0-Pad23)") (class "Default")
      (node (ref "IC4") (pin "23") (pinfunction "CBUS0_23") (pintype "bidirectional"))
    )
    (net (code "271") (name "unconnected-(IC4-CBUS1-Pad22)") (class "Default")
      (node (ref "IC4") (pin "22") (pinfunction "CBUS1_22") (pintype "bidirectional"))
    )
    (net (code "272") (name "unconnected-(IC4-CBUS2-Pad13)") (class "Default")
      (node (ref "IC4") (pin "13") (pinfunction "CBUS2_13") (pintype "bidirectional"))
    )
    (net (code "273") (name "unconnected-(IC4-CBUS3-Pad14)") (class "Default")
      (node (ref "IC4") (pin "14") (pinfunction "CBUS3_14") (pintype "bidirectional"))
    )
    (net (code "274") (name "unconnected-(IC4-CBUS4-Pad12)") (class "Default")
      (node (ref "IC4") (pin "12") (pinfunction "CBUS4_12") (pintype "bidirectional"))
    )
    (net (code "275") (name "unconnected-(IC4-OSCI-Pad27)") (class "Default")
      (node (ref "IC4") (pin "27") (pinfunction "OSCI_27") (pintype "input"))
    )
    (net (code "276") (name "unconnected-(IC4-OSCO-Pad28)") (class "Default")
      (node (ref "IC4") (pin "28") (pinfunction "OSCO_28") (pintype "output"))
    )
    (net (code "277") (name "unconnected-(IC4-~{CTS}-Pad11)") (class "Default")
      (node (ref "IC4") (pin "11") (pinfunction "~{CTS}_11") (pintype "input"))
    )
    (net (code "278") (name "unconnected-(IC4-~{DCD}-Pad10)") (class "Default")
      (node (ref "IC4") (pin "10") (pinfunction "~{DCD}_10") (pintype "input"))
    )
    (net (code "279") (name "unconnected-(IC4-~{DSR}-Pad9)") (class "Default")
      (node (ref "IC4") (pin "9") (pinfunction "~{DSR}_9") (pintype "input"))
    )
    (net (code "280") (name "unconnected-(IC4-~{DTR}-Pad2)") (class "Default")
      (node (ref "IC4") (pin "2") (pinfunction "~{DTR}_2") (pintype "output"))
    )
    (net (code "281") (name "unconnected-(IC4-~{RESET}-Pad19)") (class "Default")
      (node (ref "IC4") (pin "19") (pinfunction "~{RESET}_19") (pintype "input"))
    )
    (net (code "282") (name "unconnected-(IC4-~{RI}-Pad6)") (class "Default")
      (node (ref "IC4") (pin "6") (pinfunction "~{RI}_6") (pintype "input"))
    )
    (net (code "283") (name "unconnected-(IC4-~{RTS}-Pad3)") (class "Default")
      (node (ref "IC4") (pin "3") (pinfunction "~{RTS}_3") (pintype "output"))
    )
    (net (code "284") (name "unconnected-(IC5A-R2IN-Pad8)") (class "Default")
      (node (ref "IC5") (pin "8") (pinfunction "R2IN_8") (pintype "input"))
    )
    (net (code "285") (name "unconnected-(IC5A-R2OUT-Pad9)") (class "Default")
      (node (ref "IC5") (pin "9") (pinfunction "R2OUT_9") (pintype "output"))
    )
    (net (code "286") (name "unconnected-(IC5A-T2IN-Pad10)") (class "Default")
      (node (ref "IC5") (pin "10") (pinfunction "T2IN_10") (pintype "input"))
    )
    (net (code "287") (name "unconnected-(IC5A-T2OUT-Pad7)") (class "Default")
      (node (ref "IC5") (pin "7") (pinfunction "T2OUT_7") (pintype "output"))
    )
    (net (code "288") (name "unconnected-(IC6-RA0-Pad19)") (class "Default")
      (node (ref "IC6") (pin "19") (pinfunction "RA0_19") (pintype "bidirectional"))
    )
    (net (code "289") (name "unconnected-(IC6-RA1-Pad20)") (class "Default")
      (node (ref "IC6") (pin "20") (pinfunction "RA1_20") (pintype "bidirectional"))
    )
    (net (code "290") (name "unconnected-(IC6-RA2-Pad30)") (class "Default")
      (node (ref "IC6") (pin "30") (pinfunction "RA2_30") (pintype "bidirectional"))
    )
    (net (code "291") (name "unconnected-(IC6-RA3-Pad31)") (class "Default")
      (node (ref "IC6") (pin "31") (pinfunction "RA3_31") (pintype "bidirectional"))
    )
    (net (code "292") (name "unconnected-(IC6-RA4-Pad34)") (class "Default")
      (node (ref "IC6") (pin "34") (pinfunction "RA4_34") (pintype "bidirectional"))
    )
    (net (code "293") (name "unconnected-(IC6-RB2-Pad23)") (class "Default")
      (node (ref "IC6") (pin "23") (pinfunction "RB2_23") (pintype "bidirectional"))
    )
    (net (code "294") (name "unconnected-(IC6-RB3-Pad24)") (class "Default")
      (node (ref "IC6") (pin "24") (pinfunction "RB3_24") (pintype "bidirectional"))
    )
    (net (code "295") (name "unconnected-(IC6-RB4-Pad33)") (class "Default")
      (node (ref "IC6") (pin "33") (pinfunction "RB4_33") (pintype "bidirectional"))
    )
    (net (code "296") (name "unconnected-(IC6-RB5-Pad41)") (class "Default")
      (node (ref "IC6") (pin "41") (pinfunction "RB5_41") (pintype "bidirectional"))
    )
    (net (code "297") (name "unconnected-(IC6-RB7-Pad43)") (class "Default")
      (node (ref "IC6") (pin "43") (pinfunction "RB7_43") (pintype "bidirectional"))
    )
    (net (code "298") (name "unconnected-(IC6-RB8-Pad44)") (class "Default")
      (node (ref "IC6") (pin "44") (pinfunction "RB8_44") (pintype "bidirectional"))
    )
    (net (code "299") (name "unconnected-(IC6-RB13-Pad11)") (class "Default")
      (node (ref "IC6") (pin "11") (pinfunction "RB13_11") (pintype "bidirectional"))
    )
    (net (code "300") (name "unconnected-(IC6-RC0-Pad25)") (class "Default")
      (node (ref "IC6") (pin "25") (pinfunction "RC0_25") (pintype "bidirectional"))
    )
    (net (code "301") (name "unconnected-(IC6-RC1-Pad26)") (class "Default")
      (node (ref "IC6") (pin "26") (pinfunction "RC1_26") (pintype "bidirectional"))
    )
    (net (code "302") (name "unconnected-(IC6-RC2-Pad27)") (class "Default")
      (node (ref "IC6") (pin "27") (pinfunction "RC2_27") (pintype "bidirectional"))
    )
    (net (code "303") (name "unconnected-(IC6-RC3-Pad36)") (class "Default")
      (node (ref "IC6") (pin "36") (pinfunction "RC3_36") (pintype "bidirectional"))
    )
    (net (code "304") (name "unconnected-(IC6-RC4-Pad37)") (class "Default")
      (node (ref "IC6") (pin "37") (pinfunction "RC4_37") (pintype "bidirectional"))
    )
    (net (code "305") (name "unconnected-(IC6-RC5-Pad38)") (class "Default")
      (node (ref "IC6") (pin "38") (pinfunction "RC5_38") (pintype "bidirectional"))
    )
    (net (code "306") (name "unconnected-(IC6-TCK-Pad13)") (class "Default")
      (node (ref "IC6") (pin "13") (pinfunction "TCK_13") (pintype "input"))
    )
    (net (code "307") (name "unconnected-(IC6-TDI-Pad35)") (class "Default")
      (node (ref "IC6") (pin "35") (pinfunction "TDI_35") (pintype "input"))
    )
    (net (code "308") (name "unconnected-(IC6-TDO-Pad32)") (class "Default")
      (node (ref "IC6") (pin "32") (pinfunction "TDO_32") (pintype "output"))
    )
    (net (code "309") (name "unconnected-(IC6-TMS-Pad12)") (class "Default")
      (node (ref "IC6") (pin "12") (pinfunction "TMS_12") (pintype "input"))
    )
    (net (code "310") (name "unconnected-(IC7-RA0-Pad19)") (class "Default")
      (node (ref "IC7") (pin "19") (pinfunction "RA0_19") (pintype "bidirectional"))
    )
    (net (code "311") (name "unconnected-(IC7-RA1-Pad20)") (class "Default")
      (node (ref "IC7") (pin "20") (pinfunction "RA1_20") (pintype "bidirectional"))
    )
    (net (code "312") (name "unconnected-(IC7-RA2-Pad30)") (class "Default")
      (node (ref "IC7") (pin "30") (pinfunction "RA2_30") (pintype "bidirectional"))
    )
    (net (code "313") (name "unconnected-(IC7-RA3-Pad31)") (class "Default")
      (node (ref "IC7") (pin "31") (pinfunction "RA3_31") (pintype "bidirectional"))
    )
    (net (code "314") (name "unconnected-(IC7-RA4-Pad34)") (class "Default")
      (node (ref "IC7") (pin "34") (pinfunction "RA4_34") (pintype "bidirectional"))
    )
    (net (code "315") (name "unconnected-(IC7-RB2-Pad23)") (class "Default")
      (node (ref "IC7") (pin "23") (pinfunction "RB2_23") (pintype "bidirectional"))
    )
    (net (code "316") (name "unconnected-(IC7-RB3-Pad24)") (class "Default")
      (node (ref "IC7") (pin "24") (pinfunction "RB3_24") (pintype "bidirectional"))
    )
    (net (code "317") (name "unconnected-(IC7-RB4-Pad33)") (class "Default")
      (node (ref "IC7") (pin "33") (pinfunction "RB4_33") (pintype "bidirectional"))
    )
    (net (code "318") (name "unconnected-(IC7-RB5-Pad41)") (class "Default")
      (node (ref "IC7") (pin "41") (pinfunction "RB5_41") (pintype "bidirectional"))
    )
    (net (code "319") (name "unconnected-(IC7-RB7-Pad43)") (class "Default")
      (node (ref "IC7") (pin "43") (pinfunction "RB7_43") (pintype "bidirectional"))
    )
    (net (code "320") (name "unconnected-(IC7-RB8-Pad44)") (class "Default")
      (node (ref "IC7") (pin "44") (pinfunction "RB8_44") (pintype "bidirectional"))
    )
    (net (code "321") (name "unconnected-(IC7-RB13-Pad11)") (class "Default")
      (node (ref "IC7") (pin "11") (pinfunction "RB13_11") (pintype "bidirectional"))
    )
    (net (code "322") (name "unconnected-(IC7-RC0-Pad25)") (class "Default")
      (node (ref "IC7") (pin "25") (pinfunction "RC0_25") (pintype "bidirectional"))
    )
    (net (code "323") (name "unconnected-(IC7-RC1-Pad26)") (class "Default")
      (node (ref "IC7") (pin "26") (pinfunction "RC1_26") (pintype "bidirectional"))
    )
    (net (code "324") (name "unconnected-(IC7-RC2-Pad27)") (class "Default")
      (node (ref "IC7") (pin "27") (pinfunction "RC2_27") (pintype "bidirectional"))
    )
    (net (code "325") (name "unconnected-(IC7-RC3-Pad36)") (class "Default")
      (node (ref "IC7") (pin "36") (pinfunction "RC3_36") (pintype "bidirectional"))
    )
    (net (code "326") (name "unconnected-(IC7-RC4-Pad37)") (class "Default")
      (node (ref "IC7") (pin "37") (pinfunction "RC4_37") (pintype "bidirectional"))
    )
    (net (code "327") (name "unconnected-(IC7-RC5-Pad38)") (class "Default")
      (node (ref "IC7") (pin "38") (pinfunction "RC5_38") (pintype "bidirectional"))
    )
    (net (code "328") (name "unconnected-(IC7-TCK-Pad13)") (class "Default")
      (node (ref "IC7") (pin "13") (pinfunction "TCK_13") (pintype "input"))
    )
    (net (code "329") (name "unconnected-(IC7-TDI-Pad35)") (class "Default")
      (node (ref "IC7") (pin "35") (pinfunction "TDI_35") (pintype "input"))
    )
    (net (code "330") (name "unconnected-(IC7-TDO-Pad32)") (class "Default")
      (node (ref "IC7") (pin "32") (pinfunction "TDO_32") (pintype "output"))
    )
    (net (code "331") (name "unconnected-(IC7-TMS-Pad12)") (class "Default")
      (node (ref "IC7") (pin "12") (pinfunction "TMS_12") (pintype "input"))
    )
    (net (code "332") (name "unconnected-(MCU1-BCLK{slash}P53-Pad41)") (class "Default")
      (node (ref "MCU1") (pin "41") (pinfunction "BCLK/P53_41") (pintype "bidirectional"))
    )
    (net (code "333") (name "unconnected-(MCU1-P05{slash}DA1-Pad100)") (class "Default")
      (node (ref "MCU1") (pin "100") (pinfunction "P05/DA1_100") (pintype "bidirectional"))
    )
    (net (code "334") (name "unconnected-(MCU1-P07{slash}IRQ15-A-Pad98)") (class "Default")
      (node (ref "MCU1") (pin "98") (pinfunction "P07/IRQ15-A_98") (pintype "bidirectional"))
    )
    (net (code "335") (name "unconnected-(MCU1-P12{slash}SCL0-Pad34)") (class "Default")
      (node (ref "MCU1") (pin "34") (pinfunction "P12/SCL0_34") (pintype "bidirectional"))
    )
    (net (code "336") (name "unconnected-(MCU1-P13{slash}SDA0-Pad33)") (class "Default")
      (node (ref "MCU1") (pin "33") (pinfunction "P13/SDA0_33") (pintype "bidirectional"))
    )
    (net (code "337") (name "unconnected-(MCU1-P14{slash}USB0_DPUPE-B-Pad32)") (class "Default")
      (node (ref "MCU1") (pin "32") (pinfunction "P14/USB0_DPUPE-B_32") (pintype "bidirectional"))
    )
    (net (code "338") (name "unconnected-(MCU1-P22{slash}MTCLKC-A-Pad26)") (class "Default")
      (node (ref "MCU1") (pin "26") (pinfunction "P22/MTCLKC-A_26") (pintype "bidirectional"))
    )
    (net (code "339") (name "unconnected-(MCU1-P24{slash}MTCLKA-Pad24)") (class "Default")
      (node (ref "MCU1") (pin "24") (pinfunction "P24/MTCLKA_24") (pintype "bidirectional"))
    )
    (net (code "340") (name "unconnected-(MCU1-P27{slash}MTIOC2B-Pad21)") (class "Default")
      (node (ref "MCU1") (pin "21") (pinfunction "P27/MTIOC2B_21") (pintype "bidirectional"))
    )
    (net (code "341") (name "unconnected-(MCU1-P31{slash}MTIOC4D-A-Pad19)") (class "Default")
      (node (ref "MCU1") (pin "19") (pinfunction "P31/MTIOC4D-A_19") (pintype "bidirectional"))
    )
    (net (code "342") (name "unconnected-(MCU1-P34{slash}MTIOC0A-Pad16)") (class "Default")
      (node (ref "MCU1") (pin "16") (pinfunction "P34/MTIOC0A_16") (pintype "bidirectional"))
    )
    (net (code "343") (name "unconnected-(MCU1-P51-Pad43)") (class "Default")
      (node (ref "MCU1") (pin "43") (pinfunction "P51_43") (pintype "bidirectional"))
    )
    (net (code "344") (name "unconnected-(MCU1-P54-Pad40)") (class "Default")
      (node (ref "MCU1") (pin "40") (pinfunction "P54_40") (pintype "bidirectional"))
    )
    (net (code "345") (name "unconnected-(MCU1-P55-Pad39)") (class "Default")
      (node (ref "MCU1") (pin "39") (pinfunction "P55_39") (pintype "bidirectional"))
    )
    (net (code "346") (name "unconnected-(MCU1-PA0{slash}MTIOC6A-Pad70)") (class "Default")
      (node (ref "MCU1") (pin "70") (pinfunction "PA0/MTIOC6A_70") (pintype "bidirectional"))
    )
    (net (code "347") (name "unconnected-(MCU1-PA1{slash}MTIOC6B-Pad69)") (class "Default")
      (node (ref "MCU1") (pin "69") (pinfunction "PA1/MTIOC6B_69") (pintype "bidirectional"))
    )
    (net (code "348") (name "unconnected-(MCU1-PB0{slash}MTIOC9A-Pad61)") (class "Default")
      (node (ref "MCU1") (pin "61") (pinfunction "PB0/MTIOC9A_61") (pintype "bidirectional"))
    )
    (net (code "349") (name "unconnected-(MCU1-PB1{slash}MTIOC9C-Pad59)") (class "Default")
      (node (ref "MCU1") (pin "59") (pinfunction "PB1/MTIOC9C_59") (pintype "bidirectional"))
    )
    (net (code "350") (name "unconnected-(MCU1-PB2{slash}MTIOC9B{slash}MTCLKG-B-Pad58)") (class "Default")
      (node (ref "MCU1") (pin "58") (pinfunction "PB2/MTIOC9B/MTCLKG-B_58") (pintype "bidirectional"))
    )
    (net (code "351") (name "unconnected-(MCU1-PB3{slash}MTIOC9D{slash}MTCLKH-B-Pad57)") (class "Default")
      (node (ref "MCU1") (pin "57") (pinfunction "PB3/MTIOC9D/MTCLKH-B_57") (pintype "bidirectional"))
    )
    (net (code "352") (name "unconnected-(MCU1-PD4-Pad82)") (class "Default")
      (node (ref "MCU1") (pin "82") (pinfunction "PD4_82") (pintype "bidirectional"))
    )
    (net (code "353") (name "unconnected-(MCU1-PD5-Pad81)") (class "Default")
      (node (ref "MCU1") (pin "81") (pinfunction "PD5_81") (pintype "bidirectional"))
    )
    (net (code "354") (name "unconnected-(MCU1-PD6-Pad80)") (class "Default")
      (node (ref "MCU1") (pin "80") (pinfunction "PD6_80") (pintype "bidirectional"))
    )
    (net (code "355") (name "unconnected-(MCU1-PD7-Pad79)") (class "Default")
      (node (ref "MCU1") (pin "79") (pinfunction "PD7_79") (pintype "bidirectional"))
    )
    (net (code "356") (name "unconnected-(MCU1-PE0-Pad78)") (class "Default")
      (node (ref "MCU1") (pin "78") (pinfunction "PE0_78") (pintype "bidirectional"))
    )
    (net (code "357") (name "unconnected-(MCU1-PE1-Pad77)") (class "Default")
      (node (ref "MCU1") (pin "77") (pinfunction "PE1_77") (pintype "bidirectional"))
    )
    (net (code "358") (name "unconnected-(MCU1-PE2-Pad76)") (class "Default")
      (node (ref "MCU1") (pin "76") (pinfunction "PE2_76") (pintype "bidirectional"))
    )
    (net (code "359") (name "unconnected-(MCU1-PE3-Pad75)") (class "Default")
      (node (ref "MCU1") (pin "75") (pinfunction "PE3_75") (pintype "bidirectional"))
    )
    (net (code "360") (name "unconnected-(MCU1-XCOUT-Pad9)") (class "Default")
      (node (ref "MCU1") (pin "9") (pinfunction "XCOUT_9") (pintype "output"))
    )
    (net (code "361") (name "unconnected-(S6-S-Pad3)") (class "Default")
      (node (ref "S6") (pin "3") (pinfunction "S_3") (pintype "passive"))
    )
    (net (code "362") (name "unconnected-(U$4-P05{slash}DA1-Pad100)") (class "Default")
      (node (ref "U$4") (pin "100") (pinfunction "P05/DA1_100") (pintype "bidirectional"))
    )
    (net (code "363") (name "unconnected-(U$4-P07-Pad98)") (class "Default")
      (node (ref "U$4") (pin "98") (pinfunction "P07_98") (pintype "bidirectional"))
    )
    (net (code "364") (name "unconnected-(U$4-P12{slash}RXD2-Pad34)") (class "Default")
      (node (ref "U$4") (pin "34") (pinfunction "P12/RXD2_34") (pintype "bidirectional"))
    )
    (net (code "365") (name "unconnected-(U$4-P13{slash}MTIOC0B{slash}TXD2-Pad33)") (class "Default")
      (node (ref "U$4") (pin "33") (pinfunction "P13/MTIOC0B/TXD2_33") (pintype "bidirectional"))
    )
    (net (code "366") (name "unconnected-(U$4-P16{slash}MTIOC3C{slash}MTIOC3D{slash}TXD1{slash}RXD3-Pad30)") (class "Default")
      (node (ref "U$4") (pin "30") (pinfunction "P16/MTIOC3C/MTIOC3D/TXD1/RXD3_30") (pintype "bidirectional"))
    )
    (net (code "367") (name "unconnected-(U$4-P23{slash}MTIOC3D{slash}MTCLKD{slash}TXD3-Pad25)") (class "Default")
      (node (ref "U$4") (pin "25") (pinfunction "P23/MTIOC3D/MTCLKD/TXD3_25") (pintype "bidirectional"))
    )
    (net (code "368") (name "unconnected-(U$4-P24{slash}MTIOC4A{slash}MTCLKA{slash}SCK3-Pad24)") (class "Default")
      (node (ref "U$4") (pin "24") (pinfunction "P24/MTIOC4A/MTCLKA/SCK3_24") (pintype "bidirectional"))
    )
    (net (code "369") (name "unconnected-(U$4-P25{slash}MTIOC4C{slash}MTCLKB{slash}RXD3-Pad23)") (class "Default")
      (node (ref "U$4") (pin "23") (pinfunction "P25/MTIOC4C/MTCLKB/RXD3_23") (pintype "bidirectional"))
    )
    (net (code "370") (name "unconnected-(U$4-P27{slash}TCK{slash}MTIOC2B{slash}SCK1-Pad21)") (class "Default")
      (node (ref "U$4") (pin "21") (pinfunction "P27/TCK/MTIOC2B/SCK1_21") (pintype "bidirectional"))
    )
    (net (code "371") (name "unconnected-(U$4-P31{slash}TMS{slash}MTIOC4D-Pad19)") (class "Default")
      (node (ref "U$4") (pin "19") (pinfunction "P31/TMS/MTIOC4D_19") (pintype "bidirectional"))
    )
    (net (code "372") (name "unconnected-(U$4-P34{slash}MTIOC0A{slash}SCK6{slash}SCK0{slash}USB0_DPRPD-Pad16)") (class "Default")
      (node (ref "U$4") (pin "16") (pinfunction "P34/MTIOC0A/SCK6/SCK0/USB0_DPRPD_16") (pintype "bidirectional"))
    )
    (net (code "373") (name "unconnected-(U$4-P50{slash}TXD2-Pad44)") (class "Default")
      (node (ref "U$4") (pin "44") (pinfunction "P50/TXD2_44") (pintype "bidirectional"))
    )
    (net (code "374") (name "unconnected-(U$4-P51{slash}SCK2-Pad43)") (class "Default")
      (node (ref "U$4") (pin "43") (pinfunction "P51/SCK2_43") (pintype "bidirectional"))
    )
    (net (code "375") (name "unconnected-(U$4-P52{slash}RXD2-Pad42)") (class "Default")
      (node (ref "U$4") (pin "42") (pinfunction "P52/RXD2_42") (pintype "bidirectional"))
    )
    (net (code "376") (name "unconnected-(U$4-P53{slash}BCLK-Pad41)") (class "Default")
      (node (ref "U$4") (pin "41") (pinfunction "P53/BCLK_41") (pintype "bidirectional"))
    )
    (net (code "377") (name "unconnected-(U$4-PC1{slash}MTIOC3A{slash}TCLKA{slash}RXD5-Pad51)") (class "Default")
      (node (ref "U$4") (pin "51") (pinfunction "PC1/MTIOC3A/TCLKA/RXD5_51") (pintype "bidirectional"))
    )
    (net (code "378") (name "unconnected-(U$4-PC6{slash}MTIOC3C{slash}MTCLKA{slash}RXD8-Pad46)") (class "Default")
      (node (ref "U$4") (pin "46") (pinfunction "PC6/MTIOC3C/MTCLKA/RXD8_46") (pintype "bidirectional"))
    )
    (net (code "379") (name "unconnected-(U$4-PE3{slash}MTIOC4B{slash}AN1-Pad75)") (class "Default")
      (node (ref "U$4") (pin "75") (pinfunction "PE3/MTIOC4B/AN1_75") (pintype "bidirectional"))
    )
    (net (code "380") (name "unconnected-(U$4-PJ3{slash}MITIOC3C-Pad4)") (class "Default")
      (node (ref "U$4") (pin "4") (pinfunction "PJ3/MITIOC3C_4") (pintype "bidirectional"))
    )
    (net (code "381") (name "unconnected-(U$4-USB0_DM-Pad36)") (class "Default")
      (node (ref "U$4") (pin "36") (pinfunction "USB0_DM_36") (pintype "bidirectional"))
    )
    (net (code "382") (name "unconnected-(U$4-USB0_DP-Pad37)") (class "Default")
      (node (ref "U$4") (pin "37") (pinfunction "USB0_DP_37") (pintype "bidirectional"))
    )
    (net (code "383") (name "unconnected-(U$4-XCOUT-Pad9)") (class "Default")
      (node (ref "U$4") (pin "9") (pinfunction "XCOUT_9") (pintype "bidirectional"))
    )
    (net (code "384") (name "unconnected-(U$9-ID(NC)-Pad4)") (class "Default")
      (node (ref "U$9") (pin "4") (pinfunction "ID(NC)_4") (pintype "bidirectional"))
    )
    (net (code "385") (name "unconnected-(U$28-NC-Pad1)") (class "Default")
      (node (ref "U$28") (pin "1") (pinfunction "NC_1") (pintype "bidirectional"))
    )
    (net (code "386") (name "unconnected-(U$28-PadCD1)") (class "Default")
      (node (ref "U$28") (pin "CD1") (pinfunction "CD1_CD1") (pintype "bidirectional"))
    )
    (net (code "387") (name "unconnected-(U$28-PadCD2)") (class "Default")
      (node (ref "U$28") (pin "CD2") (pinfunction "CD2_CD2") (pintype "bidirectional"))
    )
    (net (code "388") (name "unconnected-(U$28-RSV-Pad8)") (class "Default")
      (node (ref "U$28") (pin "8") (pinfunction "RSV_8") (pintype "bidirectional"))
    )
    (net (code "389") (name "unconnected-(U$28-SHIELD-PadGND1)") (class "Default")
      (node (ref "U$28") (pin "GND1") (pinfunction "SHIELD_GND1") (pintype "bidirectional"))
    )
    (net (code "390") (name "unconnected-(U$28-SHIELD-PadGND2)") (class "Default")
      (node (ref "U$28") (pin "GND2") (pinfunction "SHIELD_GND2") (pintype "bidirectional"))
    )
    (net (code "391") (name "unconnected-(U$28-SHIELD-PadGND3)") (class "Default")
      (node (ref "U$28") (pin "GND3") (pinfunction "SHIELD_GND3") (pintype "bidirectional"))
    )
    (net (code "392") (name "unconnected-(U$28-SHIELD-PadGND4)") (class "Default")
      (node (ref "U$28") (pin "GND4") (pinfunction "SHIELD_GND4") (pintype "bidirectional"))
    )
    (net (code "393") (name "unconnected-(U$57-NC-Pad1)") (class "Default")
      (node (ref "U$57") (pin "1") (pinfunction "NC_1") (pintype "bidirectional"))
    )
    (net (code "394") (name "unconnected-(U$57-PadCD1)") (class "Default")
      (node (ref "U$57") (pin "CD1") (pinfunction "CD1_CD1") (pintype "bidirectional"))
    )
    (net (code "395") (name "unconnected-(U$57-PadCD2)") (class "Default")
      (node (ref "U$57") (pin "CD2") (pinfunction "CD2_CD2") (pintype "bidirectional"))
    )
    (net (code "396") (name "unconnected-(U$57-RSV-Pad8)") (class "Default")
      (node (ref "U$57") (pin "8") (pinfunction "RSV_8") (pintype "bidirectional"))
    )
    (net (code "397") (name "unconnected-(U$57-SHIELD-PadGND1)") (class "Default")
      (node (ref "U$57") (pin "GND1") (pinfunction "SHIELD_GND1") (pintype "bidirectional"))
    )
    (net (code "398") (name "unconnected-(U$57-SHIELD-PadGND2)") (class "Default")
      (node (ref "U$57") (pin "GND2") (pinfunction "SHIELD_GND2") (pintype "bidirectional"))
    )
    (net (code "399") (name "unconnected-(U$57-SHIELD-PadGND3)") (class "Default")
      (node (ref "U$57") (pin "GND3") (pinfunction "SHIELD_GND3") (pintype "bidirectional"))
    )
    (net (code "400") (name "unconnected-(U$57-SHIELD-PadGND4)") (class "Default")
      (node (ref "U$57") (pin "GND4") (pinfunction "SHIELD_GND4") (pintype "bidirectional"))
    )
    (net (code "401") (name "unconnected-(U$65-DB0-Pad7)") (class "Default")
      (node (ref "U$65") (pin "7") (pinfunction "DB0_7") (pintype "bidirectional"))
    )
    (net (code "402") (name "unconnected-(U$65-DB1-Pad8)") (class "Default")
      (node (ref "U$65") (pin "8") (pinfunction "DB1_8") (pintype "bidirectional"))
    )
    (net (code "403") (name "unconnected-(U$65-DB2-Pad9)") (class "Default")
      (node (ref "U$65") (pin "9") (pinfunction "DB2_9") (pintype "bidirectional"))
    )
    (net (code "404") (name "unconnected-(U$65-DB3-Pad10)") (class "Default")
      (node (ref "U$65") (pin "10") (pinfunction "DB3_10") (pintype "bidirectional"))
    )
  )
)
